# GPRS-ADM2483-V1_0________TF.net
KiCad netlist of a schematic drawn in Altium Designer
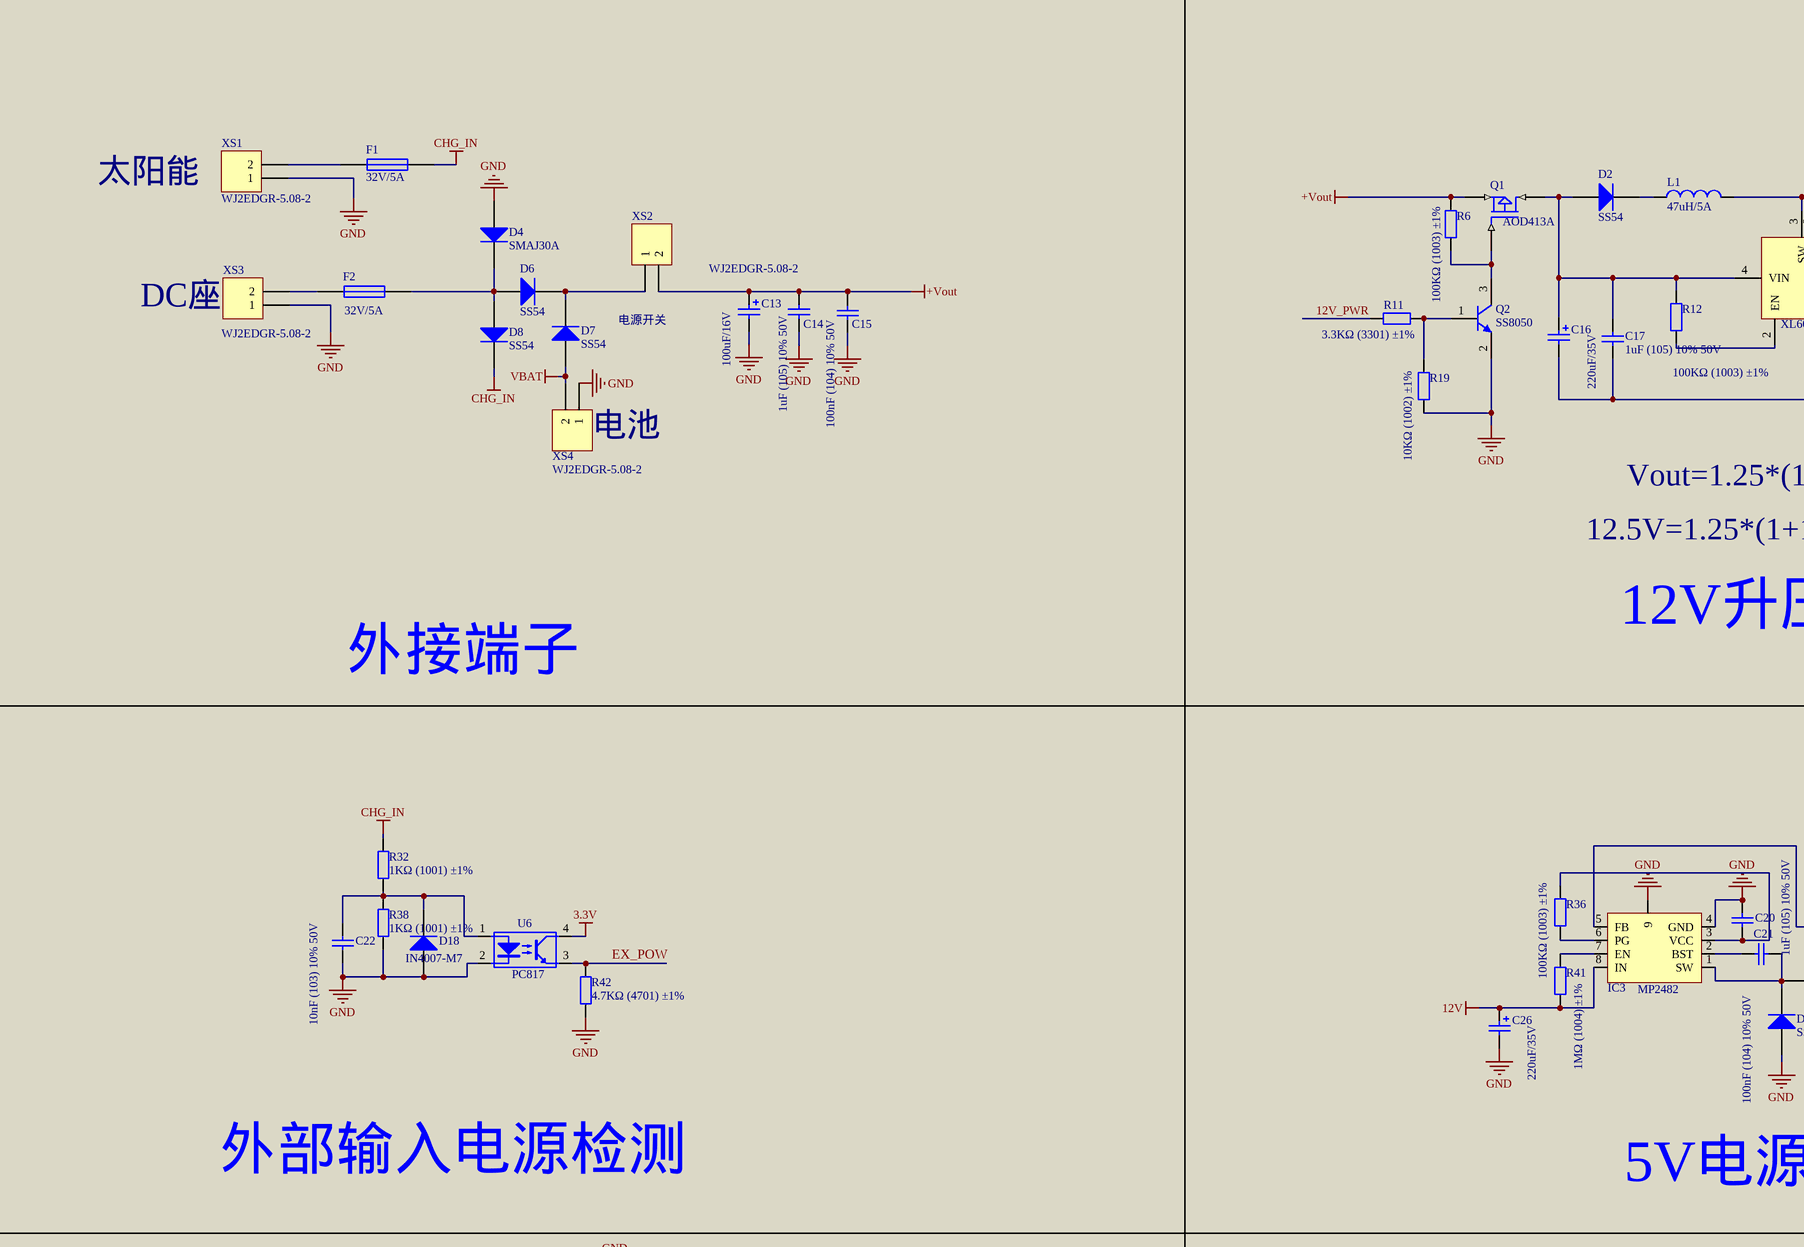
[diagram p0: GPRS-ADM2483-V1.0_______中科院TF卡.SchDoc, top left]
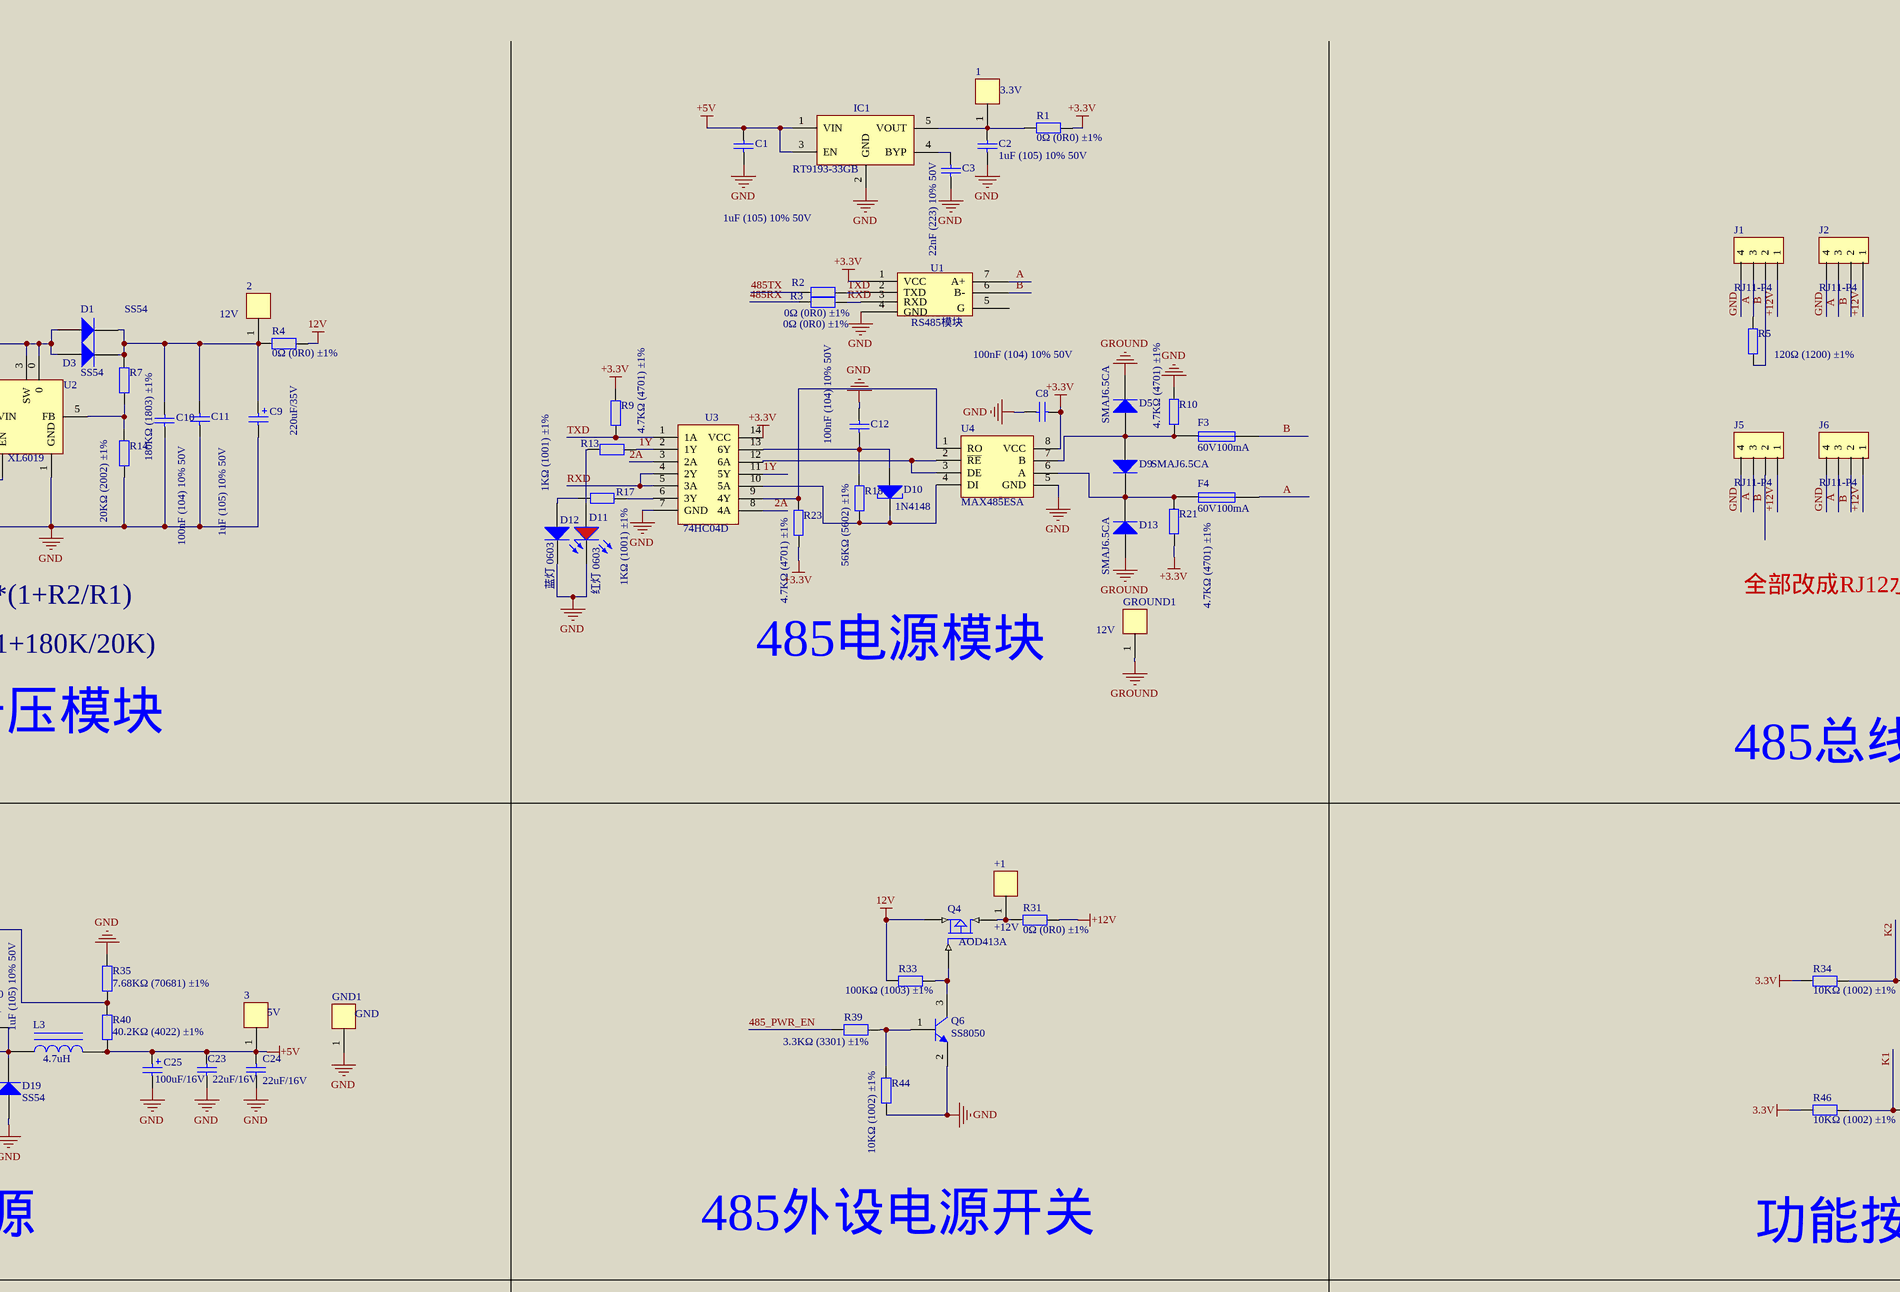
[diagram p1: GPRS-ADM2483-V1.0_______中科院TF卡.SchDoc, top middle]
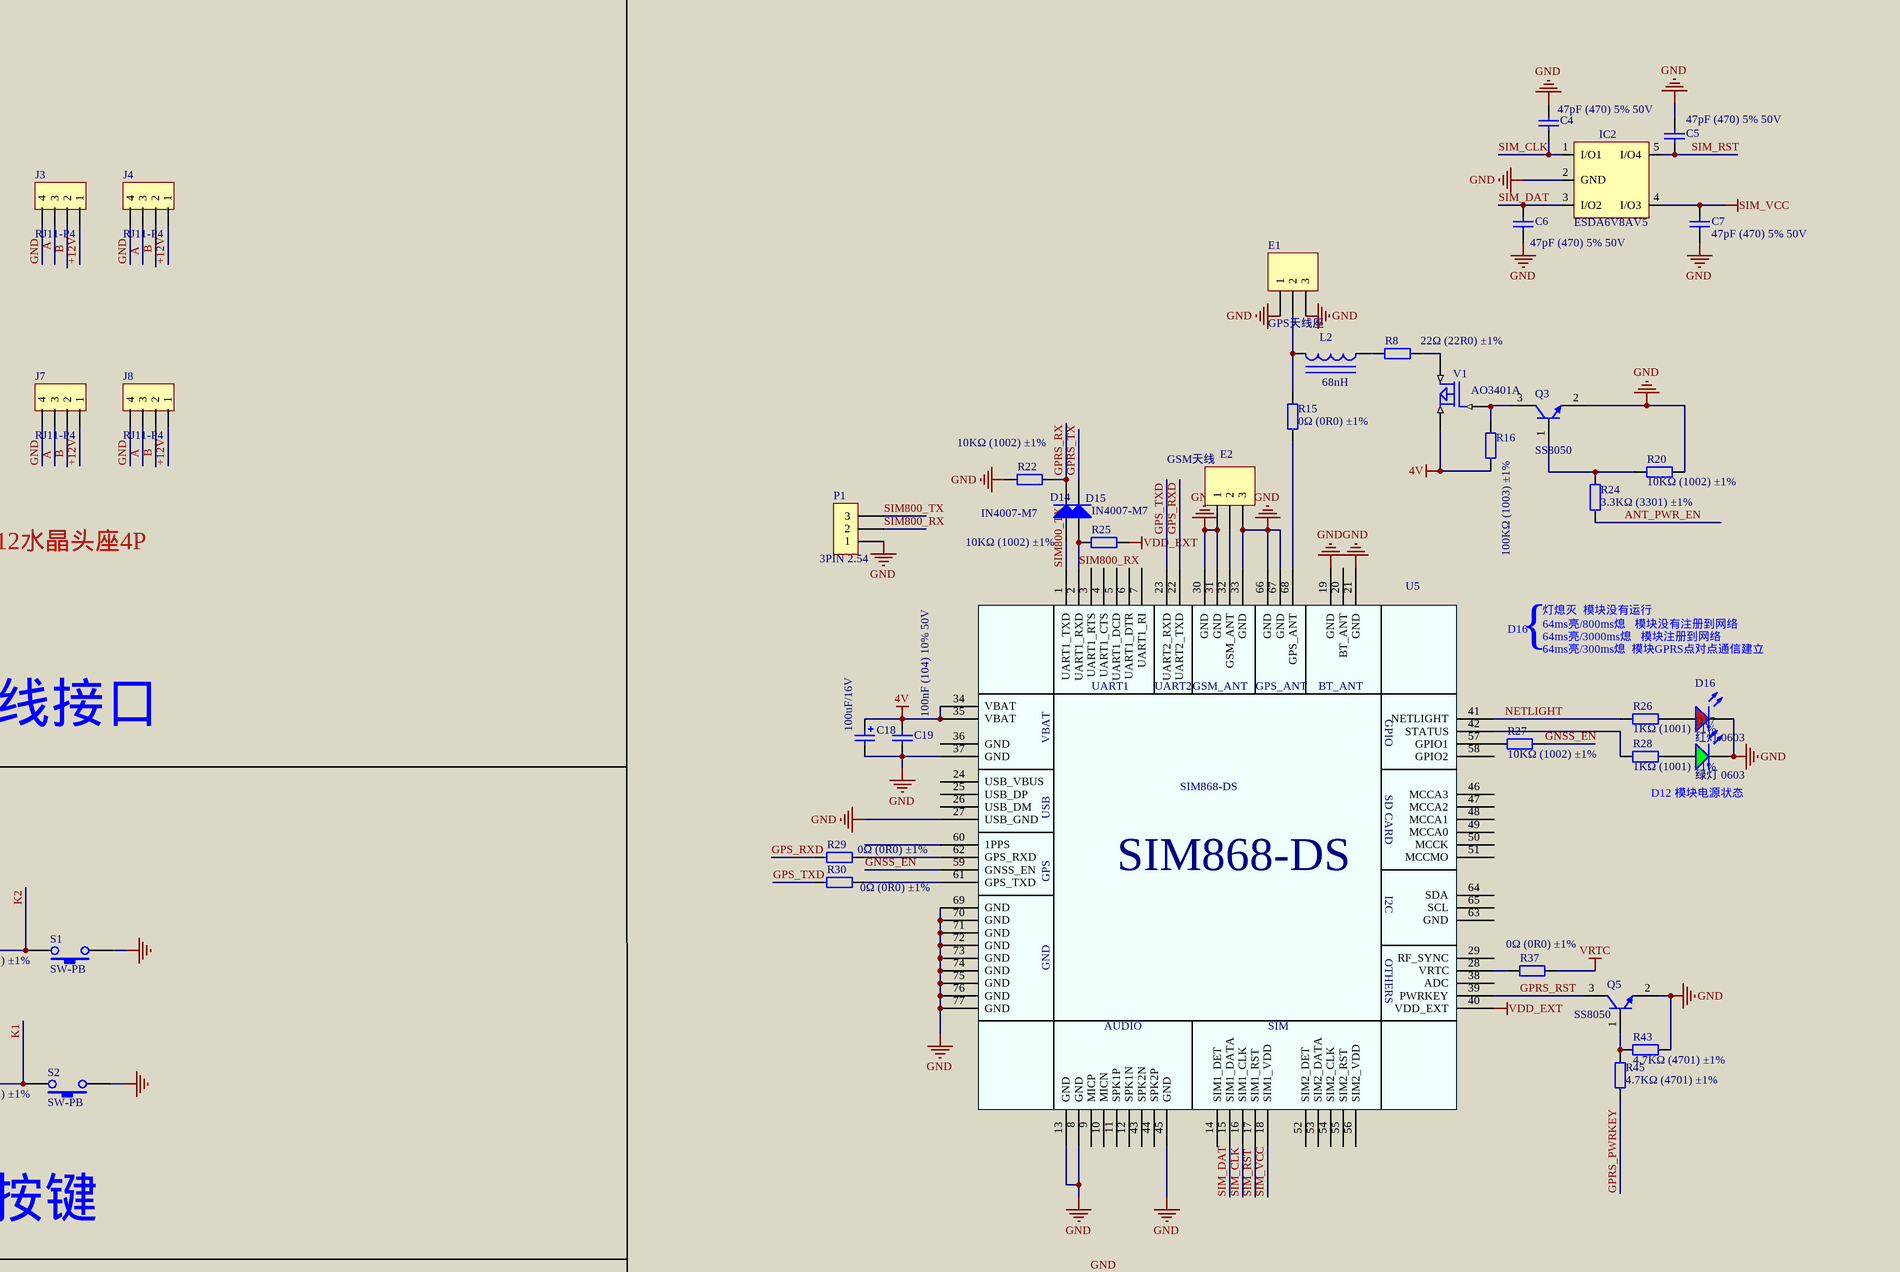
[diagram p2: GPRS-ADM2483-V1.0_______中科院TF卡.SchDoc, top right]
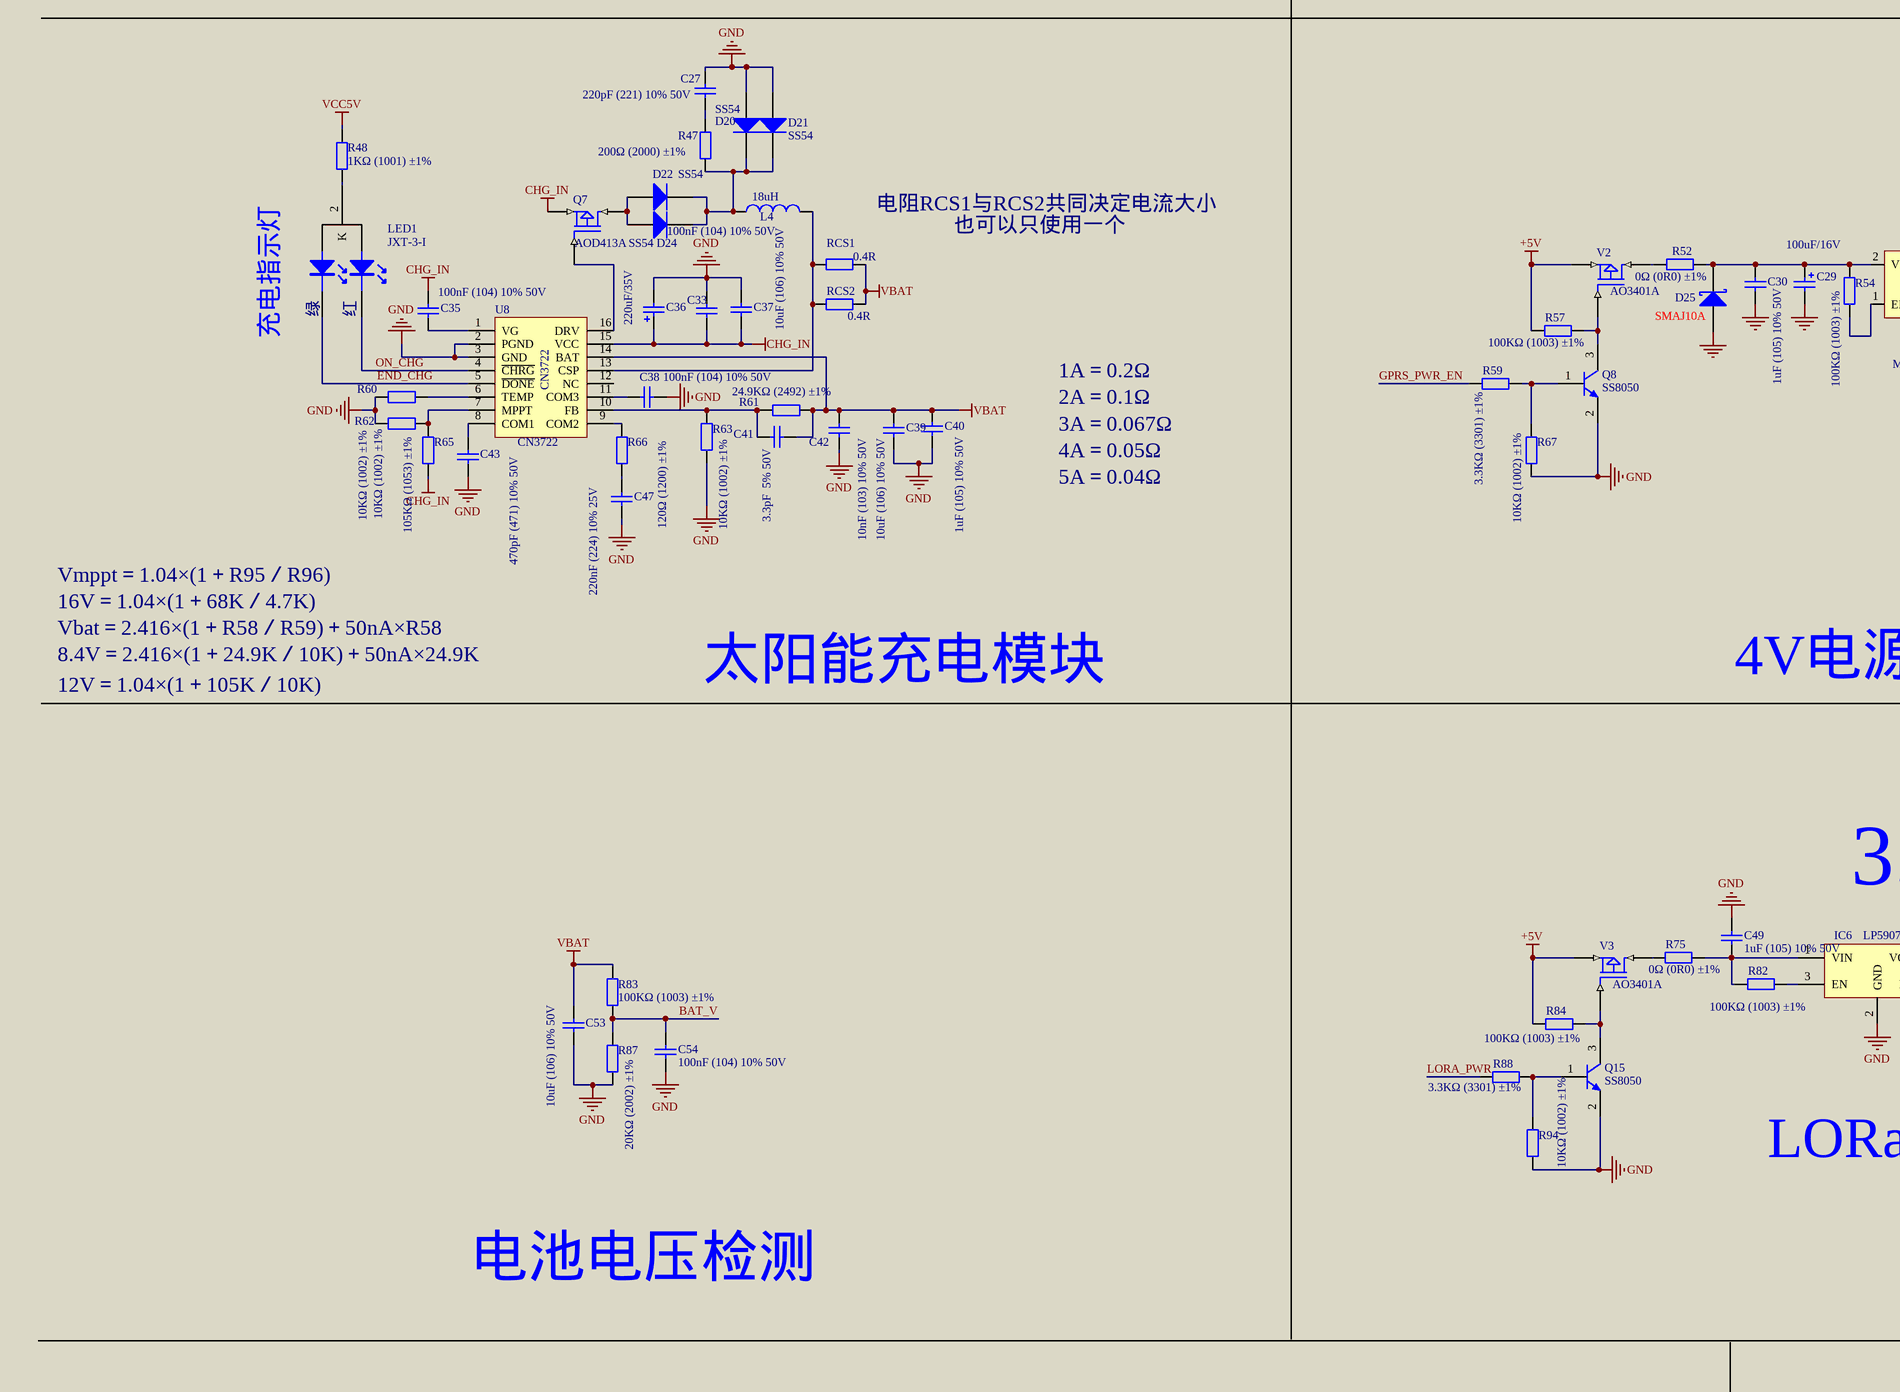
[diagram p3: GPRS-ADM2483-V1.0_______中科院TF卡.SchDoc, centre left]
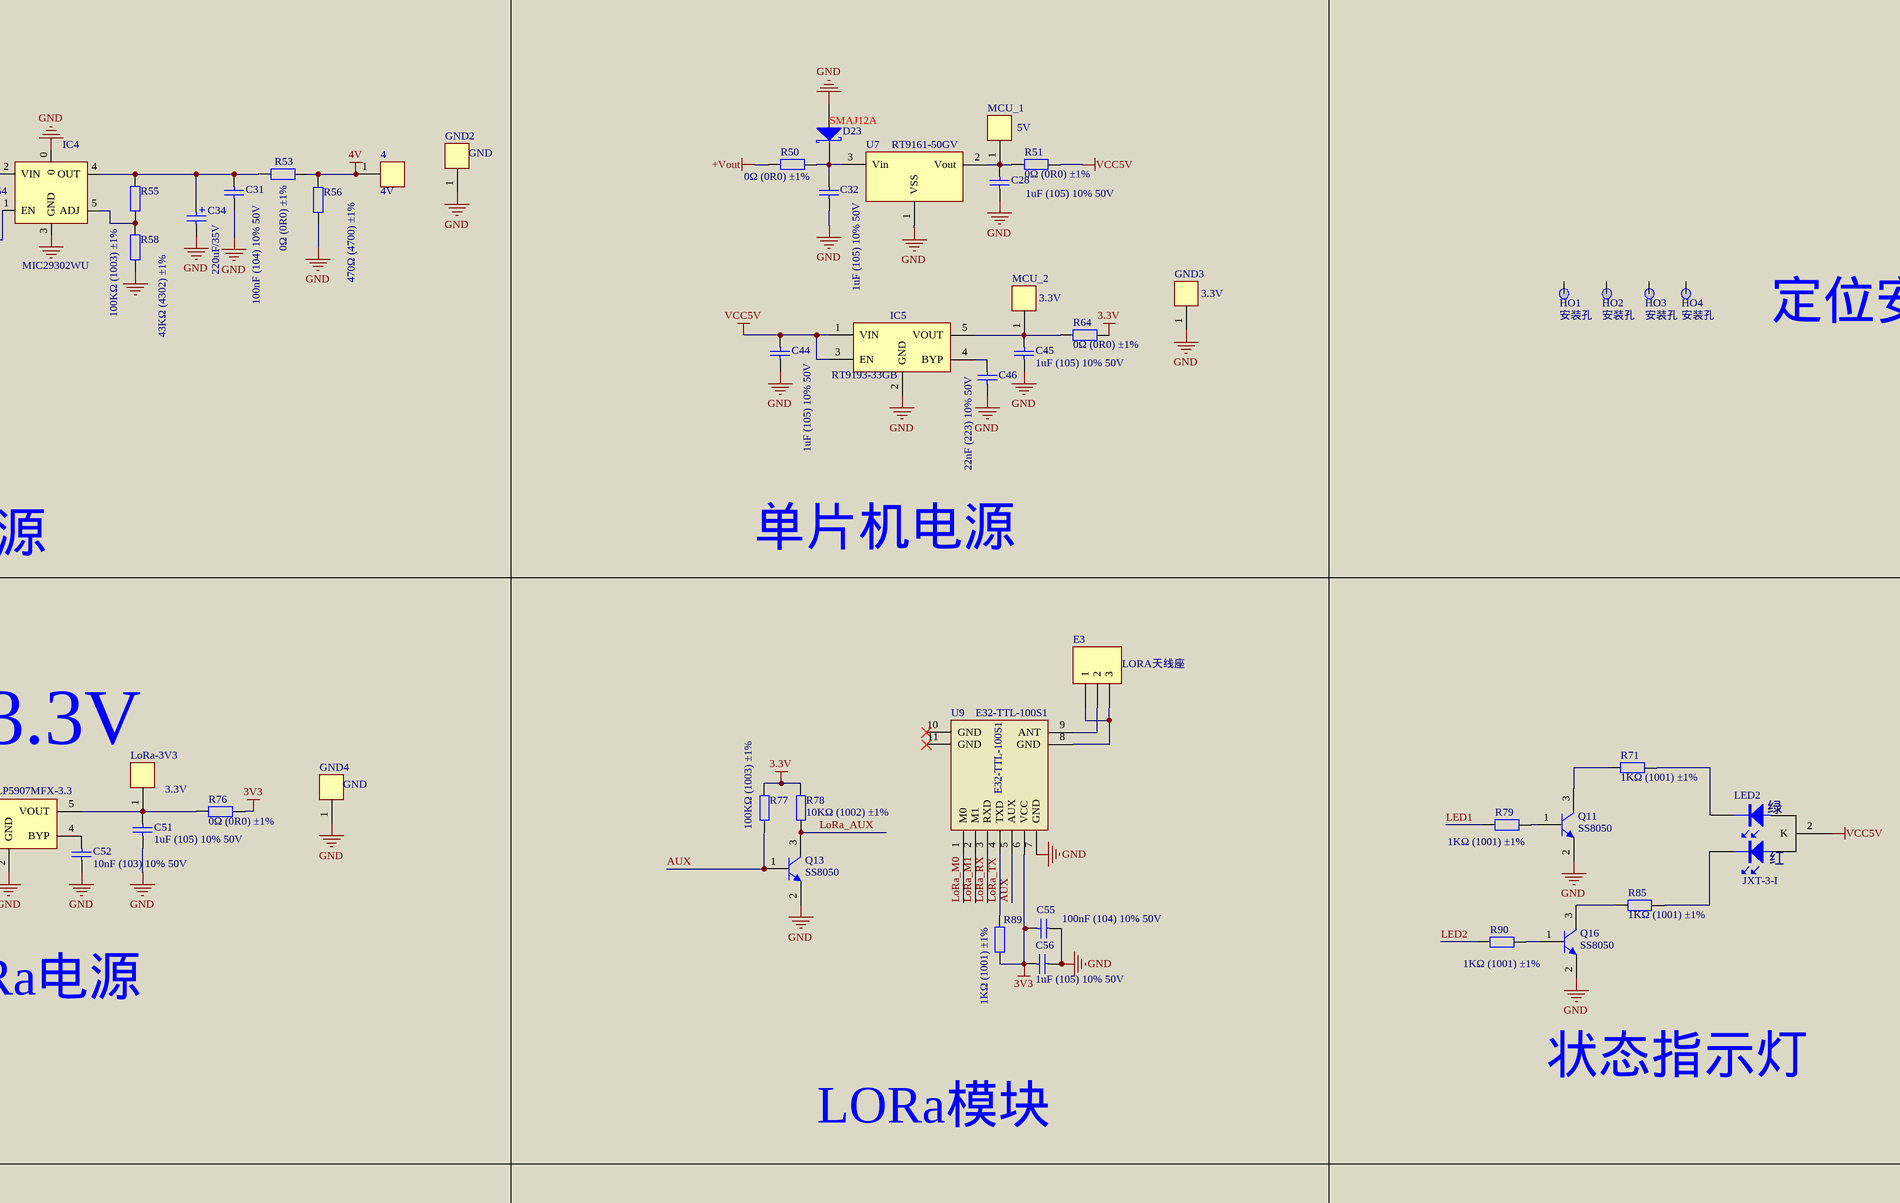
[diagram p4: GPRS-ADM2483-V1.0_______中科院TF卡.SchDoc, centre middle]
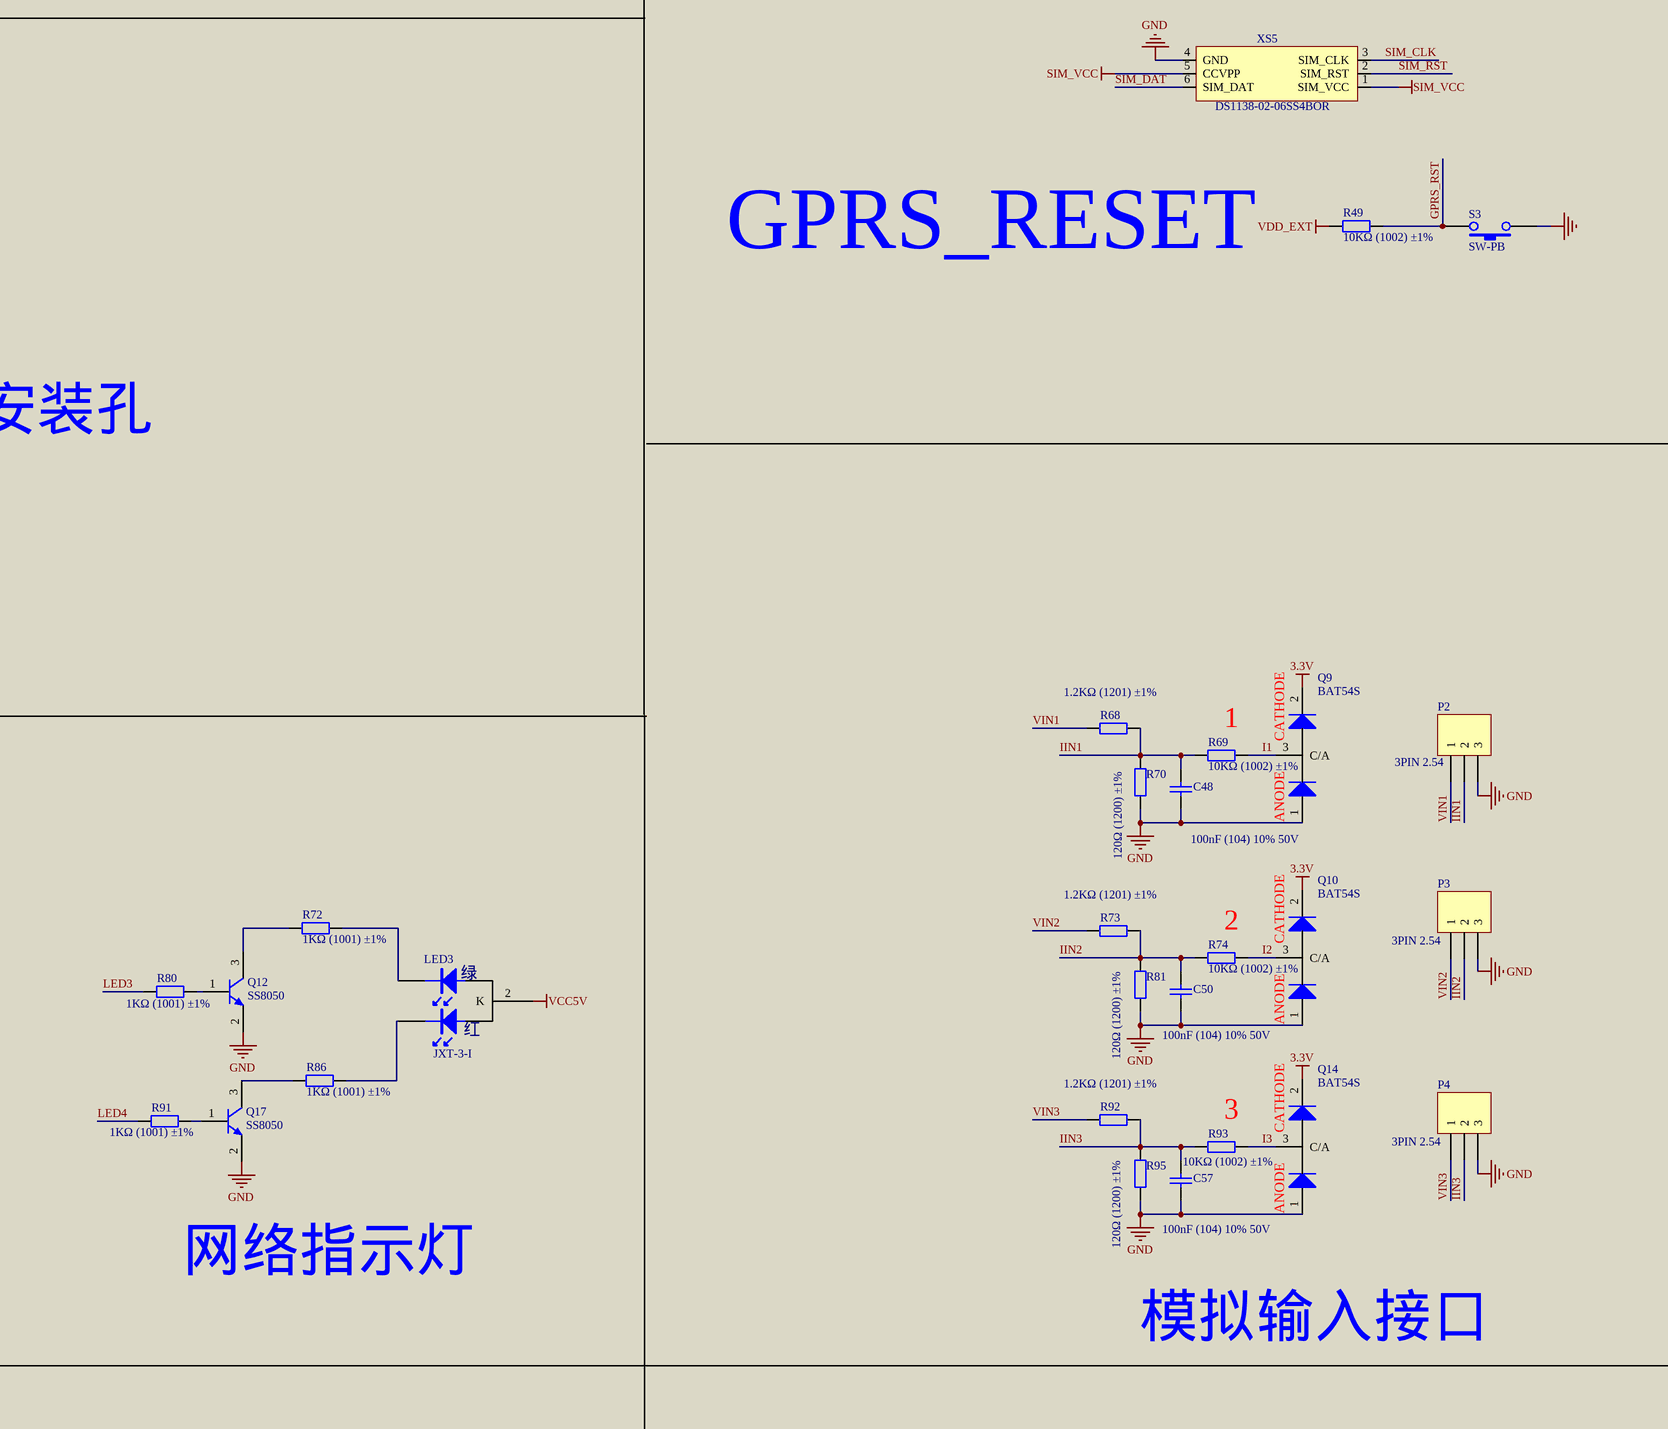
[diagram p5: GPRS-ADM2483-V1.0_______中科院TF卡.SchDoc, centre right]
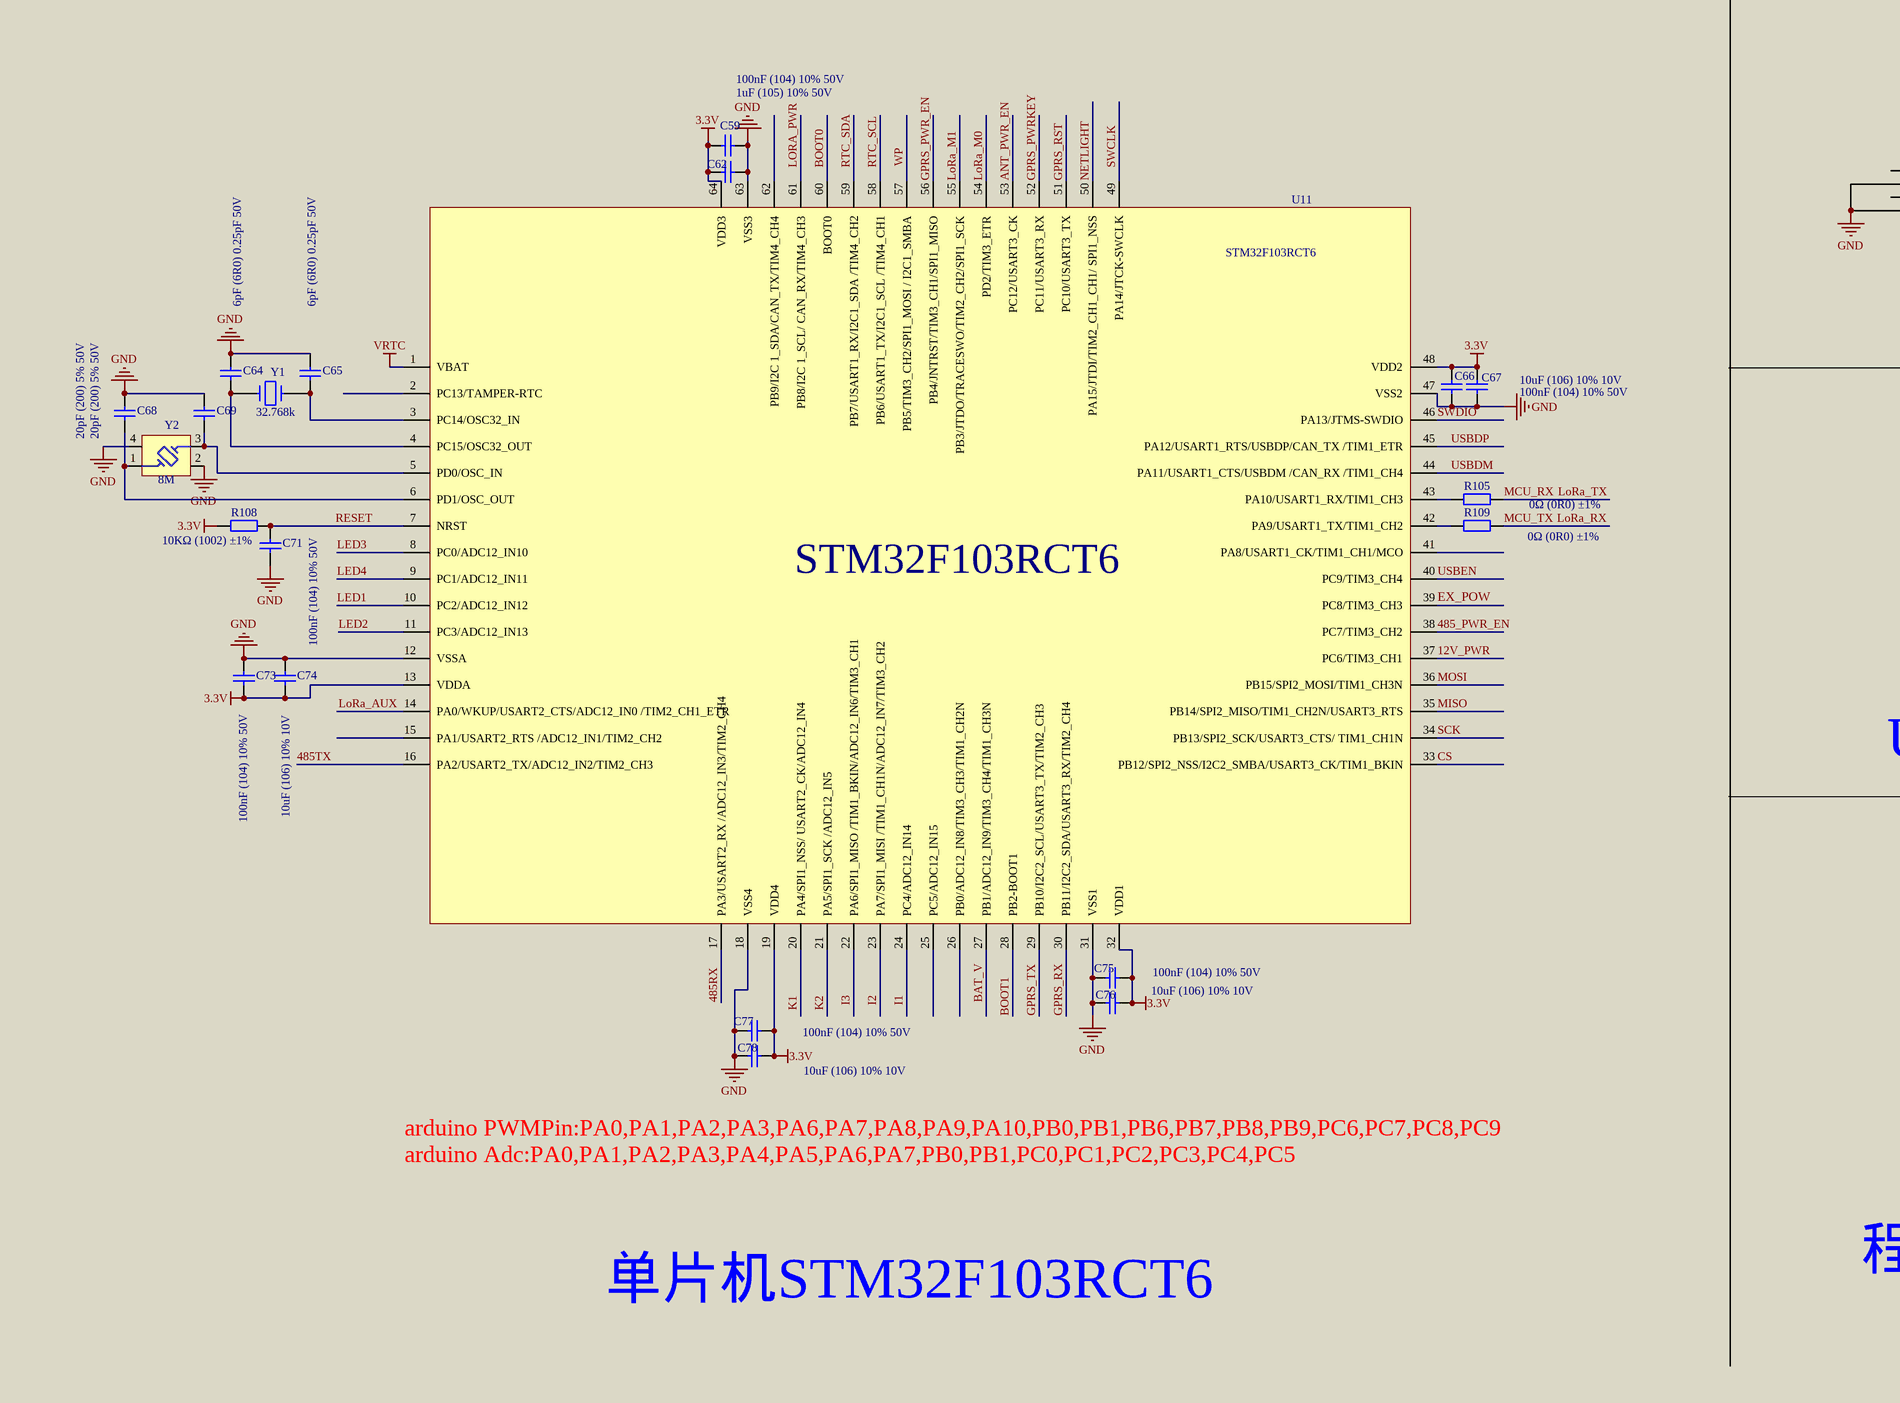
[diagram p6: GPRS-ADM2483-V1.0_______中科院TF卡.SchDoc, bottom left]
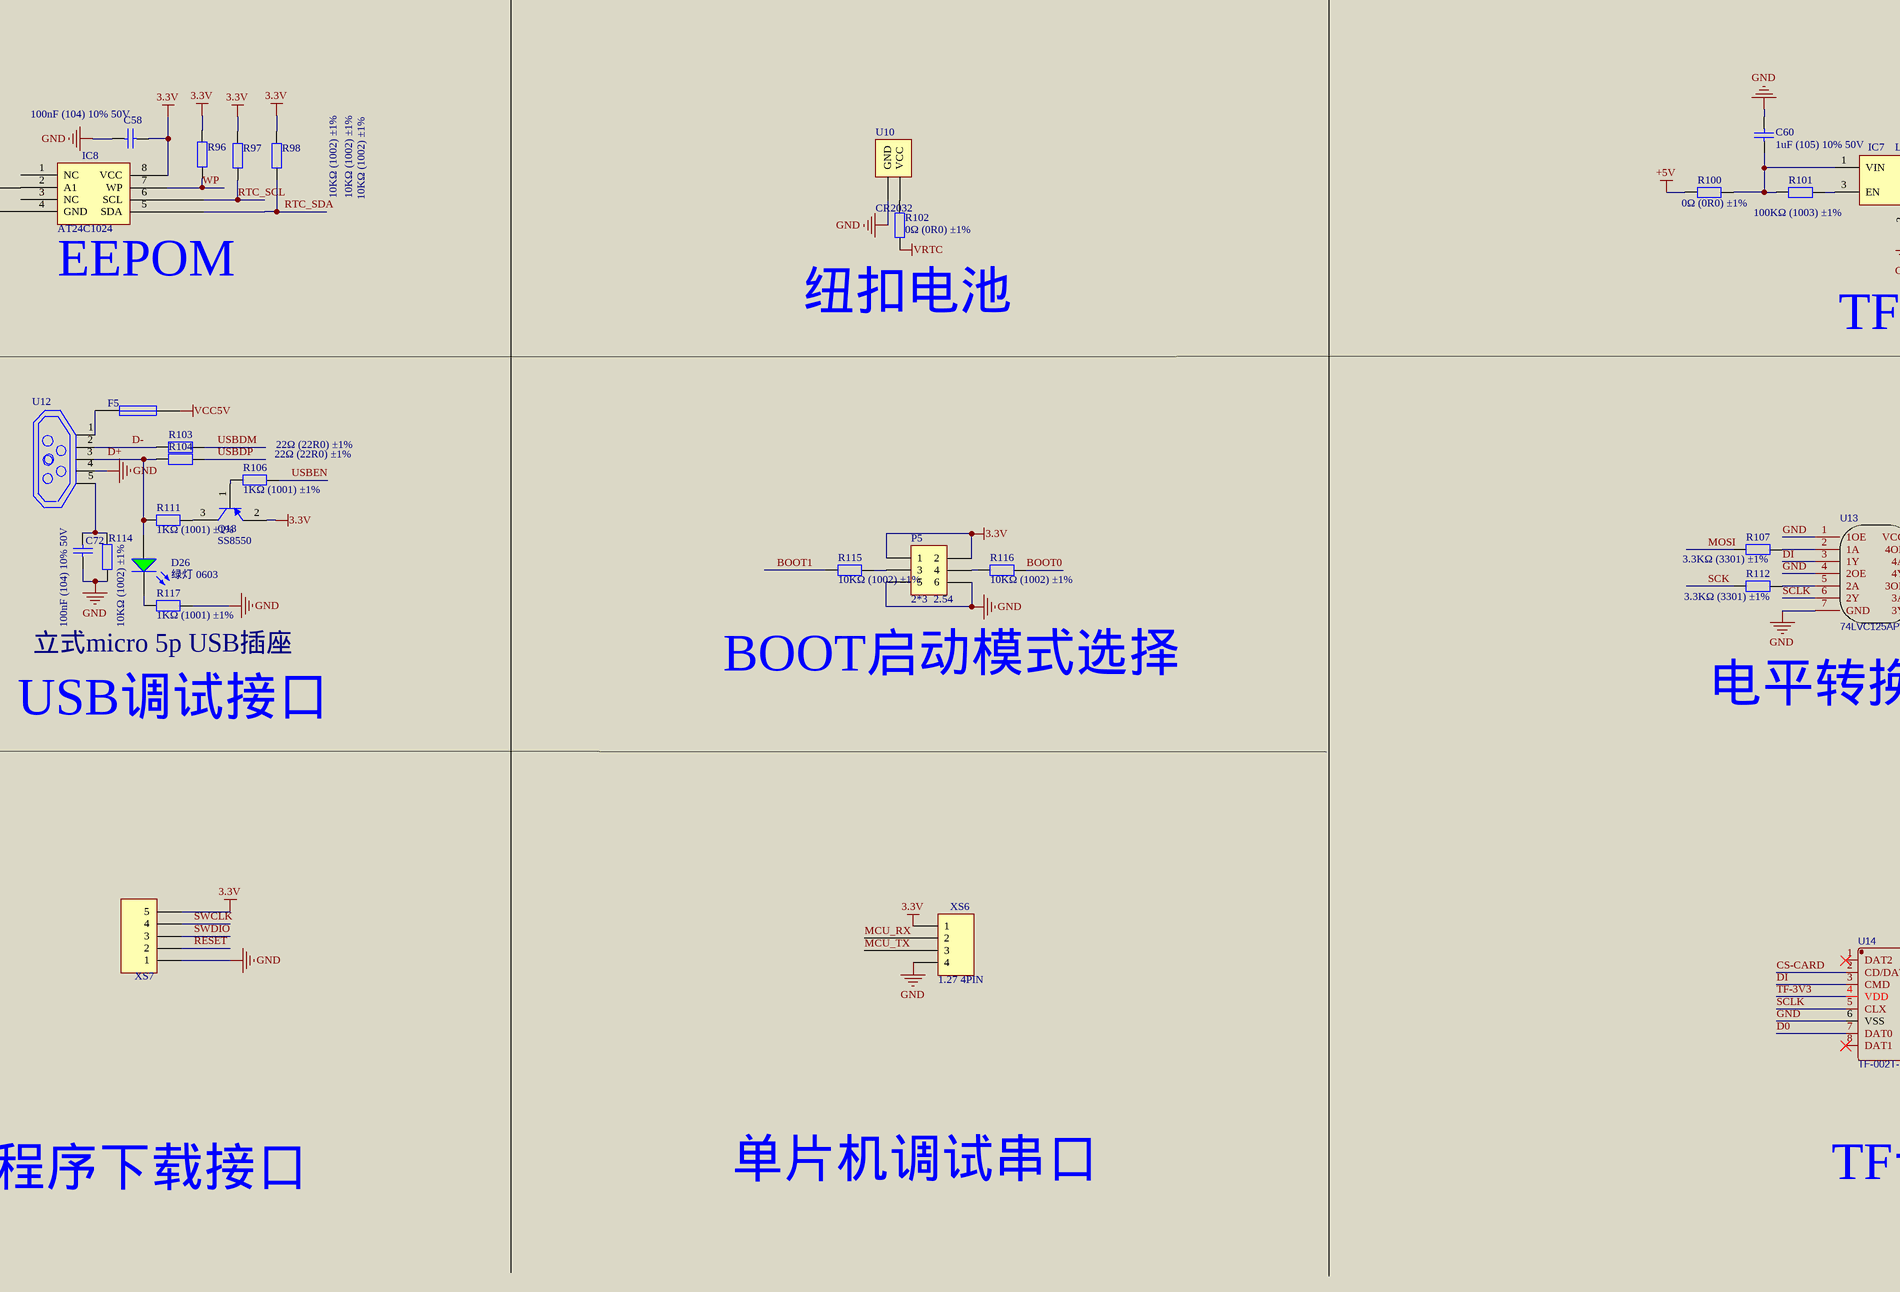
[diagram p7: GPRS-ADM2483-V1.0_______中科院TF卡.SchDoc, bottom middle]
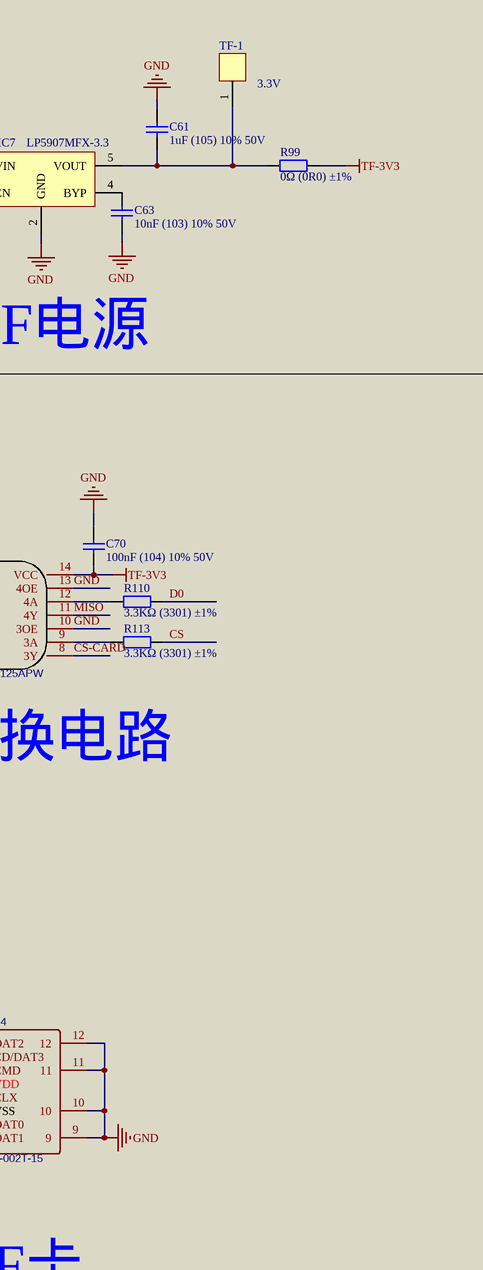
[diagram p8: GPRS-ADM2483-V1.0_______中科院TF卡.SchDoc, bottom right]

(export (version "E")
  (design (tool "Eeschema 10.0.6"))
  (components
    (comp (ref "+1")
      (value "+12V")
      (footprint "TEST_POINT")
      (description "测试点")
      (libsource (lib "InforCenterBoard") (part "TEST_POINT"))
    )
    (comp (ref "1")
      (value "3.3V")
      (footprint "TEST_POINT")
      (libsource (lib "InforCenterBoard") (part "TEST_POINT"))
    )
    (comp (ref "2")
      (value "12V")
      (footprint "TEST_POINT")
      (description "测试点")
      (libsource (lib "InforCenterBoard") (part "TEST_POINT"))
    )
    (comp (ref "3")
      (value "5V")
      (footprint "TEST_POINT")
      (description "测试点")
      (libsource (lib "InforCenterBoard") (part "TEST_POINT"))
    )
    (comp (ref "4")
      (value "4V")
      (footprint "TEST_POINT")
      (description "测试点")
      (libsource (lib "") (part "TEST_POINT_1"))
    )
    (comp (ref "C1")
      (value "1uF (105) 10% 50V")
      (footprint "LC-0603_C")
      (description "贴片电容")
      (libsource (lib "My_Library") (part "0603 1uF (105) 10% 50V"))
    )
    (comp (ref "C2")
      (value "1uF (105) 10% 50V")
      (footprint "LC-0603_C")
      (description "贴片电容")
      (libsource (lib "My_Library") (part "0603 1uF (105) 10% 50V"))
    )
    (comp (ref "C3")
      (value "22nF (223) 10% 50V")
      (footprint "LC-0603_C")
      (description "贴片电容")
      (libsource (lib "My_Library") (part "0603 22nF (223) 10% 50V"))
    )
    (comp (ref "C4")
      (value "47pF (470) 5% 50V")
      (footprint "LC-0603_C")
      (description "贴片电容")
      (libsource (lib "My_Library") (part "0603 47pF (470) 5% 50V"))
    )
    (comp (ref "C5")
      (value "47pF (470) 5% 50V")
      (footprint "LC-0603_C")
      (description "贴片电容")
      (libsource (lib "My_Library") (part "0603 47pF (470) 5% 50V"))
    )
    (comp (ref "C6")
      (value "47pF (470) 5% 50V")
      (footprint "LC-0603_C")
      (description "贴片电容")
      (libsource (lib "My_Library") (part "0603 47pF (470) 5% 50V"))
    )
    (comp (ref "C7")
      (value "47pF (470) 5% 50V")
      (footprint "LC-0603_C")
      (description "贴片电容")
      (libsource (lib "My_Library") (part "0603 47pF (470) 5% 50V"))
    )
    (comp (ref "C8")
      (value "100nF (104) 10% 50V")
      (footprint "LC-0603_C")
      (description "贴片电容")
      (libsource (lib "My_Library") (part "0603 100nF (104) 10% 50V"))
    )
    (comp (ref "C9")
      (value "220uF/35V")
      (footprint "CAPAE8*10.5")
      (description "贴片铝电解电容")
      (fields (field (name "PUBLISHER") "Altium Limited"))
      (libsource (lib "AirPlaneSign") (part "Cap -8*10.5"))
    )
    (comp (ref "C10")
      (value "100nF (104) 10% 50V")
      (footprint "LC-0603_C")
      (description "贴片电容")
      (libsource (lib "My_Library") (part "0603 100nF (104) 10% 50V"))
    )
    (comp (ref "C11")
      (value "1uF (105) 10% 50V")
      (footprint "LC-0603_C")
      (description "贴片电容")
      (libsource (lib "My_Library") (part "0603 1uF (105) 10% 50V"))
    )
    (comp (ref "C12")
      (value "100nF (104) 10% 50V")
      (footprint "LC-0603_C")
      (description "贴片电容")
      (libsource (lib "My_Library") (part "0603 100nF (104) 10% 50V"))
    )
    (comp (ref "C13")
      (value "100uF/16V")
      (footprint "CAPAE6.3*7.7")
      (description "贴片铝电解电容")
      (fields (field (name "PUBLISHER") "Altium Limited"))
      (libsource (lib "AirPlaneSign") (part "Cap -6.3*7.7"))
    )
    (comp (ref "C14")
      (value "1uF (105) 10% 50V")
      (footprint "LC-0603_C")
      (description "贴片电容")
      (libsource (lib "My_Library") (part "0603 1uF (105) 10% 50V"))
    )
    (comp (ref "C15")
      (value "100nF (104) 10% 50V")
      (footprint "LC-0603_C")
      (description "贴片电容")
      (libsource (lib "My_Library") (part "0603 100nF (104) 10% 50V"))
    )
    (comp (ref "C16")
      (value "220uF/35V")
      (footprint "CAPAE8*10.5")
      (description "贴片铝电解电容")
      (fields (field (name "PUBLISHER") "Altium Limited"))
      (libsource (lib "AirPlaneSign") (part "Cap -8*10.5"))
    )
    (comp (ref "C17")
      (value "1uF (105) 10% 50V")
      (footprint "LC-0603_C")
      (description "贴片电容")
      (libsource (lib "My_Library") (part "0603 1uF (105) 10% 50V"))
    )
    (comp (ref "C18")
      (value "100uF/16V")
      (footprint "CAPAE6.3*7.7")
      (description "贴片铝电解电容")
      (fields (field (name "PUBLISHER") "Altium Limited"))
      (libsource (lib "AirPlaneSign") (part "Cap -6.3*7.7"))
    )
    (comp (ref "C19")
      (value "100nF (104) 10% 50V")
      (footprint "LC-0603_C")
      (description "贴片电容")
      (libsource (lib "My_Library") (part "0603 100nF (104) 10% 50V"))
    )
    (comp (ref "C20")
      (value "1uF (105) 10% 50V")
      (footprint "LC-0603_C")
      (description "贴片电容")
      (libsource (lib "My_Library") (part "0603 1uF (105) 10% 50V"))
    )
    (comp (ref "C21")
      (value "100nF (104) 10% 50V")
      (footprint "LC-0603_C")
      (description "贴片电容")
      (libsource (lib "My_Library") (part "0603 100nF (104) 10% 50V"))
    )
    (comp (ref "C22")
      (value "10nF (103) 10% 50V")
      (footprint "LC-0603_C")
      (description "贴片电容")
      (libsource (lib "My_Library") (part "0603 10nF (103) 10% 50V"))
    )
    (comp (ref "C23")
      (value "22uF/16V")
      (footprint "C-1206")
      (description "贴片电容")
      (fields (field (name "PUBLISHER") "Altium Limited"))
      (libsource (lib "AirPlaneSign") (part "Cap"))
    )
    (comp (ref "C24")
      (value "22uF/16V")
      (footprint "C-1206")
      (description "贴片电容")
      (fields (field (name "PUBLISHER") "Altium Limited"))
      (libsource (lib "AirPlaneSign") (part "Cap"))
    )
    (comp (ref "C25")
      (value "100uF/16V")
      (footprint "CAPAE6.3*7.7")
      (description "贴片铝电解电容")
      (fields (field (name "PUBLISHER") "Altium Limited"))
      (libsource (lib "AirPlaneSign") (part "Cap -6.3*7.7"))
    )
    (comp (ref "C26")
      (value "220uF/35V")
      (footprint "CAPAE8*10.5")
      (description "贴片铝电解电容")
      (fields (field (name "PUBLISHER") "Altium Limited"))
      (libsource (lib "AirPlaneSign") (part "Cap -8*10.5"))
    )
    (comp (ref "C27")
      (value "220pF (221) 10% 50V")
      (footprint "LC-0603_C")
      (description "贴片电容")
      (libsource (lib "My_Library") (part "0603 220pF (221) 10% 50V"))
    )
    (comp (ref "C28")
      (value "1uF (105) 10% 50V")
      (footprint "LC-0603_C")
      (description "贴片电容")
      (libsource (lib "My_Library") (part "0603 1uF (105) 10% 50V"))
    )
    (comp (ref "C29")
      (value "100uF/16V")
      (footprint "CAPAE6.3*7.7")
      (description "贴片铝电解电容")
      (fields (field (name "PUBLISHER") "Altium Limited"))
      (libsource (lib "AirPlaneSign") (part "Cap -6.3*7.7"))
    )
    (comp (ref "C30")
      (value "1uF (105) 10% 50V")
      (footprint "LC-0603_C")
      (description "贴片电容")
      (libsource (lib "My_Library") (part "0603 1uF (105) 10% 50V"))
    )
    (comp (ref "C31")
      (value "100nF (104) 10% 50V")
      (footprint "LC-0603_C")
      (description "贴片电容")
      (libsource (lib "My_Library") (part "0603 100nF (104) 10% 50V"))
    )
    (comp (ref "C32")
      (value "1uF (105) 10% 50V")
      (footprint "LC-0603_C")
      (description "贴片电容")
      (libsource (lib "My_Library") (part "0603 1uF (105) 10% 50V"))
    )
    (comp (ref "C33")
      (value "100nF (104) 10% 50V")
      (footprint "LC-0603_C")
      (description "贴片电容")
      (libsource (lib "My_Library") (part "0603 100nF (104) 10% 50V"))
    )
    (comp (ref "C34")
      (value "220uF/35V")
      (footprint "CAPAE8*10.5")
      (description "贴片铝电解电容")
      (fields (field (name "PUBLISHER") "Altium Limited"))
      (libsource (lib "AirPlaneSign") (part "Cap -8*10.5"))
    )
    (comp (ref "C35")
      (value "100nF (104) 10% 50V")
      (footprint "LC-0603_C")
      (description "贴片电容")
      (libsource (lib "My_Library") (part "0603 100nF (104) 10% 50V"))
    )
    (comp (ref "C36")
      (value "220uF/35V")
      (footprint "CAPAE8*10.5")
      (description "贴片铝电解电容")
      (fields (field (name "PUBLISHER") "Altium Limited"))
      (libsource (lib "AirPlaneSign") (part "Cap -8*10.5"))
    )
    (comp (ref "C37")
      (value "10uF (106) 10% 50V")
      (footprint "LC-1206_C")
      (description "贴片电容")
      (libsource (lib "My_Library") (part "1206 10uF (106) 10% 50V"))
    )
    (comp (ref "C38")
      (value "100nF (104) 10% 50V")
      (footprint "LC-0603_C")
      (description "贴片电容")
      (libsource (lib "My_Library") (part "0603 100nF (104) 10% 50V"))
    )
    (comp (ref "C39")
      (value "10uF (106) 10% 50V")
      (footprint "LC-1206_C")
      (description "贴片电容")
      (libsource (lib "My_Library") (part "1206 10uF (106) 10% 50V"))
    )
    (comp (ref "C40")
      (value "1uF (105) 10% 50V")
      (footprint "LC-0603_C")
      (description "贴片电容")
      (libsource (lib "My_Library") (part "0603 1uF (105) 10% 50V"))
    )
    (comp (ref "C41")
      (value "3.3pF  5% 50V")
      (footprint "LC-0603_C")
      (description "贴片电容")
      (libsource (lib "My_Library") (part "0603 33pF (330) 5% 50V"))
    )
    (comp (ref "C42")
      (value "10nF (103) 10% 50V")
      (footprint "LC-0603_C")
      (description "贴片电容")
      (libsource (lib "My_Library") (part "0603 10nF (103) 10% 50V"))
    )
    (comp (ref "C43")
      (value "470pF (471) 10% 50V")
      (footprint "LC-0603_C")
      (description "贴片电容")
      (libsource (lib "My_Library") (part "0603 470pF (471) 10% 50V"))
    )
    (comp (ref "C44")
      (value "1uF (105) 10% 50V")
      (footprint "LC-0603_C")
      (description "贴片电容")
      (libsource (lib "My_Library") (part "0603 1uF (105) 10% 50V"))
    )
    (comp (ref "C45")
      (value "1uF (105) 10% 50V")
      (footprint "LC-0603_C")
      (description "贴片电容")
      (libsource (lib "My_Library") (part "0603 1uF (105) 10% 50V"))
    )
    (comp (ref "C46")
      (value "22nF (223) 10% 50V")
      (footprint "LC-0603_C")
      (description "贴片电容")
      (libsource (lib "My_Library") (part "0603 22nF (223) 10% 50V"))
    )
    (comp (ref "C47")
      (value "220nF (224) 10% 25V")
      (footprint "LC-0603_C")
      (description "贴片电容")
      (libsource (lib "My_Library") (part "0603 220nF (224) 10% 25V"))
    )
    (comp (ref "C48")
      (value "100nF (104) 10% 50V")
      (footprint "LC-0603_C")
      (description "贴片电容")
      (libsource (lib "My_Library") (part "0603 100nF (104) 10% 50V"))
    )
    (comp (ref "C49")
      (value "1uF (105) 10% 50V")
      (footprint "LC-0603_C")
      (description "贴片电容")
      (libsource (lib "My_Library") (part "0603 1uF (105) 10% 50V"))
    )
    (comp (ref "C50")
      (value "100nF (104) 10% 50V")
      (footprint "LC-0603_C")
      (description "贴片电容")
      (libsource (lib "My_Library") (part "0603 100nF (104) 10% 50V"))
    )
    (comp (ref "C51")
      (value "1uF (105) 10% 50V")
      (footprint "LC-0603_C")
      (description "贴片电容")
      (libsource (lib "My_Library") (part "0603 1uF (105) 10% 50V"))
    )
    (comp (ref "C52")
      (value "10nF (103) 10% 50V")
      (footprint "LC-0603_C")
      (description "贴片电容")
      (libsource (lib "My_Library") (part "0603 10nF (103) 10% 50V"))
    )
    (comp (ref "C53")
      (value "10uF (106) 10% 50V")
      (footprint "LC-1206_C")
      (description "贴片电容")
      (libsource (lib "My_Library") (part "1206 10uF (106) 10% 50V"))
    )
    (comp (ref "C54")
      (value "100nF (104) 10% 50V")
      (footprint "LC-0603_C")
      (description "贴片电容")
      (libsource (lib "My_Library") (part "0603 100nF (104) 10% 50V"))
    )
    (comp (ref "C55")
      (value "100nF (104) 10% 50V")
      (footprint "LC-0603_C")
      (description "贴片电容")
      (libsource (lib "My_Library") (part "0603 100nF (104) 10% 50V"))
    )
    (comp (ref "C56")
      (value "1uF (105) 10% 50V")
      (footprint "LC-0603_C")
      (description "贴片电容")
      (libsource (lib "My_Library") (part "0603 1uF (105) 10% 50V"))
    )
    (comp (ref "C57")
      (value "100nF (104) 10% 50V")
      (footprint "LC-0603_C")
      (description "贴片电容")
      (libsource (lib "My_Library") (part "0603 100nF (104) 10% 50V"))
    )
    (comp (ref "C58")
      (value "100nF (104) 10% 50V")
      (footprint "LC-0603_C")
      (description "贴片电容")
      (libsource (lib "My_Library") (part "0603 100nF (104) 10% 50V"))
    )
    (comp (ref "C59")
      (value "1uF (105) 10% 50V")
      (footprint "LC-0603_C")
      (description "贴片电容")
      (libsource (lib "My_Library") (part "0603 1uF (105) 10% 50V"))
    )
    (comp (ref "C60")
      (value "1uF (105) 10% 50V")
      (footprint "LC-0603_C")
      (description "贴片电容")
      (libsource (lib "My_Library") (part "0603 1uF (105) 10% 50V"))
    )
    (comp (ref "C61")
      (value "1uF (105) 10% 50V")
      (footprint "LC-0603_C")
      (description "贴片电容")
      (libsource (lib "My_Library") (part "0603 1uF (105) 10% 50V"))
    )
    (comp (ref "C62")
      (value "100nF (104) 10% 50V")
      (footprint "LC-0603_C")
      (description "贴片电容")
      (libsource (lib "My_Library") (part "0603 100nF (104) 10% 50V"))
    )
    (comp (ref "C63")
      (value "10nF (103) 10% 50V")
      (footprint "LC-0603_C")
      (description "贴片电容")
      (libsource (lib "My_Library") (part "0603 10nF (103) 10% 50V"))
    )
    (comp (ref "C64")
      (value "6pF (6R0) 0.25pF 50V")
      (footprint "LC-0603_C")
      (description "贴片电容")
      (libsource (lib "My_Library") (part "0603 6pF (6R0) 0.25pF 50V"))
    )
    (comp (ref "C65")
      (value "6pF (6R0) 0.25pF 50V")
      (footprint "LC-0603_C")
      (description "贴片电容")
      (libsource (lib "My_Library") (part "0603 6pF (6R0) 0.25pF 50V"))
    )
    (comp (ref "C66")
      (value "10uF (106) 10% 10V")
      (footprint "LC-0603_C")
      (description "贴片电容")
      (libsource (lib "My_Library") (part "0603 10uF (106) 10% 10V"))
    )
    (comp (ref "C67")
      (value "100nF (104) 10% 50V")
      (footprint "LC-0603_C")
      (description "贴片电容")
      (libsource (lib "My_Library") (part "0603 100nF (104) 10% 50V"))
    )
    (comp (ref "C68")
      (value "20pF (200) 5% 50V")
      (footprint "LC-0603_C")
      (description "贴片电容")
      (libsource (lib "My_Library") (part "0603 20pF (200) 5% 50V"))
    )
    (comp (ref "C69")
      (value "20pF (200) 5% 50V")
      (footprint "LC-0603_C")
      (description "贴片电容")
      (libsource (lib "My_Library") (part "0603 20pF (200) 5% 50V"))
    )
    (comp (ref "C70")
      (value "100nF (104) 10% 50V")
      (footprint "LC-0603_C")
      (description "贴片电容")
      (libsource (lib "My_Library") (part "0603 100nF (104) 10% 50V"))
    )
    (comp (ref "C71")
      (value "100nF (104) 10% 50V")
      (footprint "LC-0603_C")
      (description "贴片电容")
      (libsource (lib "My_Library") (part "0603 100nF (104) 10% 50V"))
    )
    (comp (ref "C72")
      (value "100nF (104) 10% 50V")
      (footprint "LC-0603_C")
      (description "贴片电容")
      (libsource (lib "My_Library") (part "0603 100nF (104) 10% 50V"))
    )
    (comp (ref "C73")
      (value "100nF (104) 10% 50V")
      (footprint "LC-0603_C")
      (description "贴片电容")
      (libsource (lib "My_Library") (part "0603 100nF (104) 10% 50V"))
    )
    (comp (ref "C74")
      (value "10uF (106) 10% 10V")
      (footprint "LC-0603_C")
      (description "贴片电容")
      (libsource (lib "My_Library") (part "0603 10uF (106) 10% 10V"))
    )
    (comp (ref "C75")
      (value "100nF (104) 10% 50V")
      (footprint "LC-0603_C")
      (description "贴片电容")
      (libsource (lib "My_Library") (part "0603 100nF (104) 10% 50V"))
    )
    (comp (ref "C76")
      (value "10uF (106) 10% 10V")
      (footprint "LC-0603_C")
      (description "贴片电容")
      (libsource (lib "My_Library") (part "0603 10uF (106) 10% 10V"))
    )
    (comp (ref "C77")
      (value "100nF (104) 10% 50V")
      (footprint "LC-0603_C")
      (description "贴片电容")
      (libsource (lib "My_Library") (part "0603 100nF (104) 10% 50V"))
    )
    (comp (ref "C78")
      (value "10uF (106) 10% 10V")
      (footprint "LC-0603_C")
      (description "贴片电容")
      (libsource (lib "My_Library") (part "0603 10uF (106) 10% 10V"))
    )
    (comp (ref "D1")
      (value "SS54")
      (footprint "LC-SMA(DO-214AC)_S1")
      (description "二极管")
      (libsource (lib "My_Library") (part "SMA(DO-214AC) SS54"))
    )
    (comp (ref "D2")
      (value "SS54")
      (footprint "LC-SMA(DO-214AC)_S1")
      (description "二极管")
      (libsource (lib "My_Library") (part "SMA(DO-214AC) SS54"))
    )
    (comp (ref "D3")
      (value "SS54")
      (footprint "LC-SMA(DO-214AC)_S1")
      (description "二极管")
      (libsource (lib "My_Library") (part "SMA(DO-214AC) SS54"))
    )
    (comp (ref "D4")
      (value "SMAJ30A")
      (footprint "LC-SMA(DO-214AC)_S5")
      (description "TVS二极管")
      (fields (field (name "PUBLISHER") "Altium Limited"))
      (libsource (lib "AirPlaneSign") (part "SMAJ30A"))
    )
    (comp (ref "D5")
      (value "SMAJ6.5CA")
      (footprint "DO-214AC")
      (description "通用二极管")
      (fields (field (name "PUBLISHER") "Altium Limited"))
      (libsource (lib "kytence") (part "Diode"))
    )
    (comp (ref "D6")
      (value "SS54")
      (footprint "LC-SMA(DO-214AC)_S1")
      (description "二极管")
      (libsource (lib "My_Library") (part "SMA(DO-214AC) SS54"))
    )
    (comp (ref "D7")
      (value "SS54")
      (footprint "LC-SMA(DO-214AC)_S1")
      (description "二极管")
      (libsource (lib "My_Library") (part "SMA(DO-214AC) SS54"))
    )
    (comp (ref "D8")
      (value "SS54")
      (footprint "LC-SMA(DO-214AC)_S1")
      (description "二极管")
      (libsource (lib "My_Library") (part "SMA(DO-214AC) SS54"))
    )
    (comp (ref "D9")
      (value "SMAJ6.5CA")
      (footprint "DO-214AC")
      (description "通用二极管")
      (fields (field (name "PUBLISHER") "Altium Limited"))
      (libsource (lib "kytence") (part "Diode"))
    )
    (comp (ref "D10")
      (value "1N4148")
      (footprint "LL-34")
      (description "稳压二极管")
      (fields (field (name "PUBLISHER") "Altium Limited"))
      (libsource (lib "Emergency lighting") (part "Diode Zener"))
    )
    (comp (ref "D11")
      (value "红灯 0603")
      (footprint "LC-0603_LED_S1")
      (description "发光二极管")
      (libsource (lib "My_Library") (part "0603 红灯"))
    )
    (comp (ref "D12")
      (value "蓝灯 0603")
      (footprint "LC-0603_LED_S1")
      (description "发光二极管")
      (libsource (lib "My_Library") (part "0603 蓝灯"))
    )
    (comp (ref "D13")
      (value "SMAJ6.5CA")
      (footprint "DO-214AC")
      (description "通用二极管")
      (fields (field (name "PUBLISHER") "Altium Limited"))
      (libsource (lib "kytence") (part "Diode"))
    )
    (comp (ref "D14")
      (value "IN4007-M7")
      (footprint "SMA(DO-214AC)")
      (description "开关二极管")
      (fields (field (name "PUBLISHER") "Altium Limited"))
      (libsource (lib "kytence") (part "Diode"))
    )
    (comp (ref "D15")
      (value "IN4007-M7")
      (footprint "SMA(DO-214AC)")
      (description "开关二极管")
      (fields (field (name "PUBLISHER") "Altium Limited"))
      (libsource (lib "kytence") (part "Diode"))
    )
    (comp (ref "D16")
      (value "红灯 0603")
      (footprint "LC-0603_LED_S1")
      (description "发光二极管")
      (libsource (lib "My_Library") (part "0603 红灯"))
    )
    (comp (ref "D17")
      (value "绿灯 0603")
      (footprint "LC-0603_LED_S1")
      (description "发光二极管")
      (libsource (lib "My_Library") (part "0603 绿灯"))
    )
    (comp (ref "D18")
      (value "IN4007-M7")
      (footprint "SMA(DO-214AC)")
      (description "二极管")
      (fields (field (name "PUBLISHER") "Altium Limited"))
      (libsource (lib "Miscellaneous Devices") (part "Diode 1N4001"))
    )
    (comp (ref "D19")
      (value "SS54")
      (footprint "LC-SMA(DO-214AC)_S1")
      (description "二极管")
      (libsource (lib "My_Library") (part "SMA(DO-214AC) SS54"))
    )
    (comp (ref "D20")
      (value "SS54")
      (footprint "LC-SMA(DO-214AC)_S1")
      (description "二极管")
      (libsource (lib "My_Library") (part "SMA(DO-214AC) SS54"))
    )
    (comp (ref "D21")
      (value "SS54")
      (footprint "LC-SMA(DO-214AC)_S1")
      (description "二极管")
      (libsource (lib "My_Library") (part "SMA(DO-214AC) SS54"))
    )
    (comp (ref "D22")
      (value "SS54")
      (footprint "LC-SMA(DO-214AC)_S1")
      (description "二极管")
      (libsource (lib "My_Library") (part "SMA(DO-214AC) SS54"))
    )
    (comp (ref "D23")
      (value "SMAJ12A")
      (footprint "SMA(DO-214AC)")
      (description "TVS二极管")
      (fields (field (name "PUBLISHER") "Altium Limited"))
      (libsource (lib "Emergency lighting") (part "D Schottky"))
    )
    (comp (ref "D24")
      (value "SS54")
      (footprint "LC-SMA(DO-214AC)_S1")
      (description "二极管")
      (libsource (lib "My_Library") (part "SMA(DO-214AC) SS54"))
    )
    (comp (ref "D25")
      (value "SMAJ10A")
      (footprint "SMA(DO-214AC)")
      (description "TVS二极管")
      (fields (field (name "PUBLISHER") "Altium Limited"))
      (libsource (lib "Emergency lighting") (part "D Schottky"))
    )
    (comp (ref "D26")
      (value "绿灯 0603")
      (footprint "LC-0603_LED_S1")
      (description "发光二极管")
      (libsource (lib "My_Library") (part "0603 绿灯"))
    )
    (comp (ref "E1")
      (value "GPS天线座")
      (footprint "IPEX1")
      (description "天线座IPEX")
      (fields (field (name "PUBLISHER") "Altium Limited"))
      (libsource (lib "AirPlaneSign") (part "Header 3H"))
    )
    (comp (ref "E2")
      (value "GSM天线")
      (footprint "IPEX1")
      (description "天线座IPEX")
      (fields (field (name "PUBLISHER") "Altium Limited"))
      (libsource (lib "AirPlaneSign") (part "Header 3H"))
    )
    (comp (ref "E3")
      (value "LORA天线座")
      (footprint "IPEX1")
      (description "天线座IPEX")
      (fields (field (name "PUBLISHER") "Altium Limited"))
      (libsource (lib "AirPlaneSign") (part "Header 3H"))
    )
    (comp (ref "F1")
      (value "32V/5A")
      (footprint "Fuse-1206")
      (description "贴片保险丝")
      (fields (field (name "PUBLISHER") "Altium Limited"))
      (libsource (lib "Emergency lighting") (part "Fuse"))
    )
    (comp (ref "F2")
      (value "32V/5A")
      (footprint "Fuse-1206")
      (description "贴片保险丝")
      (fields (field (name "PUBLISHER") "Altium Limited"))
      (libsource (lib "Emergency lighting") (part "Fuse"))
    )
    (comp (ref "F3")
      (value "60V100mA")
      (footprint "Fuse-1812")
      (description "贴片保险丝")
      (fields (field (name "PUBLISHER") "Altium Limited"))
      (libsource (lib "Emergency lighting") (part "Fuse"))
    )
    (comp (ref "F4")
      (value "60V100mA")
      (footprint "Fuse-1812")
      (description "贴片保险丝")
      (fields (field (name "PUBLISHER") "Altium Limited"))
      (libsource (lib "Emergency lighting") (part "Fuse"))
    )
    (comp (ref "F5")
      (value "32V/5A")
      (footprint "FUSE-1206")
      (description "贴片保险丝")
      (fields (field (name "PUBLISHER") "Altium Limited"))
      (libsource (lib "AirPlaneSign") (part "Fuse"))
    )
    (comp (ref "GND1")
      (value "GND")
      (footprint "TEST_POINT")
      (description "测试点")
      (libsource (lib "InforCenterBoard") (part "TEST_POINT"))
    )
    (comp (ref "GND2")
      (value "GND")
      (footprint "TEST_POINT")
      (description "测试点")
      (libsource (lib "InforCenterBoard") (part "TEST_POINT"))
    )
    (comp (ref "GND3")
      (value "3.3V")
      (footprint "TEST_POINT")
      (libsource (lib "InforCenterBoard") (part "TEST_POINT"))
    )
    (comp (ref "GND4")
      (value "GND")
      (footprint "TEST_POINT")
      (description "测试点")
      (libsource (lib "InforCenterBoard") (part "TEST_POINT"))
    )
    (comp (ref "GROUND1")
      (value "12V")
      (footprint "TEST_POINT")
      (description "测试点")
      (libsource (lib "InforCenterBoard") (part "TEST_POINT"))
    )
    (comp (ref "HO1") (value "安装孔") (footprint "安装孔") (libsource (lib "AirPlaneSign") (part "安装孔")))
    (comp (ref "HO2") (value "安装孔") (footprint "安装孔") (libsource (lib "AirPlaneSign") (part "安装孔")))
    (comp (ref "HO3") (value "安装孔") (footprint "安装孔") (libsource (lib "AirPlaneSign") (part "安装孔")))
    (comp (ref "HO4") (value "安装孔") (footprint "安装孔") (libsource (lib "AirPlaneSign") (part "安装孔")))
    (comp (ref "IC1")
      (value "RT9193-33GB")
      (footprint "SOT23-5")
      (description "低压差线性稳压(LDO)")
      (libsource (lib "FM") (part "CAT6219"))
    )
    (comp (ref "IC2")
      (value "ESDA6V8AV5")
      (footprint "SOT-553")
      (description "防静电")
      (libsource (lib "USR-GM3  GM3s SCH") (part "ESDA6V8AV5"))
    )
    (comp (ref "IC3")
      (value "MP2482")
      (footprint "SO8 -TP")
      (description "DC-DC芯片")
      (libsource (lib "AirPlaneSign") (part "MP2482"))
    )
    (comp (ref "IC4")
      (value "MIC29302WU")
      (footprint "MIC29302WU")
      (description "LDO")
      (libsource (lib "AirPlaneSign") (part "MIC29302WU"))
    )
    (comp (ref "IC5")
      (value "RT9193-33GB")
      (footprint "SOT23-5")
      (description "低压差线性稳压(LDO)")
      (libsource (lib "FM") (part "CAT6219"))
    )
    (comp (ref "IC6")
      (value "LP5907MFX-3.3")
      (footprint "SOT23-5")
      (description "3.3V降压")
      (libsource (lib "FM") (part "CAT6219"))
    )
    (comp (ref "IC7")
      (value "LP5907MFX-3.3")
      (footprint "SOT23-5")
      (description "3.3V降压")
      (libsource (lib "FM") (part "CAT6219"))
    )
    (comp (ref "IC8")
      (value "AT24C1024")
      (footprint "SO8")
      (description "EEPROM")
      (libsource (lib "WSN") (part "AT24C1024"))
    )
    (comp (ref "J1")
      (value "RJ11-P4")
      (footprint "RJ11_P4")
      (description "RJ11电话插座P4")
      (libsource (lib "AirPlaneSign") (part "RJ11电话插座P4"))
    )
    (comp (ref "J2")
      (value "RJ11-P4")
      (footprint "RJ11_P4")
      (description "RJ11电话插座P4")
      (libsource (lib "AirPlaneSign") (part "RJ11电话插座P4"))
    )
    (comp (ref "J3")
      (value "RJ11-P4")
      (footprint "RJ11_P4")
      (description "RJ11电话插座P4")
      (libsource (lib "AirPlaneSign") (part "RJ11电话插座P4"))
    )
    (comp (ref "J4")
      (value "RJ11-P4")
      (footprint "RJ11_P4")
      (description "RJ11电话插座P4")
      (libsource (lib "AirPlaneSign") (part "RJ11电话插座P4"))
    )
    (comp (ref "J5")
      (value "RJ11-P4")
      (footprint "RJ11_P4")
      (description "RJ11电话插座P4")
      (libsource (lib "AirPlaneSign") (part "RJ11电话插座P4"))
    )
    (comp (ref "J6")
      (value "RJ11-P4")
      (footprint "RJ11_P4")
      (description "RJ11电话插座P4")
      (libsource (lib "AirPlaneSign") (part "RJ11电话插座P4"))
    )
    (comp (ref "J7")
      (value "RJ11-P4")
      (footprint "RJ11_P4")
      (description "RJ11电话插座P4")
      (libsource (lib "AirPlaneSign") (part "RJ11电话插座P4"))
    )
    (comp (ref "J8")
      (value "RJ11-P4")
      (footprint "RJ11_P4")
      (description "RJ11电话插座P4")
      (libsource (lib "AirPlaneSign") (part "RJ11电话插座P4"))
    )
    (comp (ref "L1")
      (value "47uH/5A")
      (footprint "Inductot(47uH)")
      (description "磁环电感")
      (libsource (lib "Emergency lighting") (part "INDUCTOR"))
    )
    (comp (ref "L2")
      (value "68nH")
      (footprint "L-0805")
      (description "贴片电感")
      (libsource (lib "SCHEMATIC") (part "Inductor"))
    )
    (comp (ref "L3")
      (value "4.7uH")
      (footprint "GDCD8040")
      (description "功率电感")
      (fields (field (name "PUBLISHER") "Altium Limited"))
      (libsource (lib "LLYSCHLib") (part "Inductor Iron"))
    )
    (comp (ref "L4")
      (value "18uH")
      (footprint "GDCD8040")
      (description "功率电感")
      (libsource (lib "Emergency lighting") (part "INDUCTOR"))
    )
    (comp (ref "LED1")
      (value "JXT-3-I")
      (footprint "JXT-3-l")
      (description "1.27卧式贴片针座")
      (libsource (lib "AirPlaneSign") (part "LED2_双色共阳"))
    )
    (comp (ref "LED2")
      (value "JXT-3-I")
      (footprint "JXT-3-l")
      (description "1.27卧式贴片针座")
      (libsource (lib "AirPlaneSign") (part "LED2_双色共阳"))
    )
    (comp (ref "LED3")
      (value "JXT-3-I")
      (footprint "JXT-3-l")
      (description "1.27卧式贴片针座")
      (libsource (lib "AirPlaneSign") (part "LED2_双色共阳"))
    )
    (comp (ref "LoRa-3V3")
      (value "3.3V")
      (footprint "TEST_POINT")
      (description "测试点")
      (libsource (lib "InforCenterBoard") (part "TEST_POINT"))
    )
    (comp (ref "MCU_1")
      (value "5V")
      (footprint "TEST_POINT")
      (description "测试点")
      (libsource (lib "InforCenterBoard") (part "TEST_POINT"))
    )
    (comp (ref "MCU_2")
      (value "3.3V")
      (footprint "TEST_POINT")
      (libsource (lib "InforCenterBoard") (part "TEST_POINT"))
    )
    (comp (ref "P1")
      (value "3PIN 2.54")
      (footprint "HDR1X3")
      (description "单排插针")
      (fields (field (name "PUBLISHER") "Altium Limited"))
      (libsource (lib "") (part "Header 3H_1"))
    )
    (comp (ref "P2")
      (value "3PIN 2.54")
      (footprint "WJ2EDGR-5.08-3")
      (description "插针")
      (fields (field (name "PUBLISHER") "Altium Limited"))
      (libsource (lib "AirPlaneSign") (part "WJ2EDGR-5.08-3"))
    )
    (comp (ref "P3")
      (value "3PIN 2.54")
      (footprint "WJ2EDGR-5.08-3")
      (description "插针")
      (fields (field (name "PUBLISHER") "Altium Limited"))
      (libsource (lib "AirPlaneSign") (part "WJ2EDGR-5.08-3"))
    )
    (comp (ref "P4")
      (value "3PIN 2.54")
      (footprint "WJ2EDGR-5.08-3")
      (description "插针")
      (fields (field (name "PUBLISHER") "Altium Limited"))
      (libsource (lib "AirPlaneSign") (part "WJ2EDGR-5.08-3"))
    )
    (comp (ref "P5")
      (value "2*3  2.54")
      (footprint "201S2X3")
      (description "双排插针")
      (fields (field (name "PUBLISHER") "Altium Limited"))
      (libsource (lib "AirPlaneSign") (part "Header 2*3"))
    )
    (comp (ref "Q1")
      (value "AOD413A")
      (footprint "TO-252-2")
      (description "MOS(场效应管)")
      (libsource (lib "AirPlaneSign") (part "AOD413A"))
    )
    (comp (ref "Q2")
      (value "SS8050")
      (footprint "SOT-23")
      (description "NPN贴片三极管")
      (fields (field (name "PUBLISHER") "Altium Limited"))
      (libsource (lib "My_Library") (part "SS8050"))
    )
    (comp (ref "Q3")
      (value "SS8050")
      (footprint "SOT-23")
      (description "NPN贴片三极管")
      (fields (field (name "PUBLISHER") "Altium Limited"))
      (libsource (lib "My_Library") (part "SS8050"))
    )
    (comp (ref "Q4")
      (value "AOD413A")
      (footprint "TO-252-2")
      (description "MOS(场效应管)")
      (libsource (lib "AirPlaneSign") (part "AOD413A"))
    )
    (comp (ref "Q5")
      (value "SS8050")
      (footprint "SOT-23")
      (description "NPN贴片三极管")
      (fields (field (name "PUBLISHER") "Altium Limited"))
      (libsource (lib "My_Library") (part "SS8050"))
    )
    (comp (ref "Q6")
      (value "SS8050")
      (footprint "SOT-23")
      (description "NPN贴片三极管")
      (fields (field (name "PUBLISHER") "Altium Limited"))
      (libsource (lib "My_Library") (part "SS8050"))
    )
    (comp (ref "Q7")
      (value "AOD413A")
      (footprint "TO-252-2")
      (description "MOS(场效应管)")
      (libsource (lib "AirPlaneSign") (part "AOD413A"))
    )
    (comp (ref "Q8")
      (value "SS8050")
      (footprint "SOT-23")
      (description "NPN贴片三极管")
      (fields (field (name "PUBLISHER") "Altium Limited"))
      (libsource (lib "My_Library") (part "SS8050"))
    )
    (comp (ref "Q9")
      (value "BAT54S")
      (footprint "SOT-23-3")
      (description "肖特基二极管")
      (libsource (lib "AirPlaneSign") (part "BAT54S"))
    )
    (comp (ref "Q10")
      (value "BAT54S")
      (footprint "SOT-23-3")
      (description "肖特基二极管")
      (libsource (lib "AirPlaneSign") (part "BAT54S"))
    )
    (comp (ref "Q11")
      (value "SS8050")
      (footprint "SOT-23")
      (description "NPN贴片三极管")
      (fields (field (name "PUBLISHER") "Altium Limited"))
      (libsource (lib "My_Library") (part "SS8050"))
    )
    (comp (ref "Q12")
      (value "SS8050")
      (footprint "SOT-23")
      (description "NPN贴片三极管")
      (fields (field (name "PUBLISHER") "Altium Limited"))
      (libsource (lib "My_Library") (part "SS8050"))
    )
    (comp (ref "Q13")
      (value "SS8050")
      (footprint "SOT-23")
      (description "NPN贴片三极管")
      (fields (field (name "PUBLISHER") "Altium Limited"))
      (libsource (lib "My_Library") (part "SS8050"))
    )
    (comp (ref "Q14")
      (value "BAT54S")
      (footprint "SOT-23-3")
      (description "肖特基二极管")
      (libsource (lib "AirPlaneSign") (part "BAT54S"))
    )
    (comp (ref "Q15")
      (value "SS8050")
      (footprint "SOT-23")
      (description "NPN贴片三极管")
      (fields (field (name "PUBLISHER") "Altium Limited"))
      (libsource (lib "My_Library") (part "SS8050"))
    )
    (comp (ref "Q16")
      (value "SS8050")
      (footprint "SOT-23")
      (description "NPN贴片三极管")
      (fields (field (name "PUBLISHER") "Altium Limited"))
      (libsource (lib "My_Library") (part "SS8050"))
    )
    (comp (ref "Q17")
      (value "SS8050")
      (footprint "SOT-23")
      (description "NPN贴片三极管")
      (fields (field (name "PUBLISHER") "Altium Limited"))
      (libsource (lib "My_Library") (part "SS8050"))
    )
    (comp (ref "Q18")
      (value "SS8550")
      (footprint "SOT-23")
      (description "PNP贴片三极管")
      (fields (field (name "PUBLISHER") "Altium Limited"))
      (libsource (lib "My_Library") (part "SS8550"))
    )
    (comp (ref "R1")
      (value "0Ω (0R0) ±1%")
      (footprint "LC-0603_R")
      (description "贴片电阻")
      (libsource (lib "My_Library") (part "0603 0Ω (0R0) 1%"))
    )
    (comp (ref "R2")
      (value "0Ω (0R0) ±1%")
      (footprint "LC-0603_R")
      (description "贴片电阻")
      (libsource (lib "My_Library") (part "0603 0Ω (0R0) 1%"))
    )
    (comp (ref "R3")
      (value "0Ω (0R0) ±1%")
      (footprint "LC-0603_R")
      (description "贴片电阻")
      (libsource (lib "My_Library") (part "0603 0Ω (0R0) 1%"))
    )
    (comp (ref "R4")
      (value "0Ω (0R0) ±1%")
      (footprint "LC-0603_R")
      (description "贴片电阻")
      (libsource (lib "My_Library") (part "0603 0Ω (0R0) 1%"))
    )
    (comp (ref "R5")
      (value "120Ω (1200) ±1%")
      (footprint "LC-0603_R")
      (description "贴片电阻")
      (libsource (lib "My_Library") (part "0603 120Ω (1200) 1%"))
    )
    (comp (ref "R6")
      (value "100KΩ (1003) ±1%")
      (footprint "LC-0603_R")
      (description "贴片电阻")
      (libsource (lib "My_Library") (part "0603 100KΩ (1003) 1%"))
    )
    (comp (ref "R7")
      (value "180KΩ (1803) ±1%")
      (footprint "LC-0603_R")
      (description "贴片电阻")
      (libsource (lib "My_Library") (part "0603 180KΩ (1803) 1%"))
    )
    (comp (ref "R8")
      (value "22Ω (22R0) ±1%")
      (footprint "LC-0603_R")
      (description "贴片电阻")
      (libsource (lib "My_Library") (part "0603 22Ω (22R0) 1%"))
    )
    (comp (ref "R9")
      (value "4.7KΩ (4701) ±1%")
      (footprint "LC-0603_R")
      (description "贴片电阻")
      (libsource (lib "My_Library") (part "0603 4.7KΩ (4701) 1%"))
    )
    (comp (ref "R10")
      (value "4.7KΩ (4701) ±1%")
      (footprint "LC-0603_R")
      (description "贴片电阻")
      (libsource (lib "") (part "0603 4.7KΩ (4701) 1%_1"))
    )
    (comp (ref "R11")
      (value "3.3KΩ (3301) ±1%")
      (footprint "LC-0603_R")
      (description "贴片电阻")
      (libsource (lib "My_Library") (part "0603 3.3KΩ (3301) 1%"))
    )
    (comp (ref "R12")
      (value "100KΩ (1003) ±1%")
      (footprint "LC-0603_R")
      (description "贴片电阻")
      (libsource (lib "My_Library") (part "0603 100KΩ (1003) 1%"))
    )
    (comp (ref "R13")
      (value "1KΩ (1001) ±1%")
      (footprint "LC-0603_R")
      (description "贴片电阻")
      (libsource (lib "My_Library") (part "0603 1KΩ (1001) 1%"))
    )
    (comp (ref "R14")
      (value "20KΩ (2002) ±1%")
      (footprint "LC-0603_R")
      (description "贴片电阻")
      (libsource (lib "My_Library") (part "0603 20KΩ (2002) 1%"))
    )
    (comp (ref "R15")
      (value "0Ω (0R0) ±1%")
      (footprint "LC-0603_R")
      (description "贴片电阻")
      (libsource (lib "") (part "0603 0Ω (0R0) 1%_1"))
    )
    (comp (ref "R16")
      (value "100KΩ (1003) ±1%")
      (footprint "LC-0603_R")
      (description "贴片电阻")
      (libsource (lib "My_Library") (part "0603 100KΩ (1003) 1%"))
    )
    (comp (ref "R17")
      (value "1KΩ (1001) ±1%")
      (footprint "LC-0603_R")
      (description "贴片电阻")
      (libsource (lib "My_Library") (part "0603 1KΩ (1001) 1%"))
    )
    (comp (ref "R18")
      (value "56KΩ (5602) ±1%")
      (footprint "LC-0603_R")
      (description "贴片电阻")
      (libsource (lib "My_Library") (part "0603 56KΩ (5602) 1%"))
    )
    (comp (ref "R19")
      (value "10KΩ (1002) ±1%")
      (footprint "LC-0603_R")
      (description "贴片电阻")
      (libsource (lib "") (part "0603 10KΩ (1002) 1%_1"))
    )
    (comp (ref "R20")
      (value "10KΩ (1002) ±1%")
      (footprint "LC-0603_R")
      (description "贴片电阻")
      (libsource (lib "My_Library") (part "0603 10KΩ (1002) 1%"))
    )
    (comp (ref "R21")
      (value "4.7KΩ (4701) ±1%")
      (footprint "LC-0603_R")
      (description "贴片电阻")
      (libsource (lib "My_Library") (part "0603 4.7KΩ (4701) 1%"))
    )
    (comp (ref "R22")
      (value "10KΩ (1002) ±1%")
      (footprint "LC-0603_R")
      (description "贴片电阻")
      (libsource (lib "My_Library") (part "0603 10KΩ (1002) 1%"))
    )
    (comp (ref "R23")
      (value "4.7KΩ (4701) ±1%")
      (footprint "LC-0603_R")
      (description "贴片电阻")
      (libsource (lib "My_Library") (part "0603 4.7KΩ (4701) 1%"))
    )
    (comp (ref "R24")
      (value "3.3KΩ (3301) ±1%")
      (footprint "LC-0603_R")
      (description "贴片电阻")
      (libsource (lib "") (part "0603 3.3KΩ (3301) 1%_1"))
    )
    (comp (ref "R25")
      (value "10KΩ (1002) ±1%")
      (footprint "LC-0603_R")
      (description "贴片电阻")
      (libsource (lib "My_Library") (part "0603 10KΩ (1002) 1%"))
    )
    (comp (ref "R26")
      (value "1KΩ (1001) ±1%")
      (footprint "LC-0603_R")
      (description "贴片电阻")
      (libsource (lib "My_Library") (part "0603 1KΩ (1001) 1%"))
    )
    (comp (ref "R27")
      (value "10KΩ (1002) ±1%")
      (footprint "LC-0603_R")
      (description "贴片电阻")
      (libsource (lib "My_Library") (part "0603 10KΩ (1002) 1%"))
    )
    (comp (ref "R28")
      (value "1KΩ (1001) ±1%")
      (footprint "LC-0603_R")
      (description "贴片电阻")
      (libsource (lib "My_Library") (part "0603 1KΩ (1001) 1%"))
    )
    (comp (ref "R29")
      (value "0Ω (0R0) ±1%")
      (footprint "LC-0603_R")
      (description "贴片电阻")
      (libsource (lib "My_Library") (part "0603 0Ω (0R0) 1%"))
    )
    (comp (ref "R30")
      (value "0Ω (0R0) ±1%")
      (footprint "LC-0603_R")
      (description "贴片电阻")
      (libsource (lib "My_Library") (part "0603 0Ω (0R0) 1%"))
    )
    (comp (ref "R31")
      (value "0Ω (0R0) ±1%")
      (footprint "LC-0603_R")
      (description "贴片电阻")
      (libsource (lib "My_Library") (part "0603 0Ω (0R0) 1%"))
    )
    (comp (ref "R32")
      (value "1KΩ (1001) ±1%")
      (footprint "LC-0603_R")
      (description "贴片电阻")
      (libsource (lib "") (part "0603 1KΩ (1001) 1%_1"))
    )
    (comp (ref "R33")
      (value "100KΩ (1003) ±1%")
      (footprint "LC-0603_R")
      (description "贴片电阻")
      (libsource (lib "") (part "0603 100KΩ (1003) 1%_1"))
    )
    (comp (ref "R34")
      (value "10KΩ (1002) ±1%")
      (footprint "LC-0603_R")
      (description "贴片电阻")
      (libsource (lib "My_Library") (part "0603 10KΩ (1002) 1%"))
    )
    (comp (ref "R35")
      (value "7.68KΩ (70681) ±1%")
      (footprint "LC-0603_R")
      (description "贴片电阻")
      (libsource (lib "My_Library") (part "0603 75KΩ (7502) 1%"))
    )
    (comp (ref "R36")
      (value "100KΩ (1003) ±1%")
      (footprint "LC-0603_R")
      (description "贴片电阻")
      (libsource (lib "My_Library") (part "0603 100KΩ (1003) 1%"))
    )
    (comp (ref "R37")
      (value "0Ω (0R0) ±1%")
      (footprint "LC-0603_R")
      (description "贴片电阻")
      (libsource (lib "My_Library") (part "0603 0Ω (0R0) 1%"))
    )
    (comp (ref "R38")
      (value "1KΩ (1001) ±1%")
      (footprint "LC-0603_R")
      (description "贴片电阻")
      (libsource (lib "") (part "0603 1KΩ (1001) 1%_1"))
    )
    (comp (ref "R39")
      (value "3.3KΩ (3301) ±1%")
      (footprint "LC-0603_R")
      (description "贴片电阻")
      (libsource (lib "My_Library") (part "0603 3.3KΩ (3301) 1%"))
    )
    (comp (ref "R40")
      (value "40.2KΩ (4022) ±1%")
      (footprint "LC-0603_R")
      (description "贴片电阻")
      (libsource (lib "My_Library") (part "0603 40.2KΩ (4022) 1%"))
    )
    (comp (ref "R41")
      (value "1MΩ (1004) ±1%")
      (footprint "LC-0603_R")
      (description "贴片电阻")
      (libsource (lib "My_Library") (part "0603 1MΩ (1004) 1%"))
    )
    (comp (ref "R42")
      (value "4.7KΩ (4701) ±1%")
      (footprint "LC-0603_R")
      (description "贴片电阻")
      (libsource (lib "My_Library") (part "0603 4.7KΩ (4701) 1%"))
    )
    (comp (ref "R43")
      (value "4.7KΩ (4701) ±1%")
      (footprint "LC-0603_R")
      (description "贴片电阻")
      (libsource (lib "") (part "0603 4.7KΩ (4701) 1%_2"))
    )
    (comp (ref "R44")
      (value "10KΩ (1002) ±1%")
      (footprint "LC-0603_R")
      (description "贴片电阻")
      (libsource (lib "") (part "0603 10KΩ (1002) 1%_1"))
    )
    (comp (ref "R45")
      (value "4.7KΩ (4701) ±1%")
      (footprint "LC-0603_R")
      (description "贴片电阻")
      (libsource (lib "My_Library") (part "0603 4.7KΩ (4701) 1%"))
    )
    (comp (ref "R46")
      (value "10KΩ (1002) ±1%")
      (footprint "LC-0603_R")
      (description "贴片电阻")
      (libsource (lib "My_Library") (part "0603 10KΩ (1002) 1%"))
    )
    (comp (ref "R47")
      (value "200Ω (2000) ±1%")
      (footprint "LC-0603_R")
      (description "贴片电阻")
      (libsource (lib "My_Library") (part "0603 200Ω (2000) 1%"))
    )
    (comp (ref "R48")
      (value "1KΩ (1001) ±1%")
      (footprint "LC-0603_R")
      (description "贴片电阻")
      (libsource (lib "") (part "0603 1KΩ (1001) 1%_1"))
    )
    (comp (ref "R49")
      (value "10KΩ (1002) ±1%")
      (footprint "LC-0603_R")
      (description "贴片电阻")
      (libsource (lib "My_Library") (part "0603 10KΩ (1002) 1%"))
    )
    (comp (ref "R50")
      (value "0Ω (0R0) ±1%")
      (footprint "LC-0603_R")
      (description "贴片电阻")
      (libsource (lib "My_Library") (part "0603 0Ω (0R0) 1%"))
    )
    (comp (ref "R51")
      (value "0Ω (0R0) ±1%")
      (footprint "LC-0603_R")
      (description "贴片电阻")
      (libsource (lib "My_Library") (part "0603 0Ω (0R0) 1%"))
    )
    (comp (ref "R52")
      (value "0Ω (0R0) ±1%")
      (footprint "LC-0603_R")
      (description "贴片电阻")
      (libsource (lib "My_Library") (part "0603 0Ω (0R0) 1%"))
    )
    (comp (ref "R53")
      (value "0Ω (0R0) ±1%")
      (footprint "LC-0603_R")
      (description "贴片电阻")
      (libsource (lib "My_Library") (part "0603 0Ω (0R0) 1%"))
    )
    (comp (ref "R54")
      (value "100KΩ (1003) ±1%")
      (footprint "LC-0603_R")
      (description "贴片电阻")
      (libsource (lib "My_Library") (part "0603 100KΩ (1003) 1%"))
    )
    (comp (ref "R55")
      (value "100KΩ (1003) ±1%")
      (footprint "LC-0603_R")
      (description "贴片电阻")
      (libsource (lib "My_Library") (part "0603 100KΩ (1003) 1%"))
    )
    (comp (ref "R56")
      (value "470Ω (4700) ±1%")
      (footprint "LC-0603_R")
      (description "贴片电阻")
      (libsource (lib "My_Library") (part "0603 470Ω (4700) 1%"))
    )
    (comp (ref "R57")
      (value "100KΩ (1003) ±1%")
      (footprint "LC-0603_R")
      (description "贴片电阻")
      (libsource (lib "") (part "0603 100KΩ (1003) 1%_1"))
    )
    (comp (ref "R58")
      (value "43KΩ (4302) ±1%")
      (footprint "LC-0603_R")
      (description "贴片电阻")
      (libsource (lib "My_Library") (part "0603 43KΩ (4302) 1%"))
    )
    (comp (ref "R59")
      (value "3.3KΩ (3301) ±1%")
      (footprint "LC-0603_R")
      (description "贴片电阻")
      (libsource (lib "My_Library") (part "0603 3.3KΩ (3301) 1%"))
    )
    (comp (ref "R60")
      (value "10KΩ (1002) ±1%")
      (footprint "LC-0603_R")
      (description "贴片电阻")
      (libsource (lib "My_Library") (part "0603 10KΩ (1002) 1%"))
    )
    (comp (ref "R61")
      (value "24.9KΩ (2492) ±1%")
      (footprint "LC-0603_R")
      (description "贴片电阻")
      (libsource (lib "My_Library") (part "0603 24KΩ (2402) 1%"))
    )
    (comp (ref "R62")
      (value "10KΩ (1002) ±1%")
      (footprint "LC-0603_R")
      (description "贴片电阻")
      (libsource (lib "My_Library") (part "0603 10KΩ (1002) 1%"))
    )
    (comp (ref "R63")
      (value "10KΩ (1002) ±1%")
      (footprint "LC-0603_R")
      (description "贴片电阻")
      (libsource (lib "") (part "0603 10KΩ (1002) 1%_1"))
    )
    (comp (ref "R64")
      (value "0Ω (0R0) ±1%")
      (footprint "LC-0603_R")
      (description "贴片电阻")
      (libsource (lib "My_Library") (part "0603 0Ω (0R0) 1%"))
    )
    (comp (ref "R65")
      (value "105KΩ (1053) ±1%")
      (footprint "LC-0603_R")
      (description "贴片电阻")
      (libsource (lib "") (part "0603 10KΩ (1002) 1%_2"))
    )
    (comp (ref "R66")
      (value "120Ω (1200) ±1%")
      (footprint "LC-0603_R")
      (description "贴片电阻")
      (libsource (lib "My_Library") (part "0603 120Ω (1200) 1%"))
    )
    (comp (ref "R67")
      (value "10KΩ (1002) ±1%")
      (footprint "LC-0603_R")
      (description "贴片电阻")
      (libsource (lib "") (part "0603 10KΩ (1002) 1%_1"))
    )
    (comp (ref "R68")
      (value "1.2KΩ (1201) ±1%")
      (footprint "LC-0603_R")
      (description "贴片电阻")
      (libsource (lib "My_Library") (part "0603 1.2KΩ (1201) 1%"))
    )
    (comp (ref "R69")
      (value "10KΩ (1002) ±1%")
      (footprint "LC-0603_R")
      (description "贴片电阻")
      (libsource (lib "My_Library") (part "0603 10KΩ (1002) 1%"))
    )
    (comp (ref "R70")
      (value "120Ω (1200) ±1%")
      (footprint "LC-0603_R")
      (description "贴片电阻")
      (libsource (lib "My_Library") (part "0603 120Ω (1200) 1%"))
    )
    (comp (ref "R71")
      (value "1KΩ (1001) ±1%")
      (footprint "LC-0603_R")
      (description "贴片电阻")
      (libsource (lib "My_Library") (part "0603 1KΩ (1001) 1%"))
    )
    (comp (ref "R72")
      (value "1KΩ (1001) ±1%")
      (footprint "LC-0603_R")
      (description "贴片电阻")
      (libsource (lib "My_Library") (part "0603 1KΩ (1001) 1%"))
    )
    (comp (ref "R73")
      (value "1.2KΩ (1201) ±1%")
      (footprint "LC-0603_R")
      (description "贴片电阻")
      (libsource (lib "My_Library") (part "0603 1.2KΩ (1201) 1%"))
    )
    (comp (ref "R74")
      (value "10KΩ (1002) ±1%")
      (footprint "LC-0603_R")
      (description "贴片电阻")
      (libsource (lib "My_Library") (part "0603 10KΩ (1002) 1%"))
    )
    (comp (ref "R75")
      (value "0Ω (0R0) ±1%")
      (footprint "LC-0603_R")
      (description "贴片电阻")
      (libsource (lib "My_Library") (part "0603 0Ω (0R0) 1%"))
    )
    (comp (ref "R76")
      (value "0Ω (0R0) ±1%")
      (footprint "LC-0603_R")
      (description "贴片电阻")
      (libsource (lib "My_Library") (part "0603 0Ω (0R0) 1%"))
    )
    (comp (ref "R77")
      (value "100KΩ (1003) ±1%")
      (footprint "LC-0603_R")
      (description "贴片电阻")
      (libsource (lib "My_Library") (part "0603 100KΩ (1003) 1%"))
    )
    (comp (ref "R78")
      (value "10KΩ (1002) ±1%")
      (footprint "LC-0603_R")
      (description "贴片电阻")
      (libsource (lib "") (part "0603 10KΩ (1002) 1%_1"))
    )
    (comp (ref "R79")
      (value "1KΩ (1001) ±1%")
      (footprint "LC-0603_R")
      (description "贴片电阻")
      (libsource (lib "My_Library") (part "0603 1KΩ (1001) 1%"))
    )
    (comp (ref "R80")
      (value "1KΩ (1001) ±1%")
      (footprint "LC-0603_R")
      (description "贴片电阻")
      (libsource (lib "My_Library") (part "0603 1KΩ (1001) 1%"))
    )
    (comp (ref "R81")
      (value "120Ω (1200) ±1%")
      (footprint "LC-0603_R")
      (description "贴片电阻")
      (libsource (lib "My_Library") (part "0603 120Ω (1200) 1%"))
    )
    (comp (ref "R82")
      (value "100KΩ (1003) ±1%")
      (footprint "LC-0603_R")
      (description "贴片电阻")
      (libsource (lib "") (part "0603 100KΩ (1003) 1%_1"))
    )
    (comp (ref "R83")
      (value "100KΩ (1003) ±1%")
      (footprint "LC-0603_R")
      (description "贴片电阻")
      (libsource (lib "My_Library") (part "0603 100KΩ (1003) 1%"))
    )
    (comp (ref "R84")
      (value "100KΩ (1003) ±1%")
      (footprint "LC-0603_R")
      (description "贴片电阻")
      (libsource (lib "") (part "0603 100KΩ (1003) 1%_1"))
    )
    (comp (ref "R85")
      (value "1KΩ (1001) ±1%")
      (footprint "LC-0603_R")
      (description "贴片电阻")
      (libsource (lib "My_Library") (part "0603 1KΩ (1001) 1%"))
    )
    (comp (ref "R86")
      (value "1KΩ (1001) ±1%")
      (footprint "LC-0603_R")
      (description "贴片电阻")
      (libsource (lib "My_Library") (part "0603 1KΩ (1001) 1%"))
    )
    (comp (ref "R87")
      (value "20KΩ (2002) ±1%")
      (footprint "LC-0603_R")
      (description "贴片电阻")
      (libsource (lib "My_Library") (part "0603 20KΩ (2002) 1%"))
    )
    (comp (ref "R88")
      (value "3.3KΩ (3301) ±1%")
      (footprint "LC-0603_R")
      (description "贴片电阻")
      (libsource (lib "My_Library") (part "0603 3.3KΩ (3301) 1%"))
    )
    (comp (ref "R89")
      (value "1KΩ (1001) ±1%")
      (footprint "LC-0603_R")
      (description "贴片电阻")
      (libsource (lib "") (part "0603 1KΩ (1001) 1%_1"))
    )
    (comp (ref "R90")
      (value "1KΩ (1001) ±1%")
      (footprint "LC-0603_R")
      (description "贴片电阻")
      (libsource (lib "My_Library") (part "0603 1KΩ (1001) 1%"))
    )
    (comp (ref "R91")
      (value "1KΩ (1001) ±1%")
      (footprint "LC-0603_R")
      (description "贴片电阻")
      (libsource (lib "My_Library") (part "0603 1KΩ (1001) 1%"))
    )
    (comp (ref "R92")
      (value "1.2KΩ (1201) ±1%")
      (footprint "LC-0603_R")
      (description "贴片电阻")
      (libsource (lib "My_Library") (part "0603 1.2KΩ (1201) 1%"))
    )
    (comp (ref "R93")
      (value "10KΩ (1002) ±1%")
      (footprint "LC-0603_R")
      (description "贴片电阻")
      (libsource (lib "My_Library") (part "0603 10KΩ (1002) 1%"))
    )
    (comp (ref "R94")
      (value "10KΩ (1002) ±1%")
      (footprint "LC-0603_R")
      (description "贴片电阻")
      (libsource (lib "") (part "0603 10KΩ (1002) 1%_1"))
    )
    (comp (ref "R95")
      (value "120Ω (1200) ±1%")
      (footprint "LC-0603_R")
      (description "贴片电阻")
      (libsource (lib "My_Library") (part "0603 120Ω (1200) 1%"))
    )
    (comp (ref "R96")
      (value "10KΩ (1002) ±1%")
      (footprint "LC-0603_R")
      (description "贴片电阻")
      (libsource (lib "") (part "0603 10KΩ (1002) 1%_1"))
    )
    (comp (ref "R97")
      (value "10KΩ (1002) ±1%")
      (footprint "LC-0603_R")
      (description "贴片电阻")
      (libsource (lib "") (part "0603 10KΩ (1002) 1%_1"))
    )
    (comp (ref "R98")
      (value "10KΩ (1002) ±1%")
      (footprint "LC-0603_R")
      (description "贴片电阻")
      (libsource (lib "") (part "0603 10KΩ (1002) 1%_1"))
    )
    (comp (ref "R99")
      (value "0Ω (0R0) ±1%")
      (footprint "LC-0603_R")
      (description "贴片电阻")
      (libsource (lib "My_Library") (part "0603 0Ω (0R0) 1%"))
    )
    (comp (ref "R100")
      (value "0Ω (0R0) ±1%")
      (footprint "LC-0603_R")
      (description "贴片电阻")
      (libsource (lib "My_Library") (part "0603 0Ω (0R0) 1%"))
    )
    (comp (ref "R101")
      (value "100KΩ (1003) ±1%")
      (footprint "LC-0603_R")
      (description "贴片电阻")
      (libsource (lib "") (part "0603 100KΩ (1003) 1%_1"))
    )
    (comp (ref "R102")
      (value "0Ω (0R0) ±1%")
      (footprint "LC-0603_R")
      (description "贴片电阻")
      (libsource (lib "") (part "0603 0Ω (0R0) 1%_1"))
    )
    (comp (ref "R103")
      (value "22Ω (22R0) ±1%")
      (footprint "LC-0603_R")
      (description "贴片电阻")
      (libsource (lib "My_Library") (part "0603 22Ω (22R0) 1%"))
    )
    (comp (ref "R104")
      (value "22Ω (22R0) ±1%")
      (footprint "LC-0603_R")
      (description "贴片电阻")
      (libsource (lib "My_Library") (part "0603 22Ω (22R0) 1%"))
    )
    (comp (ref "R105")
      (value "0Ω (0R0) ±1%")
      (footprint "LC-0603_R")
      (description "贴片电阻")
      (libsource (lib "My_Library") (part "0603 0Ω (0R0) 1%"))
    )
    (comp (ref "R106")
      (value "1KΩ (1001) ±1%")
      (footprint "LC-0603_R")
      (description "贴片电阻")
      (libsource (lib "My_Library") (part "0603 1KΩ (1001) 1%"))
    )
    (comp (ref "R107")
      (value "3.3KΩ (3301) ±1%")
      (footprint "LC-0603_R")
      (description "贴片电阻")
      (libsource (lib "My_Library") (part "0603 3.3KΩ (3301) 1%"))
    )
    (comp (ref "R108")
      (value "10KΩ (1002) ±1%")
      (footprint "LC-0603_R")
      (description "贴片电阻")
      (libsource (lib "My_Library") (part "0603 10KΩ (1002) 1%"))
    )
    (comp (ref "R109")
      (value "0Ω (0R0) ±1%")
      (footprint "LC-0603_R")
      (description "贴片电阻")
      (libsource (lib "My_Library") (part "0603 0Ω (0R0) 1%"))
    )
    (comp (ref "R110")
      (value "3.3KΩ (3301) ±1%")
      (footprint "LC-0603_R")
      (description "贴片电阻")
      (libsource (lib "My_Library") (part "0603 3.3KΩ (3301) 1%"))
    )
    (comp (ref "R111")
      (value "1KΩ (1001) ±1%")
      (footprint "LC-0603_R")
      (description "贴片电阻")
      (libsource (lib "My_Library") (part "0603 1KΩ (1001) 1%"))
    )
    (comp (ref "R112")
      (value "3.3KΩ (3301) ±1%")
      (footprint "LC-0603_R")
      (description "贴片电阻")
      (libsource (lib "My_Library") (part "0603 3.3KΩ (3301) 1%"))
    )
    (comp (ref "R113")
      (value "3.3KΩ (3301) ±1%")
      (footprint "LC-0603_R")
      (description "贴片电阻")
      (libsource (lib "My_Library") (part "0603 3.3KΩ (3301) 1%"))
    )
    (comp (ref "R114")
      (value "10KΩ (1002) ±1%")
      (footprint "LC-0603_R")
      (description "贴片电阻")
      (libsource (lib "") (part "0603 10KΩ (1002) 1%_1"))
    )
    (comp (ref "R115")
      (value "10KΩ (1002) ±1%")
      (footprint "LC-0603_R")
      (description "贴片电阻")
      (libsource (lib "My_Library") (part "0603 10KΩ (1002) 1%"))
    )
    (comp (ref "R116")
      (value "10KΩ (1002) ±1%")
      (footprint "LC-0603_R")
      (description "贴片电阻")
      (libsource (lib "My_Library") (part "0603 10KΩ (1002) 1%"))
    )
    (comp (ref "R117")
      (value "1KΩ (1001) ±1%")
      (footprint "LC-0603_R")
      (description "贴片电阻")
      (libsource (lib "My_Library") (part "0603 1KΩ (1001) 1%"))
    )
    (comp (ref "RCS1")
      (value "0.4R")
      (footprint "R-2512")
      (description "贴片电阻")
      (fields (field (name "PUBLISHER") "Altium Limited"))
      (libsource (lib "Miscellaneous Devices") (part "Res2"))
    )
    (comp (ref "RCS2")
      (value "0.4R")
      (footprint "R-2512")
      (description "贴片电阻")
      (fields (field (name "PUBLISHER") "Altium Limited"))
      (libsource (lib "Miscellaneous Devices") (part "Res2"))
    )
    (comp (ref "S1")
      (value "SW-PB")
      (footprint "JXT-2-l")
      (description "微型按键开关")
      (libsource (lib "杂元件库") (part "SW-PB"))
    )
    (comp (ref "S2")
      (value "SW-PB")
      (footprint "JXT-2-l")
      (description "微型按键开关")
      (libsource (lib "杂元件库") (part "SW-PB"))
    )
    (comp (ref "S3")
      (value "SW-PB")
      (footprint "轻触(3*6*4.3)")
      (description "微型按键开关")
      (libsource (lib "杂元件库") (part "SW-PB"))
    )
    (comp (ref "TF-1")
      (value "3.3V")
      (footprint "TEST_POINT")
      (description "测试点")
      (libsource (lib "InforCenterBoard") (part "TEST_POINT"))
    )
    (comp (ref "U1")
      (value "RS485模块")
      (footprint "RS485MOD")
      (description "TTL转RS485模块")
      (libsource (lib "AirPlaneSign") (part "RS485模块"))
    )
    (comp (ref "U2")
      (value "XL6019")
      (footprint "TO-263-5")
      (description "DC-DC芯片")
      (libsource (lib "Emergency lighting") (part "XL6019"))
    )
    (comp (ref "U3")
      (value "74HC04D")
      (footprint "SOIC-14_150mil")
      (description "6路施密特触发反相器")
      (fields (field (name "PUBLISHER") "Altium Limited"))
      (libsource (lib "AirPlaneSign") (part "74HC14"))
    )
    (comp (ref "U4")
      (value "MAX485ESA")
      (footprint "SOP-8_150mil")
      (description "RS485收发芯片")
      (libsource (lib "AirPlaneSign") (part "MAX485ESA"))
    )
    (comp (ref "U5")
      (value "SIM868-DS")
      (footprint "SIM868")
      (description "GPRS+GPS")
      (libsource (lib "AirPlaneSign") (part "SIM868-DS"))
    )
    (comp (ref "U6")
      (value "PC817")
      (footprint "PC817")
      (description "光藕")
      (libsource (lib "ControllerBoard") (part "Q817"))
    )
    (comp (ref "U7")
      (value "RT9161-50GV")
      (footprint "SOT-23-3")
      (description "LDO")
      (libsource (lib "AirPlaneSign") (part "RT9161-50GV"))
    )
    (comp (ref "U8")
      (value "CN3722")
      (footprint "TSSOP-16")
      (description "充电管理")
      (fields (field (name "PUBLISHER") "Altium Limited"))
      (libsource (lib "AirPlaneSign") (part "CN3722"))
    )
    (comp (ref "U9")
      (value "E32-TTL-100S1")
      (footprint "E32-TTL-100S1")
      (description "LOAR-UART模块")
      (libsource (lib "AirPlaneSign") (part "E32-TTL-100S1"))
    )
    (comp (ref "U10")
      (value "CR2032")
      (footprint "CR2032 - 1")
      (description "CR2032电池盒/电池座")
      (libsource (lib "AirPlaneSign") (part "BAT"))
    )
    (comp (ref "U11")
      (value "STM32F103RCT6")
      (footprint "LQFP-64_10x10x05P")
      (description "单片机")
      (libsource (lib "AirPlaneSign") (part "STM32F103RCT6"))
    )
    (comp (ref "U12")
      (value "立式micro 5p USB插座")
      (footprint "USB插座 micro 5p")
      (libsource (lib "AirPlaneSign") (part "USB_micro_5p"))
    )
    (comp (ref "U13")
      (value "74LVC125APW")
      (footprint "TSSOP-14")
      (description "74系列逻辑芯片")
      (fields
        (field (name "BOM_MANUFACTURER PART") "74LVC125APW,118")
        (field (name "BOM_SUPPLIER PART") "C6059")
      )
      (libsource (lib "AirPlaneSign") (part "74LVC125APW"))
    )
    (comp (ref "U14")
      (value "TF-002T-15")
      (footprint "TF-002T-15")
      (description "TF002 TF卡座 高度1.5")
      (fields (field (name "BOM_SUPPLIER PART") "C125616") (field (name "CONTRIBUTOR") "LCSC"))
      (libsource (lib "AirPlaneSign") (part "TF-002T-15"))
    )
    (comp (ref "V1")
      (value "AO3401A")
      (footprint "SOT-23-3L")
      (description "MOS(场效应管)")
      (libsource (lib "*") (part "MOSFET P"))
    )
    (comp (ref "V2")
      (value "AO3401A")
      (footprint "SOT-23-3L")
      (description "MOS(场效应管)")
      (libsource (lib "*") (part "MOSFET P"))
    )
    (comp (ref "V3")
      (value "AO3401A")
      (footprint "SOT-23-3L")
      (description "MOS(场效应管)")
      (libsource (lib "*") (part "MOSFET P"))
    )
    (comp (ref "XS1")
      (value "WJ2EDGR-5.08-2")
      (footprint "WJ2EDGR-5.08-2")
      (description "接线座 - 接头")
      (fields (field (name "PUBLISHER") "Altium Limited"))
      (libsource (lib "") (part "WJ2EDGR-5.08-2_2"))
    )
    (comp (ref "XS2")
      (value "WJ2EDGR-5.08-2")
      (footprint "WJ2EDGR-5.08-2")
      (description "接线座 - 接头")
      (fields (field (name "PUBLISHER") "Altium Limited"))
      (libsource (lib "AirPlaneSign") (part "WJ2EDGR-5.08-2"))
    )
    (comp (ref "XS3")
      (value "WJ2EDGR-5.08-2")
      (footprint "WJ2EDGR-5.08-2")
      (description "接线座 - 接头")
      (fields (field (name "PUBLISHER") "Altium Limited"))
      (libsource (lib "") (part "WJ2EDGR-5.08-2_2"))
    )
    (comp (ref "XS4")
      (value "WJ2EDGR-5.08-2")
      (footprint "WJ2EDGR-5.08-2")
      (description "接线座 - 接头")
      (fields (field (name "PUBLISHER") "Altium Limited"))
      (libsource (lib "") (part "WJ2EDGR-5.08-2_1"))
    )
    (comp (ref "XS5")
      (value "DS1138-02-06SS4BOR")
      (footprint "SIM-1")
      (description "SIM_卡槽")
      (libsource (lib "AirPlaneSign") (part "SIM_卡槽"))
    )
    (comp (ref "XS6")
      (value "1.27 4PIN")
      (footprint "JXT-4")
      (description "1.27卧式贴片针座")
      (fields (field (name "PUBLISHER") "Altium Limited"))
      (libsource (lib "Miscellaneous Connectors") (part "Header 4"))
    )
    (comp (ref "XS7")
      (value "1.25X4")
      (footprint "JXT-5")
      (description "1.27卧式贴片针座")
      (fields (field (name "PUBLISHER") "Altium Limited"))
      (libsource (lib "AirPlaneSign") (part "Header 5"))
    )
    (comp (ref "Y1")
      (value "32.768k")
      (footprint "3215_32.768K")
      (description "Crystal")
      (libsource (lib "Device Library") (part "CRYSTAL"))
    )
    (comp (ref "Y2")
      (value "8M")
      (footprint "SMD-5032_4P")
      (description "晶振")
      (fields (field (name "PUBLISHER") "Altium Limited"))
      (libsource (lib "AirPlaneSign") (part "CRYSTAL"))
    )
  )
  (nets
    (net (code "1") (name "+3.3V") (class "Default")
      (node (ref "C8") (pin "1") (pinfunction "1_1") (pintype "passive"))
      (node (ref "R1") (pin "2") (pinfunction "2_2") (pintype "passive"))
      (node (ref "R21") (pin "1") (pinfunction "1_1") (pintype "passive"))
      (node (ref "R23") (pin "1") (pinfunction "1_1") (pintype "passive"))
      (node (ref "R9") (pin "2") (pinfunction "2_2") (pintype "passive"))
      (node (ref "U1") (pin "1") (pinfunction "VCC_1") (pintype "passive"))
      (node (ref "U3") (pin "14") (pinfunction "VCC_14") (pintype "passive"))
      (node (ref "U4") (pin "8") (pinfunction "VCC_8") (pintype "power_in"))
    )
    (net (code "2") (name "+5V") (class "Default")
      (node (ref "3") (pin "1") (pinfunction "1_1") (pintype "passive"))
      (node (ref "C1") (pin "2") (pinfunction "2_2") (pintype "passive"))
      (node (ref "C23") (pin "2") (pinfunction "2_2") (pintype "passive"))
      (node (ref "C24") (pin "2") (pinfunction "2_2") (pintype "passive"))
      (node (ref "C25") (pin "1") (pinfunction "1_1") (pintype "passive"))
      (node (ref "IC1") (pin "1") (pinfunction "VIN_1") (pintype "passive"))
      (node (ref "IC1") (pin "3") (pinfunction "EN_3") (pintype "passive"))
      (node (ref "L3") (pin "2") (pinfunction "2_2") (pintype "passive"))
      (node (ref "R100") (pin "1") (pinfunction "1_1") (pintype "passive"))
      (node (ref "R40") (pin "1") (pinfunction "1_1") (pintype "passive"))
      (node (ref "R57") (pin "1") (pinfunction "1_1") (pintype "passive"))
      (node (ref "R84") (pin "1") (pinfunction "1_1") (pintype "passive"))
      (node (ref "V2") (pin "2") (pinfunction "S_2") (pintype "input"))
      (node (ref "V3") (pin "2") (pinfunction "S_2") (pintype "input"))
    )
    (net (code "3") (name "+12V") (class "Default")
      (node (ref "J1") (pin "1") (pinfunction "1_1") (pintype "passive"))
      (node (ref "J2") (pin "1") (pinfunction "1_1") (pintype "passive"))
      (node (ref "J3") (pin "1") (pinfunction "1_1") (pintype "passive"))
      (node (ref "J4") (pin "1") (pinfunction "1_1") (pintype "passive"))
      (node (ref "J5") (pin "1") (pinfunction "1_1") (pintype "passive"))
      (node (ref "J6") (pin "1") (pinfunction "1_1") (pintype "passive"))
      (node (ref "J7") (pin "1") (pinfunction "1_1") (pintype "passive"))
      (node (ref "J8") (pin "1") (pinfunction "1_1") (pintype "passive"))
      (node (ref "R31") (pin "2") (pinfunction "2_2") (pintype "passive"))
    )
    (net (code "4") (name "+Vout") (class "Default")
      (node (ref "C13") (pin "1") (pinfunction "1_1") (pintype "passive"))
      (node (ref "C14") (pin "2") (pinfunction "2_2") (pintype "passive"))
      (node (ref "C15") (pin "2") (pinfunction "2_2") (pintype "passive"))
      (node (ref "Q1") (pin "3") (pinfunction "S_3") (pintype "input"))
      (node (ref "R50") (pin "1") (pinfunction "1_1") (pintype "passive"))
      (node (ref "R6") (pin "2") (pinfunction "2_2") (pintype "passive"))
      (node (ref "XS2") (pin "2") (pinfunction "2_2") (pintype "passive"))
    )
    (net (code "5") (name "/1Y") (class "Default")
      (node (ref "R13") (pin "2") (pinfunction "2_2") (pintype "passive"))
      (node (ref "U3") (pin "11") (pinfunction "5Y_11") (pintype "passive"))
      (node (ref "U3") (pin "2") (pinfunction "1Y_2") (pintype "passive"))
    )
    (net (code "6") (name "/2A") (class "Default")
      (node (ref "U3") (pin "3") (pinfunction "2A_3") (pintype "passive"))
      (node (ref "U3") (pin "8") (pinfunction "4A_8") (pintype "passive"))
    )
    (net (code "7") (name "/12V_PWR") (class "Default")
      (node (ref "R11") (pin "1") (pinfunction "1_1") (pintype "passive"))
      (node (ref "U11") (pin "37") (pinfunction "PC6/TIM3_CH1_37") (pintype "passive"))
    )
    (net (code "8") (name "/485RX") (class "Default")
      (node (ref "R3") (pin "1") (pinfunction "1_1") (pintype "passive"))
      (node (ref "U11") (pin "17") (pinfunction "PA3/USART2_RX_/ADC12_IN3/TIM2_CH4_17") (pintype "passive"))
    )
    (net (code "9") (name "/485TX") (class "Default")
      (node (ref "R2") (pin "1") (pinfunction "1_1") (pintype "passive"))
      (node (ref "U11") (pin "16") (pinfunction "PA2/USART2_TX/ADC12_IN2/TIM2_CH3_16") (pintype "passive"))
    )
    (net (code "10") (name "/485_PWR_EN") (class "Default")
      (node (ref "R39") (pin "1") (pinfunction "1_1") (pintype "passive"))
      (node (ref "U11") (pin "38") (pinfunction "PC7/TIM3_CH2_38") (pintype "passive"))
    )
    (net (code "11") (name "/A") (class "Default")
      (node (ref "F4") (pin "2") (pinfunction "2_2") (pintype "passive"))
      (node (ref "J1") (pin "3") (pinfunction "3_3") (pintype "passive"))
      (node (ref "J2") (pin "3") (pinfunction "3_3") (pintype "passive"))
      (node (ref "J3") (pin "3") (pinfunction "3_3") (pintype "passive"))
      (node (ref "J4") (pin "3") (pinfunction "3_3") (pintype "passive"))
      (node (ref "J5") (pin "3") (pinfunction "3_3") (pintype "passive"))
      (node (ref "J6") (pin "3") (pinfunction "3_3") (pintype "passive"))
      (node (ref "J7") (pin "3") (pinfunction "3_3") (pintype "passive"))
      (node (ref "J8") (pin "3") (pinfunction "3_3") (pintype "passive"))
      (node (ref "R5") (pin "2") (pinfunction "2_2") (pintype "passive"))
      (node (ref "U1") (pin "7") (pinfunction "A+_7") (pintype "passive"))
    )
    (net (code "12") (name "/ANT_PWR_EN") (class "Default")
      (node (ref "R24") (pin "1") (pinfunction "1_1") (pintype "passive"))
      (node (ref "U11") (pin "53") (pinfunction "PC12/USART3_CK_53") (pintype "passive"))
    )
    (net (code "13") (name "/AUX") (class "Default")
      (node (ref "Q13") (pin "1") (pinfunction "B_1") (pintype "passive"))
      (node (ref "R77") (pin "1") (pinfunction "1_1") (pintype "passive"))
      (node (ref "U9") (pin "5") (pinfunction "AUX_5") (pintype "passive"))
    )
    (net (code "14") (name "/B") (class "Default")
      (node (ref "F3") (pin "2") (pinfunction "2_2") (pintype "passive"))
      (node (ref "J1") (pin "2") (pinfunction "2_2") (pintype "passive"))
      (node (ref "J2") (pin "2") (pinfunction "2_2") (pintype "passive"))
      (node (ref "J3") (pin "2") (pinfunction "2_2") (pintype "passive"))
      (node (ref "J4") (pin "2") (pinfunction "2_2") (pintype "passive"))
      (node (ref "J5") (pin "2") (pinfunction "2_2") (pintype "passive"))
      (node (ref "J6") (pin "2") (pinfunction "2_2") (pintype "passive"))
      (node (ref "J7") (pin "2") (pinfunction "2_2") (pintype "passive"))
      (node (ref "J8") (pin "2") (pinfunction "2_2") (pintype "passive"))
      (node (ref "R5") (pin "1") (pinfunction "1_1") (pintype "passive"))
      (node (ref "U1") (pin "6") (pinfunction "B-_6") (pintype "passive"))
    )
    (net (code "15") (name "/BAT_V") (class "Default")
      (node (ref "C54") (pin "2") (pinfunction "2_2") (pintype "passive"))
      (node (ref "R83") (pin "1") (pinfunction "1_1") (pintype "passive"))
      (node (ref "R87") (pin "2") (pinfunction "2_2") (pintype "passive"))
      (node (ref "U11") (pin "27") (pinfunction "PB1/ADC12_IN9/TIM3_CH4/TIM1_CH3N_27") (pintype "passive"))
    )
    (net (code "16") (name "/BOOT0") (class "Default")
      (node (ref "R116") (pin "2") (pinfunction "2_2") (pintype "passive"))
      (node (ref "U11") (pin "60") (pinfunction "BOOT0_60") (pintype "passive"))
    )
    (net (code "17") (name "/BOOT1") (class "Default")
      (node (ref "R115") (pin "1") (pinfunction "1_1") (pintype "passive"))
      (node (ref "U11") (pin "28") (pinfunction "PB2-BOOT1_28") (pintype "passive"))
    )
    (net (code "18") (name "/CS") (class "Default")
      (node (ref "R113") (pin "2") (pinfunction "2_2") (pintype "passive"))
      (node (ref "U11") (pin "33") (pinfunction "PB12/SPI2_NSS/I2C2_SMBA/USART3_CK/TIM1_BKIN_33") (pintype "passive"))
    )
    (net (code "19") (name "/CS-CARD") (class "Default")
      (node (ref "U13") (pin "8") (pinfunction "3Y_8") (pintype "passive"))
      (node (ref "U14") (pin "2") (pinfunction "CD/DAT3_2") (pintype "passive"))
    )
    (net (code "20") (name "/D+") (class "Default")
      (node (ref "D26") (pin "A") (pinfunction "A_A") (pintype "passive"))
      (node (ref "R104") (pin "1") (pinfunction "1_1") (pintype "passive"))
      (node (ref "R111") (pin "1") (pinfunction "1_1") (pintype "passive"))
      (node (ref "U12") (pin "3") (pinfunction "3_3") (pintype "passive"))
    )
    (net (code "21") (name "/D-") (class "Default")
      (node (ref "R103") (pin "1") (pinfunction "1_1") (pintype "passive"))
      (node (ref "U12") (pin "2") (pinfunction "2_2") (pintype "passive"))
    )
    (net (code "22") (name "/D0") (class "Default")
      (node (ref "R110") (pin "2") (pinfunction "2_2") (pintype "passive"))
      (node (ref "U14") (pin "7") (pinfunction "DAT0_7") (pintype "passive"))
    )
    (net (code "23") (name "/DI") (class "Default")
      (node (ref "U13") (pin "3") (pinfunction "1Y_3") (pintype "passive"))
      (node (ref "U14") (pin "3") (pinfunction "CMD_3") (pintype "passive"))
    )
    (net (code "24") (name "/END_CHG") (class "Default")
      (node (ref "LED1") (pin "1") (pinfunction "A_1") (pintype "passive"))
      (node (ref "U8") (pin "5") (pinfunction "~{DONE}_5") (pintype "passive"))
    )
    (net (code "25") (name "/EX_POW") (class "Default")
      (node (ref "R42") (pin "2") (pinfunction "2_2") (pintype "passive"))
      (node (ref "U11") (pin "39") (pinfunction "PC8/TIM3_CH3_39") (pintype "passive"))
      (node (ref "U6") (pin "3") (pinfunction "Emitter_3") (pintype "passive"))
    )
    (net (code "26") (name "/GNSS_EN") (class "Default")
      (node (ref "R27") (pin "2") (pinfunction "2_2") (pintype "passive"))
      (node (ref "U5") (pin "59") (pinfunction "GNSS_EN_59") (pintype "passive"))
    )
    (net (code "27") (name "/GPRS_PWRKEY") (class "Default")
      (node (ref "R45") (pin "1") (pinfunction "1_1") (pintype "passive"))
      (node (ref "U11") (pin "52") (pinfunction "PC11/USART3_RX_52") (pintype "passive"))
    )
    (net (code "28") (name "/GPRS_PWR_EN") (class "Default")
      (node (ref "R59") (pin "1") (pinfunction "1_1") (pintype "passive"))
      (node (ref "U11") (pin "56") (pinfunction "PB4/JNTRST/TIM3_CH1/SPI1_MISO_56") (pintype "passive"))
    )
    (net (code "29") (name "/GPRS_RST") (class "Default")
      (node (ref "Q5") (pin "3") (pinfunction "C_3") (pintype "passive"))
      (node (ref "R49") (pin "2") (pinfunction "2_2") (pintype "passive"))
      (node (ref "S3") (pin "2") (pinfunction "2_2") (pintype "passive"))
      (node (ref "U11") (pin "51") (pinfunction "PC10/USART3_TX_51") (pintype "passive"))
      (node (ref "U5") (pin "39") (pinfunction "PWRKEY_39") (pintype "passive"))
    )
    (net (code "30") (name "/GPRS_RX") (class "Default")
      (node (ref "D14") (pin "2") (pinfunction "K_2") (pintype "passive"))
      (node (ref "R22") (pin "2") (pinfunction "2_2") (pintype "passive"))
      (node (ref "U11") (pin "30") (pinfunction "PB11/I2C2_SDA/USART3_RX/TIM2_CH4_30") (pintype "passive"))
    )
    (net (code "31") (name "/GPRS_TX") (class "Default")
      (node (ref "D15") (pin "2") (pinfunction "K_2") (pintype "passive"))
      (node (ref "U11") (pin "29") (pinfunction "PB10/I2C2_SCL/USART3_TX/TIM2_CH3_29") (pintype "passive"))
    )
    (net (code "32") (name "/GPS_RXD") (class "Default")
      (node (ref "R29") (pin "1") (pinfunction "1_1") (pintype "passive"))
      (node (ref "U5") (pin "22") (pinfunction "UART2_TXD_22") (pintype "passive"))
    )
    (net (code "33") (name "/GPS_TXD") (class "Default")
      (node (ref "R30") (pin "1") (pinfunction "1_1") (pintype "passive"))
      (node (ref "U5") (pin "23") (pinfunction "UART2_RXD_23") (pintype "passive"))
    )
    (net (code "34") (name "/I1") (class "Default")
      (node (ref "Q9") (pin "3") (pinfunction "C/A_3") (pintype "power_in"))
      (node (ref "R69") (pin "2") (pinfunction "2_2") (pintype "passive"))
      (node (ref "U11") (pin "24") (pinfunction "PC4/ADC12_IN14_24") (pintype "passive"))
    )
    (net (code "35") (name "/I2") (class "Default")
      (node (ref "Q10") (pin "3") (pinfunction "C/A_3") (pintype "power_in"))
      (node (ref "R74") (pin "2") (pinfunction "2_2") (pintype "passive"))
      (node (ref "U11") (pin "23") (pinfunction "PA7/SPI1_MISI_/TIM1_CH1N/ADC12_IN7/TIM3_CH2_23") (pintype "passive"))
    )
    (net (code "36") (name "/I3") (class "Default")
      (node (ref "Q14") (pin "3") (pinfunction "C/A_3") (pintype "power_in"))
      (node (ref "R93") (pin "2") (pinfunction "2_2") (pintype "passive"))
      (node (ref "U11") (pin "22") (pinfunction "PA6/SPI1_MISO_/TIM1_BKIN/ADC12_IN6/TIM3_CH1_22") (pintype "passive"))
    )
    (net (code "37") (name "/IIN1") (class "Default")
      (node (ref "C48") (pin "2") (pinfunction "2_2") (pintype "passive"))
      (node (ref "P2") (pin "2") (pinfunction "2_2") (pintype "passive"))
      (node (ref "R68") (pin "2") (pinfunction "2_2") (pintype "passive"))
      (node (ref "R69") (pin "1") (pinfunction "1_1") (pintype "passive"))
      (node (ref "R70") (pin "2") (pinfunction "2_2") (pintype "passive"))
    )
    (net (code "38") (name "/IIN2") (class "Default")
      (node (ref "C50") (pin "2") (pinfunction "2_2") (pintype "passive"))
      (node (ref "P3") (pin "2") (pinfunction "2_2") (pintype "passive"))
      (node (ref "R73") (pin "2") (pinfunction "2_2") (pintype "passive"))
      (node (ref "R74") (pin "1") (pinfunction "1_1") (pintype "passive"))
      (node (ref "R81") (pin "2") (pinfunction "2_2") (pintype "passive"))
    )
    (net (code "39") (name "/IIN3") (class "Default")
      (node (ref "C57") (pin "2") (pinfunction "2_2") (pintype "passive"))
      (node (ref "P4") (pin "2") (pinfunction "2_2") (pintype "passive"))
      (node (ref "R92") (pin "2") (pinfunction "2_2") (pintype "passive"))
      (node (ref "R93") (pin "1") (pinfunction "1_1") (pintype "passive"))
      (node (ref "R95") (pin "2") (pinfunction "2_2") (pintype "passive"))
    )
    (net (code "40") (name "/K1") (class "Default")
      (node (ref "R46") (pin "2") (pinfunction "2_2") (pintype "passive"))
      (node (ref "S2") (pin "2") (pinfunction "2_2") (pintype "passive"))
      (node (ref "U11") (pin "20") (pinfunction "PA4/SPI1_NSS/_USART2_CK/ADC12_IN4_20") (pintype "passive"))
    )
    (net (code "41") (name "/K2") (class "Default")
      (node (ref "R34") (pin "2") (pinfunction "2_2") (pintype "passive"))
      (node (ref "S1") (pin "2") (pinfunction "2_2") (pintype "passive"))
      (node (ref "U11") (pin "21") (pinfunction "PA5/SPI1_SCK_/ADC12_IN5_21") (pintype "passive"))
    )
    (net (code "42") (name "/LED1") (class "Default")
      (node (ref "R79") (pin "1") (pinfunction "1_1") (pintype "passive"))
      (node (ref "U11") (pin "10") (pinfunction "PC2/ADC12_IN12_10") (pintype "passive"))
    )
    (net (code "43") (name "/LED2") (class "Default")
      (node (ref "R90") (pin "1") (pinfunction "1_1") (pintype "passive"))
      (node (ref "U11") (pin "11") (pinfunction "PC3/ADC12_IN13_11") (pintype "passive"))
    )
    (net (code "44") (name "/LED3") (class "Default")
      (node (ref "R80") (pin "1") (pinfunction "1_1") (pintype "passive"))
      (node (ref "U11") (pin "8") (pinfunction "PC0/ADC12_IN10_8") (pintype "passive"))
    )
    (net (code "45") (name "/LED4") (class "Default")
      (node (ref "R91") (pin "1") (pinfunction "1_1") (pintype "passive"))
      (node (ref "U11") (pin "9") (pinfunction "PC1/ADC12_IN11_9") (pintype "passive"))
    )
    (net (code "46") (name "/LORA_PWR") (class "Default")
      (node (ref "R88") (pin "1") (pinfunction "1_1") (pintype "passive"))
      (node (ref "U11") (pin "61") (pinfunction "PB8/I2C_1_SCL/_CAN_RX/TIM4_CH3_61") (pintype "passive"))
    )
    (net (code "47") (name "/LoRa_AUX") (class "Default")
      (node (ref "Q13") (pin "3") (pinfunction "C_3") (pintype "passive"))
      (node (ref "R78") (pin "1") (pinfunction "1_1") (pintype "passive"))
      (node (ref "U11") (pin "14") (pinfunction "PA0/WKUP/USART2_CTS/ADC12_IN0_/TIM2_CH1_ETR_14") (pintype "passive"))
    )
    (net (code "48") (name "/LoRa_M0") (class "Default")
      (node (ref "U11") (pin "54") (pinfunction "PD2/TIM3_ETR_54") (pintype "passive"))
      (node (ref "U9") (pin "1") (pinfunction "M0_1") (pintype "passive"))
    )
    (net (code "49") (name "/LoRa_M1") (class "Default")
      (node (ref "U11") (pin "55") (pinfunction "PB3/JTDO/TRACESWO/TIM2_CH2/SPI1_SCK_55") (pintype "passive"))
      (node (ref "U9") (pin "2") (pinfunction "M1_2") (pintype "passive"))
    )
    (net (code "50") (name "/LoRa_RX") (class "Default")
      (node (ref "R109") (pin "2") (pinfunction "2_2") (pintype "passive"))
      (node (ref "U9") (pin "3") (pinfunction "RXD_3") (pintype "passive"))
      (node (ref "XS6") (pin "3") (pinfunction "3_3") (pintype "passive"))
    )
    (net (code "51") (name "/LoRa_TX") (class "Default")
      (node (ref "R105") (pin "2") (pinfunction "2_2") (pintype "passive"))
      (node (ref "R89") (pin "2") (pinfunction "2_2") (pintype "passive"))
      (node (ref "U9") (pin "4") (pinfunction "TXD_4") (pintype "passive"))
      (node (ref "XS6") (pin "2") (pinfunction "2_2") (pintype "passive"))
    )
    (net (code "52") (name "/MISO") (class "Default")
      (node (ref "U11") (pin "35") (pinfunction "PB14/SPI2_MISO/TIM1_CH2N/USART3_RTS_35") (pintype "passive"))
      (node (ref "U13") (pin "11") (pinfunction "4Y_11") (pintype "passive"))
    )
    (net (code "53") (name "/MOSI") (class "Default")
      (node (ref "R107") (pin "1") (pinfunction "1_1") (pintype "passive"))
      (node (ref "U11") (pin "36") (pinfunction "PB15/SPI2_MOSI/TIM1_CH3N_36") (pintype "passive"))
    )
    (net (code "54") (name "/NETLIGHT") (class "Default")
      (node (ref "R26") (pin "1") (pinfunction "1_1") (pintype "passive"))
      (node (ref "U11") (pin "50") (pinfunction "PA15/JTDI/TIM2_CH1_CH1/_SPI1_NSS_50") (pintype "passive"))
      (node (ref "U5") (pin "41") (pinfunction "NETLIGHT_41") (pintype "passive"))
    )
    (net (code "55") (name "/ON_CHG") (class "Default")
      (node (ref "LED1") (pin "3") (pinfunction "A_3") (pintype "passive"))
      (node (ref "U8") (pin "4") (pinfunction "~{CHRG}_4") (pintype "passive"))
    )
    (net (code "56") (name "/RESET") (class "Default")
      (node (ref "C71") (pin "1") (pinfunction "1_1") (pintype "passive"))
      (node (ref "R108") (pin "2") (pinfunction "2_2") (pintype "passive"))
      (node (ref "U11") (pin "7") (pinfunction "NRST_7") (pintype "passive"))
      (node (ref "XS7") (pin "2") (pinfunction "2_2") (pintype "passive"))
    )
    (net (code "57") (name "/RTC_SCL") (class "Default")
      (node (ref "IC8") (pin "6") (pinfunction "SCL_6") (pintype "passive"))
      (node (ref "R97") (pin "1") (pinfunction "1_1") (pintype "passive"))
      (node (ref "U11") (pin "58") (pinfunction "PB6/USART1_TX/I2C1_SCL_/TIM4_CH1_58") (pintype "passive"))
    )
    (net (code "58") (name "/RTC_SDA") (class "Default")
      (node (ref "IC8") (pin "5") (pinfunction "SDA_5") (pintype "passive"))
      (node (ref "R98") (pin "1") (pinfunction "1_1") (pintype "passive"))
      (node (ref "U11") (pin "59") (pinfunction "PB7/USART1_RX/I2C1_SDA_/TIM4_CH2_59") (pintype "passive"))
    )
    (net (code "59") (name "/RXD") (class "Default")
      (node (ref "R3") (pin "2") (pinfunction "2_2") (pintype "passive"))
      (node (ref "U1") (pin "3") (pinfunction "RXD_3") (pintype "passive"))
      (node (ref "U3") (pin "4") (pinfunction "2Y_4") (pintype "passive"))
      (node (ref "U3") (pin "5") (pinfunction "3A_5") (pintype "passive"))
    )
    (net (code "60") (name "/SCK") (class "Default")
      (node (ref "R112") (pin "1") (pinfunction "1_1") (pintype "passive"))
      (node (ref "U11") (pin "34") (pinfunction "PB13/SPI2_SCK/USART3_CTS/_TIM1_CH1N_34") (pintype "passive"))
    )
    (net (code "61") (name "/SCLK") (class "Default")
      (node (ref "U13") (pin "6") (pinfunction "2Y_6") (pintype "passive"))
      (node (ref "U14") (pin "5") (pinfunction "CLX_5") (pintype "passive"))
    )
    (net (code "62") (name "/SIM800_RX") (class "Default")
      (node (ref "D15") (pin "1") (pinfunction "A_1") (pintype "passive"))
      (node (ref "P1") (pin "2") (pinfunction "2_2") (pintype "passive"))
      (node (ref "R25") (pin "1") (pinfunction "1_1") (pintype "passive"))
      (node (ref "U5") (pin "2") (pinfunction "UART1_RXD_2") (pintype "passive"))
    )
    (net (code "63") (name "/SIM800_TX") (class "Default")
      (node (ref "D14") (pin "1") (pinfunction "A_1") (pintype "passive"))
      (node (ref "P1") (pin "3") (pinfunction "3_3") (pintype "passive"))
      (node (ref "U5") (pin "1") (pinfunction "UART1_TXD_1") (pintype "passive"))
    )
    (net (code "64") (name "/SIM_CLK") (class "Default")
      (node (ref "C4") (pin "1") (pinfunction "1_1") (pintype "passive"))
      (node (ref "IC2") (pin "1") (pinfunction "I/O1_1") (pintype "passive"))
      (node (ref "U5") (pin "16") (pinfunction "SIM1_CLK_16") (pintype "passive"))
      (node (ref "XS5") (pin "3") (pinfunction "SIM_CLK_3") (pintype "passive"))
    )
    (net (code "65") (name "/SIM_DAT") (class "Default")
      (node (ref "C6") (pin "2") (pinfunction "2_2") (pintype "passive"))
      (node (ref "IC2") (pin "3") (pinfunction "I/O2_3") (pintype "passive"))
      (node (ref "U5") (pin "15") (pinfunction "SIM1_DATA_15") (pintype "passive"))
      (node (ref "XS5") (pin "6") (pinfunction "SIM_DAT_6") (pintype "passive"))
    )
    (net (code "66") (name "/SIM_RST") (class "Default")
      (node (ref "C5") (pin "1") (pinfunction "1_1") (pintype "passive"))
      (node (ref "IC2") (pin "5") (pinfunction "I/O4_5") (pintype "passive"))
      (node (ref "U5") (pin "17") (pinfunction "SIM1_RST_17") (pintype "passive"))
      (node (ref "XS5") (pin "2") (pinfunction "SIM_RST_2") (pintype "passive"))
    )
    (net (code "67") (name "/SWCLK") (class "Default")
      (node (ref "U11") (pin "49") (pinfunction "PA14/JTCK-SWCLK_49") (pintype "passive"))
      (node (ref "XS7") (pin "4") (pinfunction "4_4") (pintype "passive"))
    )
    (net (code "68") (name "/SWDIO") (class "Default")
      (node (ref "U11") (pin "46") (pinfunction "PA13/JTMS-SWDIO_46") (pintype "passive"))
      (node (ref "XS7") (pin "3") (pinfunction "3_3") (pintype "passive"))
    )
    (net (code "69") (name "/TXD") (class "Default")
      (node (ref "R2") (pin "2") (pinfunction "2_2") (pintype "passive"))
      (node (ref "R9") (pin "1") (pinfunction "1_1") (pintype "passive"))
      (node (ref "U1") (pin "2") (pinfunction "TXD_2") (pintype "passive"))
      (node (ref "U3") (pin "1") (pinfunction "1A_1") (pintype "passive"))
    )
    (net (code "70") (name "/USBDM") (class "Default")
      (node (ref "R103") (pin "2") (pinfunction "2_2") (pintype "passive"))
      (node (ref "U11") (pin "44") (pinfunction "PA11/USART1_CTS/USBDM_/CAN_RX_/TIM1_CH4_44") (pintype "passive"))
    )
    (net (code "71") (name "/USBDP") (class "Default")
      (node (ref "R104") (pin "2") (pinfunction "2_2") (pintype "passive"))
      (node (ref "U11") (pin "45") (pinfunction "PA12/USART1_RTS/USBDP/CAN_TX_/TIM1_ETR_45") (pintype "passive"))
    )
    (net (code "72") (name "/USBEN") (class "Default")
      (node (ref "R106") (pin "2") (pinfunction "2_2") (pintype "passive"))
      (node (ref "U11") (pin "40") (pinfunction "PC9/TIM3_CH4_40") (pintype "passive"))
    )
    (net (code "73") (name "/VIN1") (class "Default")
      (node (ref "P2") (pin "1") (pinfunction "1_1") (pintype "passive"))
      (node (ref "R68") (pin "1") (pinfunction "1_1") (pintype "passive"))
    )
    (net (code "74") (name "/VIN2") (class "Default")
      (node (ref "P3") (pin "1") (pinfunction "1_1") (pintype "passive"))
      (node (ref "R73") (pin "1") (pinfunction "1_1") (pintype "passive"))
    )
    (net (code "75") (name "/VIN3") (class "Default")
      (node (ref "P4") (pin "1") (pinfunction "1_1") (pintype "passive"))
      (node (ref "R92") (pin "1") (pinfunction "1_1") (pintype "passive"))
    )
    (net (code "76") (name "/WP") (class "Default")
      (node (ref "IC8") (pin "7") (pinfunction "WP_7") (pintype "passive"))
      (node (ref "R96") (pin "1") (pinfunction "1_1") (pintype "passive"))
      (node (ref "U11") (pin "57") (pinfunction "PB5/TIM3_CH2/SPI1_MOSI_/_I2C1_SMBA_57") (pintype "passive"))
    )
    (net (code "77") (name "3.3V") (class "Default")
      (node (ref "C58") (pin "2") (pinfunction "2_2") (pintype "passive"))
      (node (ref "C59") (pin "1") (pinfunction "1_1") (pintype "passive"))
      (node (ref "C62") (pin "1") (pinfunction "1_1") (pintype "passive"))
      (node (ref "C66") (pin "2") (pinfunction "2_2") (pintype "passive"))
      (node (ref "C67") (pin "2") (pinfunction "2_2") (pintype "passive"))
      (node (ref "C73") (pin "2") (pinfunction "2_2") (pintype "passive"))
      (node (ref "C74") (pin "2") (pinfunction "2_2") (pintype "passive"))
      (node (ref "C75") (pin "1") (pinfunction "1_1") (pintype "passive"))
      (node (ref "C76") (pin "1") (pinfunction "1_1") (pintype "passive"))
      (node (ref "C77") (pin "1") (pinfunction "1_1") (pintype "passive"))
      (node (ref "C78") (pin "1") (pinfunction "1_1") (pintype "passive"))
      (node (ref "IC8") (pin "8") (pinfunction "VCC_8") (pintype "passive"))
      (node (ref "P5") (pin "1") (pinfunction "1_1") (pintype "passive"))
      (node (ref "P5") (pin "2") (pinfunction "2_2") (pintype "passive"))
      (node (ref "Q10") (pin "2") (pinfunction "CATHODE_2") (pintype "passive"))
      (node (ref "Q14") (pin "2") (pinfunction "CATHODE_2") (pintype "passive"))
      (node (ref "Q18") (pin "2") (pinfunction "E_2") (pintype "passive"))
      (node (ref "Q9") (pin "2") (pinfunction "CATHODE_2") (pintype "passive"))
      (node (ref "R108") (pin "1") (pinfunction "1_1") (pintype "passive"))
      (node (ref "R34") (pin "1") (pinfunction "1_1") (pintype "passive"))
      (node (ref "R46") (pin "1") (pinfunction "1_1") (pintype "passive"))
      (node (ref "R64") (pin "2") (pinfunction "2_2") (pintype "passive"))
      (node (ref "R77") (pin "2") (pinfunction "2_2") (pintype "passive"))
      (node (ref "R78") (pin "2") (pinfunction "2_2") (pintype "passive"))
      (node (ref "R96") (pin "2") (pinfunction "2_2") (pintype "passive"))
      (node (ref "R97") (pin "2") (pinfunction "2_2") (pintype "passive"))
      (node (ref "R98") (pin "2") (pinfunction "2_2") (pintype "passive"))
      (node (ref "U11") (pin "13") (pinfunction "VDDA_13") (pintype "passive"))
      (node (ref "U11") (pin "19") (pinfunction "VDD4_19") (pintype "passive"))
      (node (ref "U11") (pin "32") (pinfunction "VDD1_32") (pintype "passive"))
      (node (ref "U11") (pin "48") (pinfunction "VDD2_48") (pintype "passive"))
      (node (ref "U11") (pin "64") (pinfunction "VDD3_64") (pintype "passive"))
      (node (ref "U6") (pin "4") (pinfunction "Collector_4") (pintype "passive"))
      (node (ref "XS6") (pin "1") (pinfunction "1_1") (pintype "passive"))
      (node (ref "XS7") (pin "5") (pinfunction "5_5") (pintype "passive"))
    )
    (net (code "78") (name "3V3") (class "Default")
      (node (ref "C55") (pin "1") (pinfunction "1_1") (pintype "passive"))
      (node (ref "C56") (pin "1") (pinfunction "1_1") (pintype "passive"))
      (node (ref "R76") (pin "2") (pinfunction "2_2") (pintype "passive"))
      (node (ref "R89") (pin "1") (pinfunction "1_1") (pintype "passive"))
      (node (ref "U9") (pin "6") (pinfunction "VCC_6") (pintype "passive"))
    )
    (net (code "79") (name "4V") (class "Default")
      (node (ref "4") (pin "1") (pinfunction "1_1") (pintype "passive"))
      (node (ref "C18") (pin "1") (pinfunction "1_1") (pintype "passive"))
      (node (ref "C19") (pin "2") (pinfunction "2_2") (pintype "passive"))
      (node (ref "R16") (pin "1") (pinfunction "1_1") (pintype "passive"))
      (node (ref "R53") (pin "2") (pinfunction "2_2") (pintype "passive"))
      (node (ref "R56") (pin "2") (pinfunction "2_2") (pintype "passive"))
      (node (ref "U5") (pin "34") (pinfunction "VBAT_34") (pintype "passive"))
      (node (ref "U5") (pin "35") (pinfunction "VBAT_35") (pintype "passive"))
      (node (ref "V1") (pin "2") (pinfunction "S_2") (pintype "input"))
    )
    (net (code "80") (name "12V") (class "Default")
      (node (ref "C26") (pin "1") (pinfunction "1_1") (pintype "passive"))
      (node (ref "IC3") (pin "8") (pinfunction "IN_8") (pintype "passive"))
      (node (ref "Q4") (pin "3") (pinfunction "S_3") (pintype "input"))
      (node (ref "R33") (pin "1") (pinfunction "1_1") (pintype "passive"))
      (node (ref "R4") (pin "2") (pinfunction "2_2") (pintype "passive"))
      (node (ref "R41") (pin "1") (pinfunction "1_1") (pintype "passive"))
    )
    (net (code "81") (name "CHG_IN") (class "Default")
      (node (ref "C33") (pin "1") (pinfunction "1_1") (pintype "passive"))
      (node (ref "C35") (pin "2") (pinfunction "2_2") (pintype "passive"))
      (node (ref "C36") (pin "1") (pinfunction "1_1") (pintype "passive"))
      (node (ref "C37") (pin "1") (pinfunction "1_1") (pintype "passive"))
      (node (ref "D8") (pin "2") (pinfunction "K_2") (pintype "passive"))
      (node (ref "F1") (pin "2") (pinfunction "2_2") (pintype "passive"))
      (node (ref "Q7") (pin "3") (pinfunction "S_3") (pintype "input"))
      (node (ref "R32") (pin "2") (pinfunction "2_2") (pintype "passive"))
      (node (ref "R65") (pin "2") (pinfunction "2_2") (pintype "passive"))
      (node (ref "U8") (pin "15") (pinfunction "VCC_15") (pintype "passive"))
    )
    (net (code "82") (name "GND") (class "Default")
      (node (ref "C1") (pin "1") (pinfunction "1_1") (pintype "passive"))
      (node (ref "C10") (pin "1") (pinfunction "1_1") (pintype "passive"))
      (node (ref "C11") (pin "1") (pinfunction "1_1") (pintype "passive"))
      (node (ref "C12") (pin "2") (pinfunction "2_2") (pintype "passive"))
      (node (ref "C13") (pin "2") (pinfunction "2_2") (pintype "passive"))
      (node (ref "C14") (pin "1") (pinfunction "1_1") (pintype "passive"))
      (node (ref "C15") (pin "1") (pinfunction "1_1") (pintype "passive"))
      (node (ref "C16") (pin "2") (pinfunction "2_2") (pintype "passive"))
      (node (ref "C17") (pin "1") (pinfunction "1_1") (pintype "passive"))
      (node (ref "C18") (pin "2") (pinfunction "2_2") (pintype "passive"))
      (node (ref "C19") (pin "1") (pinfunction "1_1") (pintype "passive"))
      (node (ref "C2") (pin "1") (pinfunction "1_1") (pintype "passive"))
      (node (ref "C20") (pin "2") (pinfunction "2_2") (pintype "passive"))
      (node (ref "C22") (pin "1") (pinfunction "1_1") (pintype "passive"))
      (node (ref "C23") (pin "1") (pinfunction "1_1") (pintype "passive"))
      (node (ref "C24") (pin "1") (pinfunction "1_1") (pintype "passive"))
      (node (ref "C25") (pin "2") (pinfunction "2_2") (pintype "passive"))
      (node (ref "C26") (pin "2") (pinfunction "2_2") (pintype "passive"))
      (node (ref "C27") (pin "2") (pinfunction "2_2") (pintype "passive"))
      (node (ref "C28") (pin "1") (pinfunction "1_1") (pintype "passive"))
      (node (ref "C29") (pin "2") (pinfunction "2_2") (pintype "passive"))
      (node (ref "C3") (pin "1") (pinfunction "1_1") (pintype "passive"))
      (node (ref "C30") (pin "1") (pinfunction "1_1") (pintype "passive"))
      (node (ref "C31") (pin "1") (pinfunction "1_1") (pintype "passive"))
      (node (ref "C32") (pin "1") (pinfunction "1_1") (pintype "passive"))
      (node (ref "C33") (pin "2") (pinfunction "2_2") (pintype "passive"))
      (node (ref "C34") (pin "2") (pinfunction "2_2") (pintype "passive"))
      (node (ref "C36") (pin "2") (pinfunction "2_2") (pintype "passive"))
      (node (ref "C37") (pin "2") (pinfunction "2_2") (pintype "passive"))
      (node (ref "C38") (pin "2") (pinfunction "2_2") (pintype "passive"))
      (node (ref "C39") (pin "1") (pinfunction "1_1") (pintype "passive"))
      (node (ref "C4") (pin "2") (pinfunction "2_2") (pintype "passive"))
      (node (ref "C40") (pin "1") (pinfunction "1_1") (pintype "passive"))
      (node (ref "C42") (pin "1") (pinfunction "1_1") (pintype "passive"))
      (node (ref "C43") (pin "1") (pinfunction "1_1") (pintype "passive"))
      (node (ref "C44") (pin "1") (pinfunction "1_1") (pintype "passive"))
      (node (ref "C45") (pin "1") (pinfunction "1_1") (pintype "passive"))
      (node (ref "C46") (pin "1") (pinfunction "1_1") (pintype "passive"))
      (node (ref "C47") (pin "1") (pinfunction "1_1") (pintype "passive"))
      (node (ref "C48") (pin "1") (pinfunction "1_1") (pintype "passive"))
      (node (ref "C49") (pin "2") (pinfunction "2_2") (pintype "passive"))
      (node (ref "C5") (pin "2") (pinfunction "2_2") (pintype "passive"))
      (node (ref "C50") (pin "1") (pinfunction "1_1") (pintype "passive"))
      (node (ref "C51") (pin "1") (pinfunction "1_1") (pintype "passive"))
      (node (ref "C52") (pin "1") (pinfunction "1_1") (pintype "passive"))
      (node (ref "C53") (pin "1") (pinfunction "1_1") (pintype "passive"))
      (node (ref "C54") (pin "1") (pinfunction "1_1") (pintype "passive"))
      (node (ref "C55") (pin "2") (pinfunction "2_2") (pintype "passive"))
      (node (ref "C56") (pin "2") (pinfunction "2_2") (pintype "passive"))
      (node (ref "C57") (pin "1") (pinfunction "1_1") (pintype "passive"))
      (node (ref "C58") (pin "1") (pinfunction "1_1") (pintype "passive"))
      (node (ref "C59") (pin "2") (pinfunction "2_2") (pintype "passive"))
      (node (ref "C6") (pin "1") (pinfunction "1_1") (pintype "passive"))
      (node (ref "C60") (pin "2") (pinfunction "2_2") (pintype "passive"))
      (node (ref "C61") (pin "1") (pinfunction "1_1") (pintype "passive"))
      (node (ref "C62") (pin "2") (pinfunction "2_2") (pintype "passive"))
      (node (ref "C63") (pin "1") (pinfunction "1_1") (pintype "passive"))
      (node (ref "C64") (pin "2") (pinfunction "2_2") (pintype "passive"))
      (node (ref "C65") (pin "2") (pinfunction "2_2") (pintype "passive"))
      (node (ref "C66") (pin "1") (pinfunction "1_1") (pintype "passive"))
      (node (ref "C67") (pin "1") (pinfunction "1_1") (pintype "passive"))
      (node (ref "C68") (pin "2") (pinfunction "2_2") (pintype "passive"))
      (node (ref "C69") (pin "2") (pinfunction "2_2") (pintype "passive"))
      (node (ref "C7") (pin "1") (pinfunction "1_1") (pintype "passive"))
      (node (ref "C70") (pin "2") (pinfunction "2_2") (pintype "passive"))
      (node (ref "C71") (pin "2") (pinfunction "2_2") (pintype "passive"))
      (node (ref "C72") (pin "1") (pinfunction "1_1") (pintype "passive"))
      (node (ref "C73") (pin "1") (pinfunction "1_1") (pintype "passive"))
      (node (ref "C74") (pin "1") (pinfunction "1_1") (pintype "passive"))
      (node (ref "C75") (pin "2") (pinfunction "2_2") (pintype "passive"))
      (node (ref "C76") (pin "2") (pinfunction "2_2") (pintype "passive"))
      (node (ref "C77") (pin "2") (pinfunction "2_2") (pintype "passive"))
      (node (ref "C78") (pin "2") (pinfunction "2_2") (pintype "passive"))
      (node (ref "C8") (pin "2") (pinfunction "2_2") (pintype "passive"))
      (node (ref "C9") (pin "2") (pinfunction "2_2") (pintype "passive"))
      (node (ref "D11") (pin "K") (pinfunction "K_K") (pintype "passive"))
      (node (ref "D12") (pin "K") (pinfunction "K_K") (pintype "passive"))
      (node (ref "D16") (pin "K") (pinfunction "K_K") (pintype "passive"))
      (node (ref "D17") (pin "K") (pinfunction "K_K") (pintype "passive"))
      (node (ref "D18") (pin "1") (pinfunction "A_1") (pintype "passive"))
      (node (ref "D19") (pin "1") (pinfunction "A_1") (pintype "passive"))
      (node (ref "D20") (pin "1") (pinfunction "A_1") (pintype "passive"))
      (node (ref "D21") (pin "1") (pinfunction "A_1") (pintype "passive"))
      (node (ref "D23") (pin "1") (pinfunction "A_1") (pintype "passive"))
      (node (ref "D25") (pin "1") (pinfunction "A_1") (pintype "passive"))
      (node (ref "D4") (pin "1") (pinfunction "A_1") (pintype "passive"))
      (node (ref "E1") (pin "1") (pinfunction "1_1") (pintype "passive"))
      (node (ref "E1") (pin "3") (pinfunction "3_3") (pintype "passive"))
      (node (ref "E2") (pin "1") (pinfunction "1_1") (pintype "passive"))
      (node (ref "E2") (pin "3") (pinfunction "3_3") (pintype "passive"))
      (node (ref "GND1") (pin "1") (pinfunction "1_1") (pintype "passive"))
      (node (ref "GND2") (pin "1") (pinfunction "1_1") (pintype "passive"))
      (node (ref "GND3") (pin "1") (pinfunction "1_1") (pintype "passive"))
      (node (ref "GND4") (pin "1") (pinfunction "1_1") (pintype "passive"))
      (node (ref "IC1") (pin "2") (pinfunction "GND_2") (pintype "passive"))
      (node (ref "IC2") (pin "2") (pinfunction "GND_2") (pintype "passive"))
      (node (ref "IC3") (pin "4") (pinfunction "GND_4") (pintype "passive"))
      (node (ref "IC3") (pin "9") (pinfunction "9_9") (pintype "passive"))
      (node (ref "IC4") (pin "0") (pinfunction "0_0") (pintype "passive"))
      (node (ref "IC4") (pin "3") (pinfunction "GND_3") (pintype "passive"))
      (node (ref "IC5") (pin "2") (pinfunction "GND_2") (pintype "passive"))
      (node (ref "IC6") (pin "2") (pinfunction "GND_2") (pintype "passive"))
      (node (ref "IC7") (pin "2") (pinfunction "GND_2") (pintype "passive"))
      (node (ref "IC8") (pin "2") (pinfunction "A1_2") (pintype "passive"))
      (node (ref "IC8") (pin "4") (pinfunction "GND_4") (pintype "passive"))
      (node (ref "J1") (pin "4") (pinfunction "4_4") (pintype "passive"))
      (node (ref "J2") (pin "4") (pinfunction "4_4") (pintype "passive"))
      (node (ref "J3") (pin "4") (pinfunction "4_4") (pintype "passive"))
      (node (ref "J4") (pin "4") (pinfunction "4_4") (pintype "passive"))
      (node (ref "J5") (pin "4") (pinfunction "4_4") (pintype "passive"))
      (node (ref "J6") (pin "4") (pinfunction "4_4") (pintype "passive"))
      (node (ref "J7") (pin "4") (pinfunction "4_4") (pintype "passive"))
      (node (ref "J8") (pin "4") (pinfunction "4_4") (pintype "passive"))
      (node (ref "P1") (pin "1") (pinfunction "1_1") (pintype "passive"))
      (node (ref "P2") (pin "3") (pinfunction "3_3") (pintype "passive"))
      (node (ref "P3") (pin "3") (pinfunction "3_3") (pintype "passive"))
      (node (ref "P4") (pin "3") (pinfunction "3_3") (pintype "passive"))
      (node (ref "P5") (pin "5") (pinfunction "5_5") (pintype "passive"))
      (node (ref "P5") (pin "6") (pinfunction "6_6") (pintype "passive"))
      (node (ref "Q10") (pin "1") (pinfunction "ANODE_1") (pintype "passive"))
      (node (ref "Q11") (pin "2") (pinfunction "E_2") (pintype "passive"))
      (node (ref "Q12") (pin "2") (pinfunction "E_2") (pintype "passive"))
      (node (ref "Q13") (pin "2") (pinfunction "E_2") (pintype "passive"))
      (node (ref "Q14") (pin "1") (pinfunction "ANODE_1") (pintype "passive"))
      (node (ref "Q15") (pin "2") (pinfunction "E_2") (pintype "passive"))
      (node (ref "Q16") (pin "2") (pinfunction "E_2") (pintype "passive"))
      (node (ref "Q17") (pin "2") (pinfunction "E_2") (pintype "passive"))
      (node (ref "Q2") (pin "2") (pinfunction "E_2") (pintype "passive"))
      (node (ref "Q3") (pin "2") (pinfunction "E_2") (pintype "passive"))
      (node (ref "Q5") (pin "2") (pinfunction "E_2") (pintype "passive"))
      (node (ref "Q6") (pin "2") (pinfunction "E_2") (pintype "passive"))
      (node (ref "Q8") (pin "2") (pinfunction "E_2") (pintype "passive"))
      (node (ref "Q9") (pin "1") (pinfunction "ANODE_1") (pintype "passive"))
      (node (ref "R10") (pin "1") (pinfunction "1_1") (pintype "passive"))
      (node (ref "R114") (pin "1") (pinfunction "1_1") (pintype "passive"))
      (node (ref "R117") (pin "2") (pinfunction "2_2") (pintype "passive"))
      (node (ref "R14") (pin "1") (pinfunction "1_1") (pintype "passive"))
      (node (ref "R19") (pin "1") (pinfunction "1_1") (pintype "passive"))
      (node (ref "R20") (pin "2") (pinfunction "2_2") (pintype "passive"))
      (node (ref "R22") (pin "1") (pinfunction "1_1") (pintype "passive"))
      (node (ref "R35") (pin "2") (pinfunction "2_2") (pintype "passive"))
      (node (ref "R38") (pin "1") (pinfunction "1_1") (pintype "passive"))
      (node (ref "R42") (pin "1") (pinfunction "1_1") (pintype "passive"))
      (node (ref "R43") (pin "2") (pinfunction "2_2") (pintype "passive"))
      (node (ref "R44") (pin "1") (pinfunction "1_1") (pintype "passive"))
      (node (ref "R56") (pin "1") (pinfunction "1_1") (pintype "passive"))
      (node (ref "R58") (pin "1") (pinfunction "1_1") (pintype "passive"))
      (node (ref "R60") (pin "1") (pinfunction "1_1") (pintype "passive"))
      (node (ref "R62") (pin "1") (pinfunction "1_1") (pintype "passive"))
      (node (ref "R63") (pin "1") (pinfunction "1_1") (pintype "passive"))
      (node (ref "R67") (pin "1") (pinfunction "1_1") (pintype "passive"))
      (node (ref "R70") (pin "1") (pinfunction "1_1") (pintype "passive"))
      (node (ref "R81") (pin "1") (pinfunction "1_1") (pintype "passive"))
      (node (ref "R87") (pin "1") (pinfunction "1_1") (pintype "passive"))
      (node (ref "R94") (pin "1") (pinfunction "1_1") (pintype "passive"))
      (node (ref "R95") (pin "1") (pinfunction "1_1") (pintype "passive"))
      (node (ref "S1") (pin "1") (pinfunction "1_1") (pintype "passive"))
      (node (ref "S2") (pin "1") (pinfunction "1_1") (pintype "passive"))
      (node (ref "S3") (pin "1") (pinfunction "1_1") (pintype "passive"))
      (node (ref "U1") (pin "4") (pinfunction "GND_4") (pintype "passive"))
      (node (ref "U10") (pin "2") (pinfunction "GND_2") (pintype "passive"))
      (node (ref "U11") (pin "12") (pinfunction "VSSA_12") (pintype "passive"))
      (node (ref "U11") (pin "18") (pinfunction "VSS4_18") (pintype "passive"))
      (node (ref "U11") (pin "31") (pinfunction "VSS1_31") (pintype "passive"))
      (node (ref "U11") (pin "47") (pinfunction "VSS2_47") (pintype "passive"))
      (node (ref "U11") (pin "63") (pinfunction "VSS3_63") (pintype "passive"))
      (node (ref "U12") (pin "4") (pinfunction "4_4") (pintype "passive"))
      (node (ref "U13") (pin "1") (pinfunction "1OE_1") (pintype "passive"))
      (node (ref "U13") (pin "10") (pinfunction "3OE_10") (pintype "passive"))
      (node (ref "U13") (pin "13") (pinfunction "4OE_13") (pintype "passive"))
      (node (ref "U13") (pin "4") (pinfunction "2OE_4") (pintype "passive"))
      (node (ref "U13") (pin "7") (pinfunction "GND_7") (pintype "passive"))
      (node (ref "U14") (pin "10") (pinfunction "10_10") (pintype "passive"))
      (node (ref "U14") (pin "11") (pinfunction "11_11") (pintype "passive"))
      (node (ref "U14") (pin "12") (pinfunction "12_12") (pintype "passive"))
      (node (ref "U14") (pin "6") (pinfunction "VSS_6") (pintype "passive"))
      (node (ref "U14") (pin "9") (pinfunction "9_9") (pintype "passive"))
      (node (ref "U2") (pin "1") (pinfunction "GND_1") (pintype "passive"))
      (node (ref "U3") (pin "7") (pinfunction "GND_7") (pintype "passive"))
      (node (ref "U4") (pin "5") (pinfunction "GND_5") (pintype "power_in"))
      (node (ref "U5") (pin "13") (pinfunction "GND_13") (pintype "passive"))
      (node (ref "U5") (pin "19") (pinfunction "GND_19") (pintype "passive"))
      (node (ref "U5") (pin "21") (pinfunction "GND_21") (pintype "passive"))
      (node (ref "U5") (pin "27") (pinfunction "USB_GND_27") (pintype "passive"))
      (node (ref "U5") (pin "30") (pinfunction "GND_30") (pintype "passive"))
      (node (ref "U5") (pin "31") (pinfunction "GND_31") (pintype "passive"))
      (node (ref "U5") (pin "33") (pinfunction "GND_33") (pintype "passive"))
      (node (ref "U5") (pin "37") (pinfunction "GND_37") (pintype "passive"))
      (node (ref "U5") (pin "45") (pinfunction "GND_45") (pintype "passive"))
      (node (ref "U5") (pin "66") (pinfunction "GND_66") (pintype "passive"))
      (node (ref "U5") (pin "67") (pinfunction "GND_67") (pintype "passive"))
      (node (ref "U5") (pin "69") (pinfunction "GND_69") (pintype "passive"))
      (node (ref "U5") (pin "70") (pinfunction "GND_70") (pintype "passive"))
      (node (ref "U5") (pin "71") (pinfunction "GND_71") (pintype "passive"))
      (node (ref "U5") (pin "72") (pinfunction "GND_72") (pintype "passive"))
      (node (ref "U5") (pin "73") (pinfunction "GND_73") (pintype "passive"))
      (node (ref "U5") (pin "74") (pinfunction "GND_74") (pintype "passive"))
      (node (ref "U5") (pin "75") (pinfunction "GND_75") (pintype "passive"))
      (node (ref "U5") (pin "76") (pinfunction "GND_76") (pintype "passive"))
      (node (ref "U5") (pin "77") (pinfunction "GND_77") (pintype "passive"))
      (node (ref "U5") (pin "8") (pinfunction "GND_8") (pintype "passive"))
      (node (ref "U6") (pin "2") (pinfunction "LED_Cathode_2") (pintype "passive"))
      (node (ref "U7") (pin "1") (pinfunction "VSS_1") (pintype "passive"))
      (node (ref "U8") (pin "2") (pinfunction "PGND_2") (pintype "passive"))
      (node (ref "U8") (pin "3") (pinfunction "GND_3") (pintype "passive"))
      (node (ref "U9") (pin "7") (pinfunction "GND_7") (pintype "passive"))
      (node (ref "XS1") (pin "1") (pinfunction "1_1") (pintype "passive"))
      (node (ref "XS3") (pin "1") (pinfunction "1_1") (pintype "passive"))
      (node (ref "XS4") (pin "1") (pinfunction "1_1") (pintype "passive"))
      (node (ref "XS5") (pin "4") (pinfunction "GND_4") (pintype "passive"))
      (node (ref "XS6") (pin "4") (pinfunction "4_4") (pintype "passive"))
      (node (ref "XS7") (pin "1") (pinfunction "1_1") (pintype "passive"))
      (node (ref "Y2") (pin "2") (pinfunction "2_2") (pintype "passive"))
      (node (ref "Y2") (pin "4") (pinfunction "4_4") (pintype "passive"))
    )
    (net (code "83") (name "GROUND") (class "Default")
      (node (ref "D13") (pin "1") (pinfunction "A_1") (pintype "passive"))
      (node (ref "D5") (pin "2") (pinfunction "K_2") (pintype "passive"))
      (node (ref "GROUND1") (pin "1") (pinfunction "1_1") (pintype "passive"))
    )
    (net (code "84") (name "Net-(C27-Pad1)") (class "Default")
      (node (ref "C27") (pin "1") (pinfunction "1_1") (pintype "passive"))
      (node (ref "R47") (pin "2") (pinfunction "2_2") (pintype "passive"))
    )
    (net (code "85") (name "Net-(C47-Pad2)") (class "Default")
      (node (ref "C47") (pin "2") (pinfunction "2_2") (pintype "passive"))
      (node (ref "R66") (pin "1") (pinfunction "1_1") (pintype "passive"))
    )
    (net (code "86") (name "Net-(C72-Pad2)") (class "Default")
      (node (ref "C72") (pin "2") (pinfunction "2_2") (pintype "passive"))
      (node (ref "R114") (pin "2") (pinfunction "2_2") (pintype "passive"))
      (node (ref "U12") (pin "5") (pinfunction "5_5") (pintype "passive"))
    )
    (net (code "87") (name "Net-(D1-A)") (class "Default")
      (node (ref "D1") (pin "1") (pinfunction "A_1") (pintype "passive"))
      (node (ref "D3") (pin "1") (pinfunction "A_1") (pintype "passive"))
      (node (ref "L1") (pin "2") (pinfunction "2_2") (pintype "passive"))
      (node (ref "U2") (pin "0") (pinfunction "0_0") (pintype "passive"))
      (node (ref "U2") (pin "3") (pinfunction "SW_3") (pintype "passive"))
    )
    (net (code "88") (name "Net-(D1-K)") (class "Default")
      (node (ref "2") (pin "1") (pinfunction "1_1") (pintype "passive"))
      (node (ref "C10") (pin "2") (pinfunction "2_2") (pintype "passive"))
      (node (ref "C11") (pin "2") (pinfunction "2_2") (pintype "passive"))
      (node (ref "C9") (pin "1") (pinfunction "1_1") (pintype "passive"))
      (node (ref "D1") (pin "2") (pinfunction "K_2") (pintype "passive"))
      (node (ref "D3") (pin "2") (pinfunction "K_2") (pintype "passive"))
      (node (ref "R4") (pin "1") (pinfunction "1_1") (pintype "passive"))
      (node (ref "R7") (pin "2") (pinfunction "2_2") (pintype "passive"))
    )
    (net (code "89") (name "Net-(D2-A)") (class "Default")
      (node (ref "C16") (pin "1") (pinfunction "1_1") (pintype "passive"))
      (node (ref "C17") (pin "2") (pinfunction "2_2") (pintype "passive"))
      (node (ref "D2") (pin "1") (pinfunction "A_1") (pintype "passive"))
      (node (ref "Q1") (pin "2") (pinfunction "D_2") (pintype "input"))
      (node (ref "R12") (pin "2") (pinfunction "2_2") (pintype "passive"))
      (node (ref "U2") (pin "4") (pinfunction "VIN_4") (pintype "passive"))
    )
    (net (code "90") (name "Net-(D2-K)") (class "Default")
      (node (ref "D2") (pin "2") (pinfunction "K_2") (pintype "passive"))
      (node (ref "L1") (pin "1") (pinfunction "1_1") (pintype "passive"))
    )
    (net (code "91") (name "Net-(D4-K)") (class "Default")
      (node (ref "D4") (pin "2") (pinfunction "K_2") (pintype "passive"))
      (node (ref "D6") (pin "1") (pinfunction "A_1") (pintype "passive"))
      (node (ref "D8") (pin "1") (pinfunction "A_1") (pintype "passive"))
      (node (ref "F2") (pin "2") (pinfunction "2_2") (pintype "passive"))
    )
    (net (code "92") (name "Net-(D5-A)") (class "Default")
      (node (ref "D5") (pin "1") (pinfunction "A_1") (pintype "passive"))
      (node (ref "D9") (pin "1") (pinfunction "A_1") (pintype "passive"))
      (node (ref "F3") (pin "1") (pinfunction "1_1") (pintype "passive"))
      (node (ref "R10") (pin "2") (pinfunction "2_2") (pintype "passive"))
      (node (ref "U4") (pin "7") (pinfunction "B_7") (pintype "power_in"))
    )
    (net (code "93") (name "Net-(D6-K)") (class "Default")
      (node (ref "D6") (pin "2") (pinfunction "K_2") (pintype "passive"))
      (node (ref "D7") (pin "2") (pinfunction "K_2") (pintype "passive"))
      (node (ref "XS2") (pin "1") (pinfunction "1_1") (pintype "passive"))
    )
    (net (code "94") (name "Net-(D11-PadA)") (class "Default")
      (node (ref "D11") (pin "A") (pinfunction "A_A") (pintype "passive"))
      (node (ref "R13") (pin "1") (pinfunction "1_1") (pintype "passive"))
    )
    (net (code "95") (name "Net-(D12-PadA)") (class "Default")
      (node (ref "D12") (pin "A") (pinfunction "A_A") (pintype "passive"))
      (node (ref "R17") (pin "1") (pinfunction "1_1") (pintype "passive"))
    )
    (net (code "96") (name "Net-(D13-K)") (class "Default")
      (node (ref "D13") (pin "2") (pinfunction "K_2") (pintype "passive"))
      (node (ref "D9") (pin "2") (pinfunction "K_2") (pintype "passive"))
      (node (ref "F4") (pin "1") (pinfunction "1_1") (pintype "passive"))
      (node (ref "R21") (pin "2") (pinfunction "2_2") (pintype "passive"))
      (node (ref "U4") (pin "6") (pinfunction "A_6") (pintype "power_in"))
    )
    (net (code "97") (name "Net-(D16-PadA)") (class "Default")
      (node (ref "D16") (pin "A") (pinfunction "A_A") (pintype "passive"))
      (node (ref "R26") (pin "2") (pinfunction "2_2") (pintype "passive"))
    )
    (net (code "98") (name "Net-(D17-PadA)") (class "Default")
      (node (ref "D17") (pin "A") (pinfunction "A_A") (pintype "passive"))
      (node (ref "R28") (pin "2") (pinfunction "2_2") (pintype "passive"))
    )
    (net (code "99") (name "Net-(D18-K)") (class "Default")
      (node (ref "C22") (pin "2") (pinfunction "2_2") (pintype "passive"))
      (node (ref "D18") (pin "2") (pinfunction "K_2") (pintype "passive"))
      (node (ref "R32") (pin "1") (pinfunction "1_1") (pintype "passive"))
      (node (ref "R38") (pin "2") (pinfunction "2_2") (pintype "passive"))
      (node (ref "U6") (pin "1") (pinfunction "LED_Anode_1") (pintype "passive"))
    )
    (net (code "100") (name "Net-(D19-K)") (class "Default")
      (node (ref "C21") (pin "2") (pinfunction "2_2") (pintype "passive"))
      (node (ref "D19") (pin "2") (pinfunction "K_2") (pintype "passive"))
      (node (ref "IC3") (pin "1") (pinfunction "SW_1") (pintype "passive"))
      (node (ref "L3") (pin "1") (pinfunction "1_1") (pintype "passive"))
    )
    (net (code "101") (name "Net-(D20-K)") (class "Default")
      (node (ref "D20") (pin "2") (pinfunction "K_2") (pintype "passive"))
      (node (ref "D21") (pin "2") (pinfunction "K_2") (pintype "passive"))
      (node (ref "D22") (pin "2") (pinfunction "K_2") (pintype "passive"))
      (node (ref "D24") (pin "2") (pinfunction "K_2") (pintype "passive"))
      (node (ref "L4") (pin "1") (pinfunction "1_1") (pintype "passive"))
      (node (ref "R47") (pin "1") (pinfunction "1_1") (pintype "passive"))
    )
    (net (code "102") (name "Net-(D22-A)") (class "Default")
      (node (ref "D22") (pin "1") (pinfunction "A_1") (pintype "passive"))
      (node (ref "D24") (pin "1") (pinfunction "A_1") (pintype "passive"))
      (node (ref "Q7") (pin "2") (pinfunction "D_2") (pintype "input"))
    )
    (net (code "103") (name "Net-(D23-K)") (class "Default")
      (node (ref "C32") (pin "2") (pinfunction "2_2") (pintype "passive"))
      (node (ref "D23") (pin "2") (pinfunction "K_2") (pintype "passive"))
      (node (ref "R50") (pin "2") (pinfunction "2_2") (pintype "passive"))
      (node (ref "U7") (pin "3") (pinfunction "Vin_3") (pintype "passive"))
    )
    (net (code "104") (name "Net-(D25-K)") (class "Default")
      (node (ref "C29") (pin "1") (pinfunction "1_1") (pintype "passive"))
      (node (ref "C30") (pin "2") (pinfunction "2_2") (pintype "passive"))
      (node (ref "D25") (pin "2") (pinfunction "K_2") (pintype "passive"))
      (node (ref "IC4") (pin "2") (pinfunction "VIN_2") (pintype "passive"))
      (node (ref "R52") (pin "2") (pinfunction "2_2") (pintype "passive"))
      (node (ref "R54") (pin "2") (pinfunction "2_2") (pintype "passive"))
    )
    (net (code "105") (name "Net-(D26-PadK)") (class "Default")
      (node (ref "D26") (pin "K") (pinfunction "K_K") (pintype "passive"))
      (node (ref "R117") (pin "1") (pinfunction "1_1") (pintype "passive"))
    )
    (net (code "106") (name "Net-(E1-Pad2)") (class "Default")
      (node (ref "E1") (pin "2") (pinfunction "2_2") (pintype "passive"))
      (node (ref "L2") (pin "2") (pinfunction "2_2") (pintype "passive"))
      (node (ref "R15") (pin "2") (pinfunction "2_2") (pintype "passive"))
    )
    (net (code "107") (name "Net-(E3-Pad1)") (class "Default")
      (node (ref "E3") (pin "1") (pinfunction "1_1") (pintype "passive"))
      (node (ref "E3") (pin "3") (pinfunction "3_3") (pintype "passive"))
      (node (ref "U9") (pin "8") (pinfunction "GND_8") (pintype "passive"))
    )
    (net (code "108") (name "Net-(F1-Pad1)") (class "Default")
      (node (ref "F1") (pin "1") (pinfunction "1_1") (pintype "passive"))
      (node (ref "XS1") (pin "2") (pinfunction "2_2") (pintype "passive"))
    )
    (net (code "109") (name "Net-(F2-Pad1)") (class "Default")
      (node (ref "F2") (pin "1") (pinfunction "1_1") (pintype "passive"))
      (node (ref "XS3") (pin "2") (pinfunction "2_2") (pintype "passive"))
    )
    (net (code "110") (name "Net-(F5-Pad1)") (class "Default")
      (node (ref "F5") (pin "1") (pinfunction "1_1") (pintype "passive"))
      (node (ref "U12") (pin "1") (pinfunction "1_1") (pintype "passive"))
    )
    (net (code "111") (name "Net-(IC1-BYP)") (class "Default")
      (node (ref "C3") (pin "2") (pinfunction "2_2") (pintype "passive"))
      (node (ref "IC1") (pin "4") (pinfunction "BYP_4") (pintype "passive"))
    )
    (net (code "112") (name "Net-(IC1-VOUT)") (class "Default")
      (node (ref "1") (pin "1") (pinfunction "1_1") (pintype "passive"))
      (node (ref "C2") (pin "2") (pinfunction "2_2") (pintype "passive"))
      (node (ref "IC1") (pin "5") (pinfunction "VOUT_5") (pintype "passive"))
      (node (ref "R1") (pin "1") (pinfunction "1_1") (pintype "passive"))
    )
    (net (code "113") (name "Net-(IC3-BST)") (class "Default")
      (node (ref "C21") (pin "1") (pinfunction "1_1") (pintype "passive"))
      (node (ref "IC3") (pin "2") (pinfunction "BST_2") (pintype "passive"))
    )
    (net (code "114") (name "Net-(IC3-EN)") (class "Default")
      (node (ref "IC3") (pin "7") (pinfunction "EN_7") (pintype "passive"))
      (node (ref "R41") (pin "2") (pinfunction "2_2") (pintype "passive"))
    )
    (net (code "115") (name "Net-(IC3-FB)") (class "Default")
      (node (ref "IC3") (pin "5") (pinfunction "FB_5") (pintype "passive"))
      (node (ref "R35") (pin "1") (pinfunction "1_1") (pintype "passive"))
      (node (ref "R40") (pin "2") (pinfunction "2_2") (pintype "passive"))
    )
    (net (code "116") (name "Net-(IC3-PG)") (class "Default")
      (node (ref "IC3") (pin "6") (pinfunction "PG_6") (pintype "passive"))
      (node (ref "R36") (pin "1") (pinfunction "1_1") (pintype "passive"))
    )
    (net (code "117") (name "Net-(IC3-VCC)") (class "Default")
      (node (ref "C20") (pin "1") (pinfunction "1_1") (pintype "passive"))
      (node (ref "IC3") (pin "3") (pinfunction "VCC_3") (pintype "passive"))
      (node (ref "R36") (pin "2") (pinfunction "2_2") (pintype "passive"))
    )
    (net (code "118") (name "Net-(IC4-ADJ)") (class "Default")
      (node (ref "IC4") (pin "5") (pinfunction "ADJ_5") (pintype "passive"))
      (node (ref "R55") (pin "1") (pinfunction "1_1") (pintype "passive"))
      (node (ref "R58") (pin "2") (pinfunction "2_2") (pintype "passive"))
    )
    (net (code "119") (name "Net-(IC4-EN)") (class "Default")
      (node (ref "IC4") (pin "1") (pinfunction "EN_1") (pintype "passive"))
      (node (ref "R54") (pin "1") (pinfunction "1_1") (pintype "passive"))
    )
    (net (code "120") (name "Net-(IC4-OUT)") (class "Default")
      (node (ref "C31") (pin "2") (pinfunction "2_2") (pintype "passive"))
      (node (ref "C34") (pin "1") (pinfunction "1_1") (pintype "passive"))
      (node (ref "IC4") (pin "4") (pinfunction "OUT_4") (pintype "passive"))
      (node (ref "R53") (pin "1") (pinfunction "1_1") (pintype "passive"))
      (node (ref "R55") (pin "2") (pinfunction "2_2") (pintype "passive"))
    )
    (net (code "121") (name "Net-(IC5-BYP)") (class "Default")
      (node (ref "C46") (pin "2") (pinfunction "2_2") (pintype "passive"))
      (node (ref "IC5") (pin "4") (pinfunction "BYP_4") (pintype "passive"))
    )
    (net (code "122") (name "Net-(IC5-VOUT)") (class "Default")
      (node (ref "C45") (pin "2") (pinfunction "2_2") (pintype "passive"))
      (node (ref "IC5") (pin "5") (pinfunction "VOUT_5") (pintype "passive"))
      (node (ref "MCU_2") (pin "1") (pinfunction "1_1") (pintype "passive"))
      (node (ref "R64") (pin "1") (pinfunction "1_1") (pintype "passive"))
    )
    (net (code "123") (name "Net-(IC6-BYP)") (class "Default")
      (node (ref "C52") (pin "2") (pinfunction "2_2") (pintype "passive"))
      (node (ref "IC6") (pin "4") (pinfunction "BYP_4") (pintype "passive"))
    )
    (net (code "124") (name "Net-(IC6-EN)") (class "Default")
      (node (ref "IC6") (pin "3") (pinfunction "EN_3") (pintype "passive"))
      (node (ref "R82") (pin "2") (pinfunction "2_2") (pintype "passive"))
    )
    (net (code "125") (name "Net-(IC6-VIN)") (class "Default")
      (node (ref "C49") (pin "1") (pinfunction "1_1") (pintype "passive"))
      (node (ref "IC6") (pin "1") (pinfunction "VIN_1") (pintype "passive"))
      (node (ref "R75") (pin "2") (pinfunction "2_2") (pintype "passive"))
      (node (ref "R82") (pin "1") (pinfunction "1_1") (pintype "passive"))
    )
    (net (code "126") (name "Net-(IC6-VOUT)") (class "Default")
      (node (ref "C51") (pin "2") (pinfunction "2_2") (pintype "passive"))
      (node (ref "IC6") (pin "5") (pinfunction "VOUT_5") (pintype "passive"))
      (node (ref "LoRa-3V3") (pin "1") (pinfunction "1_1") (pintype "passive"))
      (node (ref "R76") (pin "1") (pinfunction "1_1") (pintype "passive"))
    )
    (net (code "127") (name "Net-(IC7-BYP)") (class "Default")
      (node (ref "C63") (pin "2") (pinfunction "2_2") (pintype "passive"))
      (node (ref "IC7") (pin "4") (pinfunction "BYP_4") (pintype "passive"))
    )
    (net (code "128") (name "Net-(IC7-EN)") (class "Default")
      (node (ref "IC7") (pin "3") (pinfunction "EN_3") (pintype "passive"))
      (node (ref "R101") (pin "2") (pinfunction "2_2") (pintype "passive"))
    )
    (net (code "129") (name "Net-(IC7-VIN)") (class "Default")
      (node (ref "C60") (pin "1") (pinfunction "1_1") (pintype "passive"))
      (node (ref "IC7") (pin "1") (pinfunction "VIN_1") (pintype "passive"))
      (node (ref "R100") (pin "2") (pinfunction "2_2") (pintype "passive"))
      (node (ref "R101") (pin "1") (pinfunction "1_1") (pintype "passive"))
    )
    (net (code "130") (name "Net-(IC7-VOUT)") (class "Default")
      (node (ref "C61") (pin "2") (pinfunction "2_2") (pintype "passive"))
      (node (ref "IC7") (pin "5") (pinfunction "VOUT_5") (pintype "passive"))
      (node (ref "R99") (pin "1") (pinfunction "1_1") (pintype "passive"))
      (node (ref "TF-1") (pin "1") (pinfunction "1_1") (pintype "passive"))
    )
    (net (code "131") (name "Net-(L2-Pad1)") (class "Default")
      (node (ref "L2") (pin "1") (pinfunction "1_1") (pintype "passive"))
      (node (ref "R8") (pin "1") (pinfunction "1_1") (pintype "passive"))
    )
    (net (code "132") (name "Net-(LED1-K)") (class "Default")
      (node (ref "LED1") (pin "2") (pinfunction "K_2") (pintype "passive"))
      (node (ref "R48") (pin "1") (pinfunction "1_1") (pintype "passive"))
    )
    (net (code "133") (name "Net-(LED2-A-Pad1)") (class "Default")
      (node (ref "LED2") (pin "1") (pinfunction "A_1") (pintype "passive"))
      (node (ref "R71") (pin "2") (pinfunction "2_2") (pintype "passive"))
    )
    (net (code "134") (name "Net-(LED2-A-Pad3)") (class "Default")
      (node (ref "LED2") (pin "3") (pinfunction "A_3") (pintype "passive"))
      (node (ref "R85") (pin "2") (pinfunction "2_2") (pintype "passive"))
    )
    (net (code "135") (name "Net-(LED3-A-Pad1)") (class "Default")
      (node (ref "LED3") (pin "1") (pinfunction "A_1") (pintype "passive"))
      (node (ref "R72") (pin "2") (pinfunction "2_2") (pintype "passive"))
    )
    (net (code "136") (name "Net-(LED3-A-Pad3)") (class "Default")
      (node (ref "LED3") (pin "3") (pinfunction "A_3") (pintype "passive"))
      (node (ref "R86") (pin "2") (pinfunction "2_2") (pintype "passive"))
    )
    (net (code "137") (name "Net-(P5-Pad3)") (class "Default")
      (node (ref "P5") (pin "3") (pinfunction "3_3") (pintype "passive"))
      (node (ref "R115") (pin "2") (pinfunction "2_2") (pintype "passive"))
    )
    (net (code "138") (name "Net-(P5-Pad4)") (class "Default")
      (node (ref "P5") (pin "4") (pinfunction "4_4") (pintype "passive"))
      (node (ref "R116") (pin "1") (pinfunction "1_1") (pintype "passive"))
    )
    (net (code "139") (name "Net-(Q1-G)") (class "Default")
      (node (ref "Q1") (pin "1") (pinfunction "G_1") (pintype "input"))
      (node (ref "Q2") (pin "3") (pinfunction "C_3") (pintype "passive"))
      (node (ref "R6") (pin "1") (pinfunction "1_1") (pintype "passive"))
    )
    (net (code "140") (name "Net-(Q2-B)") (class "Default")
      (node (ref "Q2") (pin "1") (pinfunction "B_1") (pintype "passive"))
      (node (ref "R11") (pin "2") (pinfunction "2_2") (pintype "passive"))
      (node (ref "R19") (pin "2") (pinfunction "2_2") (pintype "passive"))
    )
    (net (code "141") (name "Net-(Q3-B)") (class "Default")
      (node (ref "Q3") (pin "1") (pinfunction "B_1") (pintype "passive"))
      (node (ref "R20") (pin "1") (pinfunction "1_1") (pintype "passive"))
      (node (ref "R24") (pin "2") (pinfunction "2_2") (pintype "passive"))
    )
    (net (code "142") (name "Net-(Q3-C)") (class "Default")
      (node (ref "Q3") (pin "3") (pinfunction "C_3") (pintype "passive"))
      (node (ref "R16") (pin "2") (pinfunction "2_2") (pintype "passive"))
      (node (ref "V1") (pin "1") (pinfunction "G_1") (pintype "input"))
    )
    (net (code "143") (name "Net-(Q4-D)") (class "Default")
      (node (ref "+1") (pin "1") (pinfunction "1_1") (pintype "passive"))
      (node (ref "Q4") (pin "2") (pinfunction "D_2") (pintype "input"))
      (node (ref "R31") (pin "1") (pinfunction "1_1") (pintype "passive"))
    )
    (net (code "144") (name "Net-(Q4-G)") (class "Default")
      (node (ref "Q4") (pin "1") (pinfunction "G_1") (pintype "input"))
      (node (ref "Q6") (pin "3") (pinfunction "C_3") (pintype "passive"))
      (node (ref "R33") (pin "2") (pinfunction "2_2") (pintype "passive"))
    )
    (net (code "145") (name "Net-(Q5-B)") (class "Default")
      (node (ref "Q5") (pin "1") (pinfunction "B_1") (pintype "passive"))
      (node (ref "R43") (pin "1") (pinfunction "1_1") (pintype "passive"))
      (node (ref "R45") (pin "2") (pinfunction "2_2") (pintype "passive"))
    )
    (net (code "146") (name "Net-(Q6-B)") (class "Default")
      (node (ref "Q6") (pin "1") (pinfunction "B_1") (pintype "passive"))
      (node (ref "R39") (pin "2") (pinfunction "2_2") (pintype "passive"))
      (node (ref "R44") (pin "2") (pinfunction "2_2") (pintype "passive"))
    )
    (net (code "147") (name "Net-(Q7-G)") (class "Default")
      (node (ref "Q7") (pin "1") (pinfunction "G_1") (pintype "input"))
      (node (ref "U8") (pin "16") (pinfunction "DRV_16") (pintype "passive"))
    )
    (net (code "148") (name "Net-(Q8-B)") (class "Default")
      (node (ref "Q8") (pin "1") (pinfunction "B_1") (pintype "passive"))
      (node (ref "R59") (pin "2") (pinfunction "2_2") (pintype "passive"))
      (node (ref "R67") (pin "2") (pinfunction "2_2") (pintype "passive"))
    )
    (net (code "149") (name "Net-(Q8-C)") (class "Default")
      (node (ref "Q8") (pin "3") (pinfunction "C_3") (pintype "passive"))
      (node (ref "R57") (pin "2") (pinfunction "2_2") (pintype "passive"))
      (node (ref "V2") (pin "1") (pinfunction "G_1") (pintype "input"))
    )
    (net (code "150") (name "Net-(Q11-B)") (class "Default")
      (node (ref "Q11") (pin "1") (pinfunction "B_1") (pintype "passive"))
      (node (ref "R79") (pin "2") (pinfunction "2_2") (pintype "passive"))
    )
    (net (code "151") (name "Net-(Q11-C)") (class "Default")
      (node (ref "Q11") (pin "3") (pinfunction "C_3") (pintype "passive"))
      (node (ref "R71") (pin "1") (pinfunction "1_1") (pintype "passive"))
    )
    (net (code "152") (name "Net-(Q12-B)") (class "Default")
      (node (ref "Q12") (pin "1") (pinfunction "B_1") (pintype "passive"))
      (node (ref "R80") (pin "2") (pinfunction "2_2") (pintype "passive"))
    )
    (net (code "153") (name "Net-(Q12-C)") (class "Default")
      (node (ref "Q12") (pin "3") (pinfunction "C_3") (pintype "passive"))
      (node (ref "R72") (pin "1") (pinfunction "1_1") (pintype "passive"))
    )
    (net (code "154") (name "Net-(Q15-B)") (class "Default")
      (node (ref "Q15") (pin "1") (pinfunction "B_1") (pintype "passive"))
      (node (ref "R88") (pin "2") (pinfunction "2_2") (pintype "passive"))
      (node (ref "R94") (pin "2") (pinfunction "2_2") (pintype "passive"))
    )
    (net (code "155") (name "Net-(Q15-C)") (class "Default")
      (node (ref "Q15") (pin "3") (pinfunction "C_3") (pintype "passive"))
      (node (ref "R84") (pin "2") (pinfunction "2_2") (pintype "passive"))
      (node (ref "V3") (pin "1") (pinfunction "G_1") (pintype "input"))
    )
    (net (code "156") (name "Net-(Q16-B)") (class "Default")
      (node (ref "Q16") (pin "1") (pinfunction "B_1") (pintype "passive"))
      (node (ref "R90") (pin "2") (pinfunction "2_2") (pintype "passive"))
    )
    (net (code "157") (name "Net-(Q16-C)") (class "Default")
      (node (ref "Q16") (pin "3") (pinfunction "C_3") (pintype "passive"))
      (node (ref "R85") (pin "1") (pinfunction "1_1") (pintype "passive"))
    )
    (net (code "158") (name "Net-(Q17-B)") (class "Default")
      (node (ref "Q17") (pin "1") (pinfunction "B_1") (pintype "passive"))
      (node (ref "R91") (pin "2") (pinfunction "2_2") (pintype "passive"))
    )
    (net (code "159") (name "Net-(Q17-C)") (class "Default")
      (node (ref "Q17") (pin "3") (pinfunction "C_3") (pintype "passive"))
      (node (ref "R86") (pin "1") (pinfunction "1_1") (pintype "passive"))
    )
    (net (code "160") (name "Net-(Q18-B)") (class "Default")
      (node (ref "Q18") (pin "1") (pinfunction "B_1") (pintype "passive"))
      (node (ref "R106") (pin "1") (pinfunction "1_1") (pintype "passive"))
    )
    (net (code "161") (name "Net-(Q18-C)") (class "Default")
      (node (ref "Q18") (pin "3") (pinfunction "C_3") (pintype "passive"))
      (node (ref "R111") (pin "2") (pinfunction "2_2") (pintype "passive"))
    )
    (net (code "162") (name "Net-(U2-EN)") (class "Default")
      (node (ref "R12") (pin "1") (pinfunction "1_1") (pintype "passive"))
      (node (ref "U2") (pin "2") (pinfunction "EN_2") (pintype "passive"))
    )
    (net (code "163") (name "Net-(U2-FB)") (class "Default")
      (node (ref "R14") (pin "2") (pinfunction "2_2") (pintype "passive"))
      (node (ref "R7") (pin "1") (pinfunction "1_1") (pintype "passive"))
      (node (ref "U2") (pin "5") (pinfunction "FB_5") (pintype "passive"))
    )
    (net (code "164") (name "Net-(U3-3Y)") (class "Default")
      (node (ref "R17") (pin "2") (pinfunction "2_2") (pintype "passive"))
      (node (ref "U3") (pin "6") (pinfunction "3Y_6") (pintype "passive"))
    )
    (net (code "165") (name "Net-(U3-4Y)") (class "Default")
      (node (ref "R23") (pin "2") (pinfunction "2_2") (pintype "passive"))
      (node (ref "U3") (pin "9") (pinfunction "4Y_9") (pintype "passive"))
      (node (ref "U4") (pin "1") (pinfunction "RO_1") (pintype "power_in"))
    )
    (net (code "166") (name "Net-(U3-5A)") (class "Default")
      (node (ref "D10") (pin "2") (pinfunction "1_2") (pintype "passive"))
      (node (ref "R18") (pin "1") (pinfunction "1_1") (pintype "passive"))
      (node (ref "U3") (pin "10") (pinfunction "5A_10") (pintype "passive"))
      (node (ref "U4") (pin "4") (pinfunction "DI_4") (pintype "power_in"))
    )
    (net (code "167") (name "Net-(U3-6A)") (class "Default")
      (node (ref "U3") (pin "12") (pinfunction "6A_12") (pintype "passive"))
      (node (ref "U4") (pin "2") (pinfunction "~{RE}_2") (pintype "power_in"))
      (node (ref "U4") (pin "3") (pinfunction "DE_3") (pintype "power_in"))
    )
    (net (code "168") (name "Net-(U3-6Y)") (class "Default")
      (node (ref "C12") (pin "1") (pinfunction "1_1") (pintype "passive"))
      (node (ref "D10") (pin "1") (pinfunction "1_1") (pintype "passive"))
      (node (ref "R18") (pin "2") (pinfunction "2_2") (pintype "passive"))
      (node (ref "U3") (pin "13") (pinfunction "6Y_13") (pintype "passive"))
    )
    (net (code "169") (name "Net-(U5-GPIO1)") (class "Default")
      (node (ref "R27") (pin "1") (pinfunction "1_1") (pintype "passive"))
      (node (ref "U5") (pin "57") (pinfunction "GPIO1_57") (pintype "passive"))
    )
    (net (code "170") (name "Net-(U5-GPS_ANT)") (class "Default")
      (node (ref "R15") (pin "1") (pinfunction "1_1") (pintype "passive"))
      (node (ref "U5") (pin "68") (pinfunction "GPS_ANT_68") (pintype "passive"))
    )
    (net (code "171") (name "Net-(U5-GPS_RXD)") (class "Default")
      (node (ref "R29") (pin "2") (pinfunction "2_2") (pintype "passive"))
      (node (ref "U5") (pin "62") (pinfunction "GPS_RXD_62") (pintype "passive"))
    )
    (net (code "172") (name "Net-(U5-GPS_TXD)") (class "Default")
      (node (ref "R30") (pin "2") (pinfunction "2_2") (pintype "passive"))
      (node (ref "U5") (pin "61") (pinfunction "GPS_TXD_61") (pintype "passive"))
    )
    (net (code "173") (name "Net-(U5-GSM_ANT)") (class "Default")
      (node (ref "E2") (pin "2") (pinfunction "2_2") (pintype "passive"))
      (node (ref "U5") (pin "32") (pinfunction "GSM_ANT_32") (pintype "passive"))
    )
    (net (code "174") (name "Net-(U5-STATUS)") (class "Default")
      (node (ref "R28") (pin "1") (pinfunction "1_1") (pintype "passive"))
      (node (ref "U5") (pin "42") (pinfunction "STATUS_42") (pintype "passive"))
    )
    (net (code "175") (name "Net-(U5-VRTC)") (class "Default")
      (node (ref "R37") (pin "1") (pinfunction "1_1") (pintype "passive"))
      (node (ref "U5") (pin "28") (pinfunction "VRTC_28") (pintype "passive"))
    )
    (net (code "176") (name "Net-(U7-Vout)") (class "Default")
      (node (ref "C28") (pin "2") (pinfunction "2_2") (pintype "passive"))
      (node (ref "MCU_1") (pin "1") (pinfunction "1_1") (pintype "passive"))
      (node (ref "R51") (pin "1") (pinfunction "1_1") (pintype "passive"))
      (node (ref "U7") (pin "2") (pinfunction "Vout_2") (pintype "passive"))
    )
    (net (code "177") (name "Net-(U8-COM1)") (class "Default")
      (node (ref "C43") (pin "2") (pinfunction "2_2") (pintype "passive"))
      (node (ref "U8") (pin "8") (pinfunction "COM1_8") (pintype "passive"))
    )
    (net (code "178") (name "Net-(U8-COM2)") (class "Default")
      (node (ref "R66") (pin "2") (pinfunction "2_2") (pintype "passive"))
      (node (ref "U8") (pin "9") (pinfunction "COM2_9") (pintype "passive"))
    )
    (net (code "179") (name "Net-(U8-COM3)") (class "Default")
      (node (ref "C38") (pin "1") (pinfunction "1_1") (pintype "passive"))
      (node (ref "U8") (pin "11") (pinfunction "COM3_11") (pintype "passive"))
    )
    (net (code "180") (name "Net-(U8-CSP)") (class "Default")
      (node (ref "L4") (pin "2") (pinfunction "2_2") (pintype "passive"))
      (node (ref "RCS1") (pin "2") (pinfunction "2_2") (pintype "passive"))
      (node (ref "RCS2") (pin "2") (pinfunction "2_2") (pintype "passive"))
      (node (ref "U8") (pin "13") (pinfunction "CSP_13") (pintype "passive"))
    )
    (net (code "181") (name "Net-(U8-FB)") (class "Default")
      (node (ref "C41") (pin "1") (pinfunction "1_1") (pintype "passive"))
      (node (ref "R61") (pin "1") (pinfunction "1_1") (pintype "passive"))
      (node (ref "R63") (pin "2") (pinfunction "2_2") (pintype "passive"))
      (node (ref "U8") (pin "10") (pinfunction "FB_10") (pintype "passive"))
    )
    (net (code "182") (name "Net-(U8-MPPT)") (class "Default")
      (node (ref "R62") (pin "2") (pinfunction "2_2") (pintype "passive"))
      (node (ref "R65") (pin "1") (pinfunction "1_1") (pintype "passive"))
      (node (ref "U8") (pin "7") (pinfunction "MPPT_7") (pintype "passive"))
    )
    (net (code "183") (name "Net-(U8-TEMP)") (class "Default")
      (node (ref "R60") (pin "2") (pinfunction "2_2") (pintype "passive"))
      (node (ref "U8") (pin "6") (pinfunction "TEMP_6") (pintype "passive"))
    )
    (net (code "184") (name "Net-(U8-VG)") (class "Default")
      (node (ref "C35") (pin "1") (pinfunction "1_1") (pintype "passive"))
      (node (ref "U8") (pin "1") (pinfunction "VG_1") (pintype "passive"))
    )
    (net (code "185") (name "Net-(U9-ANT)") (class "Default")
      (node (ref "E3") (pin "2") (pinfunction "2_2") (pintype "passive"))
      (node (ref "U9") (pin "9") (pinfunction "ANT_9") (pintype "passive"))
    )
    (net (code "186") (name "Net-(U10-VCC)") (class "Default")
      (node (ref "R102") (pin "2") (pinfunction "2_2") (pintype "passive"))
      (node (ref "U10") (pin "1") (pinfunction "VCC_1") (pintype "passive"))
    )
    (net (code "187") (name "Net-(U11-PA9{slash}USART1_TX{slash}TIM1_CH2)") (class "Default")
      (node (ref "R109") (pin "1") (pinfunction "1_1") (pintype "passive"))
      (node (ref "U11") (pin "42") (pinfunction "PA9/USART1_TX/TIM1_CH2_42") (pintype "passive"))
    )
    (net (code "188") (name "Net-(U11-PA10{slash}USART1_RX{slash}TIM1_CH3)") (class "Default")
      (node (ref "R105") (pin "1") (pinfunction "1_1") (pintype "passive"))
      (node (ref "U11") (pin "43") (pinfunction "PA10/USART1_RX/TIM1_CH3_43") (pintype "passive"))
    )
    (net (code "189") (name "Net-(U11-PC14{slash}OSC32_IN)") (class "Default")
      (node (ref "C65") (pin "1") (pinfunction "1_1") (pintype "passive"))
      (node (ref "U11") (pin "3") (pinfunction "PC14/OSC32_IN_3") (pintype "passive"))
      (node (ref "Y1") (pin "2") (pinfunction "2_2") (pintype "passive"))
    )
    (net (code "190") (name "Net-(U11-PC15{slash}OSC32_OUT)") (class "Default")
      (node (ref "C64") (pin "1") (pinfunction "1_1") (pintype "passive"))
      (node (ref "U11") (pin "4") (pinfunction "PC15/OSC32_OUT_4") (pintype "passive"))
      (node (ref "Y1") (pin "1") (pinfunction "1_1") (pintype "passive"))
    )
    (net (code "191") (name "Net-(U11-PD0{slash}OSC_IN)") (class "Default")
      (node (ref "C69") (pin "1") (pinfunction "1_1") (pintype "passive"))
      (node (ref "U11") (pin "5") (pinfunction "PD0/OSC_IN_5") (pintype "passive"))
      (node (ref "Y2") (pin "3") (pinfunction "3_3") (pintype "passive"))
    )
    (net (code "192") (name "Net-(U11-PD1{slash}OSC_OUT)") (class "Default")
      (node (ref "C68") (pin "1") (pinfunction "1_1") (pintype "passive"))
      (node (ref "U11") (pin "6") (pinfunction "PD1/OSC_OUT_6") (pintype "passive"))
      (node (ref "Y2") (pin "1") (pinfunction "1_1") (pintype "passive"))
    )
    (net (code "193") (name "Net-(U13-1A)") (class "Default")
      (node (ref "R107") (pin "2") (pinfunction "2_2") (pintype "passive"))
      (node (ref "U13") (pin "2") (pinfunction "1A_2") (pintype "passive"))
    )
    (net (code "194") (name "Net-(U13-2A)") (class "Default")
      (node (ref "R112") (pin "2") (pinfunction "2_2") (pintype "passive"))
      (node (ref "U13") (pin "5") (pinfunction "2A_5") (pintype "passive"))
    )
    (net (code "195") (name "Net-(U13-3A)") (class "Default")
      (node (ref "R113") (pin "1") (pinfunction "1_1") (pintype "passive"))
      (node (ref "U13") (pin "9") (pinfunction "3A_9") (pintype "passive"))
    )
    (net (code "196") (name "Net-(U13-4A)") (class "Default")
      (node (ref "R110") (pin "1") (pinfunction "1_1") (pintype "passive"))
      (node (ref "U13") (pin "12") (pinfunction "4A_12") (pintype "passive"))
    )
    (net (code "197") (name "Net-(V1-D)") (class "Default")
      (node (ref "R8") (pin "2") (pinfunction "2_2") (pintype "passive"))
      (node (ref "V1") (pin "3") (pinfunction "D_3") (pintype "input"))
    )
    (net (code "198") (name "Net-(V2-D)") (class "Default")
      (node (ref "R52") (pin "1") (pinfunction "1_1") (pintype "passive"))
      (node (ref "V2") (pin "3") (pinfunction "D_3") (pintype "input"))
    )
    (net (code "199") (name "Net-(V3-D)") (class "Default")
      (node (ref "R75") (pin "1") (pinfunction "1_1") (pintype "passive"))
      (node (ref "V3") (pin "3") (pinfunction "D_3") (pintype "input"))
    )
    (net (code "200") (name "SIM_VCC") (class "Default")
      (node (ref "C7") (pin "2") (pinfunction "2_2") (pintype "passive"))
      (node (ref "IC2") (pin "4") (pinfunction "I/O3_4") (pintype "passive"))
      (node (ref "U5") (pin "18") (pinfunction "SIM1_VDD_18") (pintype "passive"))
      (node (ref "XS5") (pin "1") (pinfunction "SIM_VCC_1") (pintype "passive"))
      (node (ref "XS5") (pin "5") (pinfunction "CCVPP_5") (pintype "passive"))
    )
    (net (code "201") (name "TF-3V3") (class "Default")
      (node (ref "C70") (pin "1") (pinfunction "1_1") (pintype "passive"))
      (node (ref "R99") (pin "2") (pinfunction "2_2") (pintype "passive"))
      (node (ref "U13") (pin "14") (pinfunction "VCC_14") (pintype "passive"))
      (node (ref "U14") (pin "4") (pinfunction "VDD_4") (pintype "passive"))
    )
    (net (code "202") (name "VBAT") (class "Default")
      (node (ref "C39") (pin "2") (pinfunction "2_2") (pintype "passive"))
      (node (ref "C40") (pin "2") (pinfunction "2_2") (pintype "passive"))
      (node (ref "C41") (pin "2") (pinfunction "2_2") (pintype "passive"))
      (node (ref "C42") (pin "2") (pinfunction "2_2") (pintype "passive"))
      (node (ref "C53") (pin "2") (pinfunction "2_2") (pintype "passive"))
      (node (ref "D7") (pin "1") (pinfunction "A_1") (pintype "passive"))
      (node (ref "R61") (pin "2") (pinfunction "2_2") (pintype "passive"))
      (node (ref "R83") (pin "2") (pinfunction "2_2") (pintype "passive"))
      (node (ref "RCS1") (pin "1") (pinfunction "1_1") (pintype "passive"))
      (node (ref "RCS2") (pin "1") (pinfunction "1_1") (pintype "passive"))
      (node (ref "U8") (pin "14") (pinfunction "BAT_14") (pintype "passive"))
      (node (ref "XS4") (pin "2") (pinfunction "2_2") (pintype "passive"))
    )
    (net (code "203") (name "VCC5V") (class "Default")
      (node (ref "C44") (pin "2") (pinfunction "2_2") (pintype "passive"))
      (node (ref "F5") (pin "2") (pinfunction "2_2") (pintype "passive"))
      (node (ref "IC5") (pin "1") (pinfunction "VIN_1") (pintype "passive"))
      (node (ref "IC5") (pin "3") (pinfunction "EN_3") (pintype "passive"))
      (node (ref "LED2") (pin "2") (pinfunction "K_2") (pintype "passive"))
      (node (ref "LED3") (pin "2") (pinfunction "K_2") (pintype "passive"))
      (node (ref "R48") (pin "2") (pinfunction "2_2") (pintype "passive"))
      (node (ref "R51") (pin "2") (pinfunction "2_2") (pintype "passive"))
    )
    (net (code "204") (name "VDD_EXT") (class "Default")
      (node (ref "R25") (pin "2") (pinfunction "2_2") (pintype "passive"))
      (node (ref "R49") (pin "1") (pinfunction "1_1") (pintype "passive"))
      (node (ref "U5") (pin "40") (pinfunction "VDD_EXT_40") (pintype "passive"))
    )
    (net (code "205") (name "VRTC") (class "Default")
      (node (ref "R102") (pin "1") (pinfunction "1_1") (pintype "passive"))
      (node (ref "R37") (pin "2") (pinfunction "2_2") (pintype "passive"))
      (node (ref "U11") (pin "1") (pinfunction "VBAT_1") (pintype "passive"))
    )
    (net (code "206") (name "unconnected-(HO1-Pad0)") (class "Default")
      (node (ref "HO1") (pin "0") (pinfunction "0_0") (pintype "passive"))
    )
    (net (code "207") (name "unconnected-(HO2-Pad0)") (class "Default")
      (node (ref "HO2") (pin "0") (pinfunction "0_0") (pintype "passive"))
    )
    (net (code "208") (name "unconnected-(HO3-Pad0)") (class "Default")
      (node (ref "HO3") (pin "0") (pinfunction "0_0") (pintype "passive"))
    )
    (net (code "209") (name "unconnected-(HO4-Pad0)") (class "Default")
      (node (ref "HO4") (pin "0") (pinfunction "0_0") (pintype "passive"))
    )
    (net (code "210") (name "unconnected-(IC8-NC-Pad1)") (class "Default")
      (node (ref "IC8") (pin "1") (pinfunction "NC_1") (pintype "passive"))
    )
    (net (code "211") (name "unconnected-(IC8-NC-Pad3)") (class "Default")
      (node (ref "IC8") (pin "3") (pinfunction "NC_3") (pintype "passive"))
    )
    (net (code "212") (name "unconnected-(U1-G-Pad5)") (class "Default")
      (node (ref "U1") (pin "5") (pinfunction "G_5") (pintype "passive"))
    )
    (net (code "213") (name "unconnected-(U5-1PPS-Pad60)") (class "Default")
      (node (ref "U5") (pin "60") (pinfunction "1PPS_60") (pintype "passive"))
    )
    (net (code "214") (name "unconnected-(U5-ADC-Pad38)") (class "Default")
      (node (ref "U5") (pin "38") (pinfunction "ADC_38") (pintype "passive"))
    )
    (net (code "215") (name "unconnected-(U5-BT_ANT-Pad20)") (class "Default")
      (node (ref "U5") (pin "20") (pinfunction "BT_ANT_20") (pintype "passive"))
    )
    (net (code "216") (name "unconnected-(U5-GND-Pad36)") (class "Default")
      (node (ref "U5") (pin "36") (pinfunction "GND_36") (pintype "passive"))
    )
    (net (code "217") (name "unconnected-(U5-GND-Pad63)") (class "Default")
      (node (ref "U5") (pin "63") (pinfunction "GND_63") (pintype "passive"))
    )
    (net (code "218") (name "unconnected-(U5-GPIO2-Pad58)") (class "Default")
      (node (ref "U5") (pin "58") (pinfunction "GPIO2_58") (pintype "passive"))
    )
    (net (code "219") (name "unconnected-(U5-MCCA0-Pad49)") (class "Default")
      (node (ref "U5") (pin "49") (pinfunction "MCCA0_49") (pintype "passive"))
    )
    (net (code "220") (name "unconnected-(U5-MCCA1-Pad48)") (class "Default")
      (node (ref "U5") (pin "48") (pinfunction "MCCA1_48") (pintype "passive"))
    )
    (net (code "221") (name "unconnected-(U5-MCCA2-Pad47)") (class "Default")
      (node (ref "U5") (pin "47") (pinfunction "MCCA2_47") (pintype "passive"))
    )
    (net (code "222") (name "unconnected-(U5-MCCA3-Pad46)") (class "Default")
      (node (ref "U5") (pin "46") (pinfunction "MCCA3_46") (pintype "passive"))
    )
    (net (code "223") (name "unconnected-(U5-MCCK-Pad50)") (class "Default")
      (node (ref "U5") (pin "50") (pinfunction "MCCK_50") (pintype "passive"))
    )
    (net (code "224") (name "unconnected-(U5-MCCMO-Pad51)") (class "Default")
      (node (ref "U5") (pin "51") (pinfunction "MCCMO_51") (pintype "passive"))
    )
    (net (code "225") (name "unconnected-(U5-MICN-Pad10)") (class "Default")
      (node (ref "U5") (pin "10") (pinfunction "MICN_10") (pintype "passive"))
    )
    (net (code "226") (name "unconnected-(U5-MICP-Pad9)") (class "Default")
      (node (ref "U5") (pin "9") (pinfunction "MICP_9") (pintype "passive"))
    )
    (net (code "227") (name "unconnected-(U5-RF_SYNC-Pad29)") (class "Default")
      (node (ref "U5") (pin "29") (pinfunction "RF_SYNC_29") (pintype "passive"))
    )
    (net (code "228") (name "unconnected-(U5-SCL-Pad65)") (class "Default")
      (node (ref "U5") (pin "65") (pinfunction "SCL_65") (pintype "passive"))
    )
    (net (code "229") (name "unconnected-(U5-SDA-Pad64)") (class "Default")
      (node (ref "U5") (pin "64") (pinfunction "SDA_64") (pintype "passive"))
    )
    (net (code "230") (name "unconnected-(U5-SIM1_DET-Pad14)") (class "Default")
      (node (ref "U5") (pin "14") (pinfunction "SIM1_DET_14") (pintype "passive"))
    )
    (net (code "231") (name "unconnected-(U5-SIM2_CLK-Pad54)") (class "Default")
      (node (ref "U5") (pin "54") (pinfunction "SIM2_CLK_54") (pintype "passive"))
    )
    (net (code "232") (name "unconnected-(U5-SIM2_DATA-Pad53)") (class "Default")
      (node (ref "U5") (pin "53") (pinfunction "SIM2_DATA_53") (pintype "passive"))
    )
    (net (code "233") (name "unconnected-(U5-SIM2_DET-Pad52)") (class "Default")
      (node (ref "U5") (pin "52") (pinfunction "SIM2_DET_52") (pintype "passive"))
    )
    (net (code "234") (name "unconnected-(U5-SIM2_RST-Pad55)") (class "Default")
      (node (ref "U5") (pin "55") (pinfunction "SIM2_RST_55") (pintype "passive"))
    )
    (net (code "235") (name "unconnected-(U5-SIM2_VDD-Pad56)") (class "Default")
      (node (ref "U5") (pin "56") (pinfunction "SIM2_VDD_56") (pintype "passive"))
    )
    (net (code "236") (name "unconnected-(U5-SPK1N-Pad12)") (class "Default")
      (node (ref "U5") (pin "12") (pinfunction "SPK1N_12") (pintype "passive"))
    )
    (net (code "237") (name "unconnected-(U5-SPK1P-Pad11)") (class "Default")
      (node (ref "U5") (pin "11") (pinfunction "SPK1P_11") (pintype "passive"))
    )
    (net (code "238") (name "unconnected-(U5-SPK2N-Pad43)") (class "Default")
      (node (ref "U5") (pin "43") (pinfunction "SPK2N_43") (pintype "passive"))
    )
    (net (code "239") (name "unconnected-(U5-SPK2P-Pad44)") (class "Default")
      (node (ref "U5") (pin "44") (pinfunction "SPK2P_44") (pintype "passive"))
    )
    (net (code "240") (name "unconnected-(U5-UART1_CTS-Pad4)") (class "Default")
      (node (ref "U5") (pin "4") (pinfunction "UART1_CTS_4") (pintype "passive"))
    )
    (net (code "241") (name "unconnected-(U5-UART1_DCD-Pad5)") (class "Default")
      (node (ref "U5") (pin "5") (pinfunction "UART1_DCD_5") (pintype "passive"))
    )
    (net (code "242") (name "unconnected-(U5-UART1_DTR-Pad6)") (class "Default")
      (node (ref "U5") (pin "6") (pinfunction "UART1_DTR_6") (pintype "passive"))
    )
    (net (code "243") (name "unconnected-(U5-UART1_RI-Pad7)") (class "Default")
      (node (ref "U5") (pin "7") (pinfunction "UART1_RI_7") (pintype "passive"))
    )
    (net (code "244") (name "unconnected-(U5-UART1_RTS-Pad3)") (class "Default")
      (node (ref "U5") (pin "3") (pinfunction "UART1_RTS_3") (pintype "passive"))
    )
    (net (code "245") (name "unconnected-(U5-USB_DM-Pad26)") (class "Default")
      (node (ref "U5") (pin "26") (pinfunction "USB_DM_26") (pintype "passive"))
    )
    (net (code "246") (name "unconnected-(U5-USB_DP-Pad25)") (class "Default")
      (node (ref "U5") (pin "25") (pinfunction "USB_DP_25") (pintype "passive"))
    )
    (net (code "247") (name "unconnected-(U5-USB_VBUS-Pad24)") (class "Default")
      (node (ref "U5") (pin "24") (pinfunction "USB_VBUS_24") (pintype "passive"))
    )
    (net (code "248") (name "unconnected-(U8-NC-Pad12)") (class "Default")
      (node (ref "U8") (pin "12") (pinfunction "NC_12") (pintype "passive"))
    )
    (net (code "249") (name "unconnected-(U9-GND-Pad10)") (class "Default")
      (node (ref "U9") (pin "10") (pinfunction "GND_10") (pintype "passive+no_connect"))
    )
    (net (code "250") (name "unconnected-(U9-GND-Pad11)") (class "Default")
      (node (ref "U9") (pin "11") (pinfunction "GND_11") (pintype "passive+no_connect"))
    )
    (net (code "251") (name "unconnected-(U11-PA1{slash}USART2_RTS_{slash}ADC12_IN1{slash}TIM2_CH2-Pad15)") (class "Default")
      (node (ref "U11") (pin "15") (pinfunction "PA1/USART2_RTS_/ADC12_IN1/TIM2_CH2_15") (pintype "passive"))
    )
    (net (code "252") (name "unconnected-(U11-PA8{slash}USART1_CK{slash}TIM1_CH1{slash}MCO-Pad41)") (class "Default")
      (node (ref "U11") (pin "41") (pinfunction "PA8/USART1_CK/TIM1_CH1/MCO_41") (pintype "passive"))
    )
    (net (code "253") (name "unconnected-(U11-PB0{slash}ADC12_IN8{slash}TIM3_CH3{slash}TIM1_CH2N-Pad26)") (class "Default")
      (node (ref "U11") (pin "26") (pinfunction "PB0/ADC12_IN8/TIM3_CH3/TIM1_CH2N_26") (pintype "passive"))
    )
    (net (code "254") (name "unconnected-(U11-PB9{slash}I2C_1_SDA{slash}CAN_TX{slash}TIM4_CH4-Pad62)") (class "Default")
      (node (ref "U11") (pin "62") (pinfunction "PB9/I2C_1_SDA/CAN_TX/TIM4_CH4_62") (pintype "passive"))
    )
    (net (code "255") (name "unconnected-(U11-PC5{slash}ADC12_IN15-Pad25)") (class "Default")
      (node (ref "U11") (pin "25") (pinfunction "PC5/ADC12_IN15_25") (pintype "passive"))
    )
    (net (code "256") (name "unconnected-(U11-PC13{slash}TAMPER-RTC-Pad2)") (class "Default")
      (node (ref "U11") (pin "2") (pinfunction "PC13/TAMPER-RTC_2") (pintype "passive"))
    )
    (net (code "257") (name "unconnected-(U14-DAT1-Pad8)") (class "Default")
      (node (ref "U14") (pin "8") (pinfunction "DAT1_8") (pintype "passive+no_connect"))
    )
    (net (code "258") (name "unconnected-(U14-DAT2-Pad1)") (class "Default")
      (node (ref "U14") (pin "1") (pinfunction "DAT2_1") (pintype "passive+no_connect"))
    )
  )
)
